# SPU.net
KiCad netlist of a schematic drawn in EAGLE
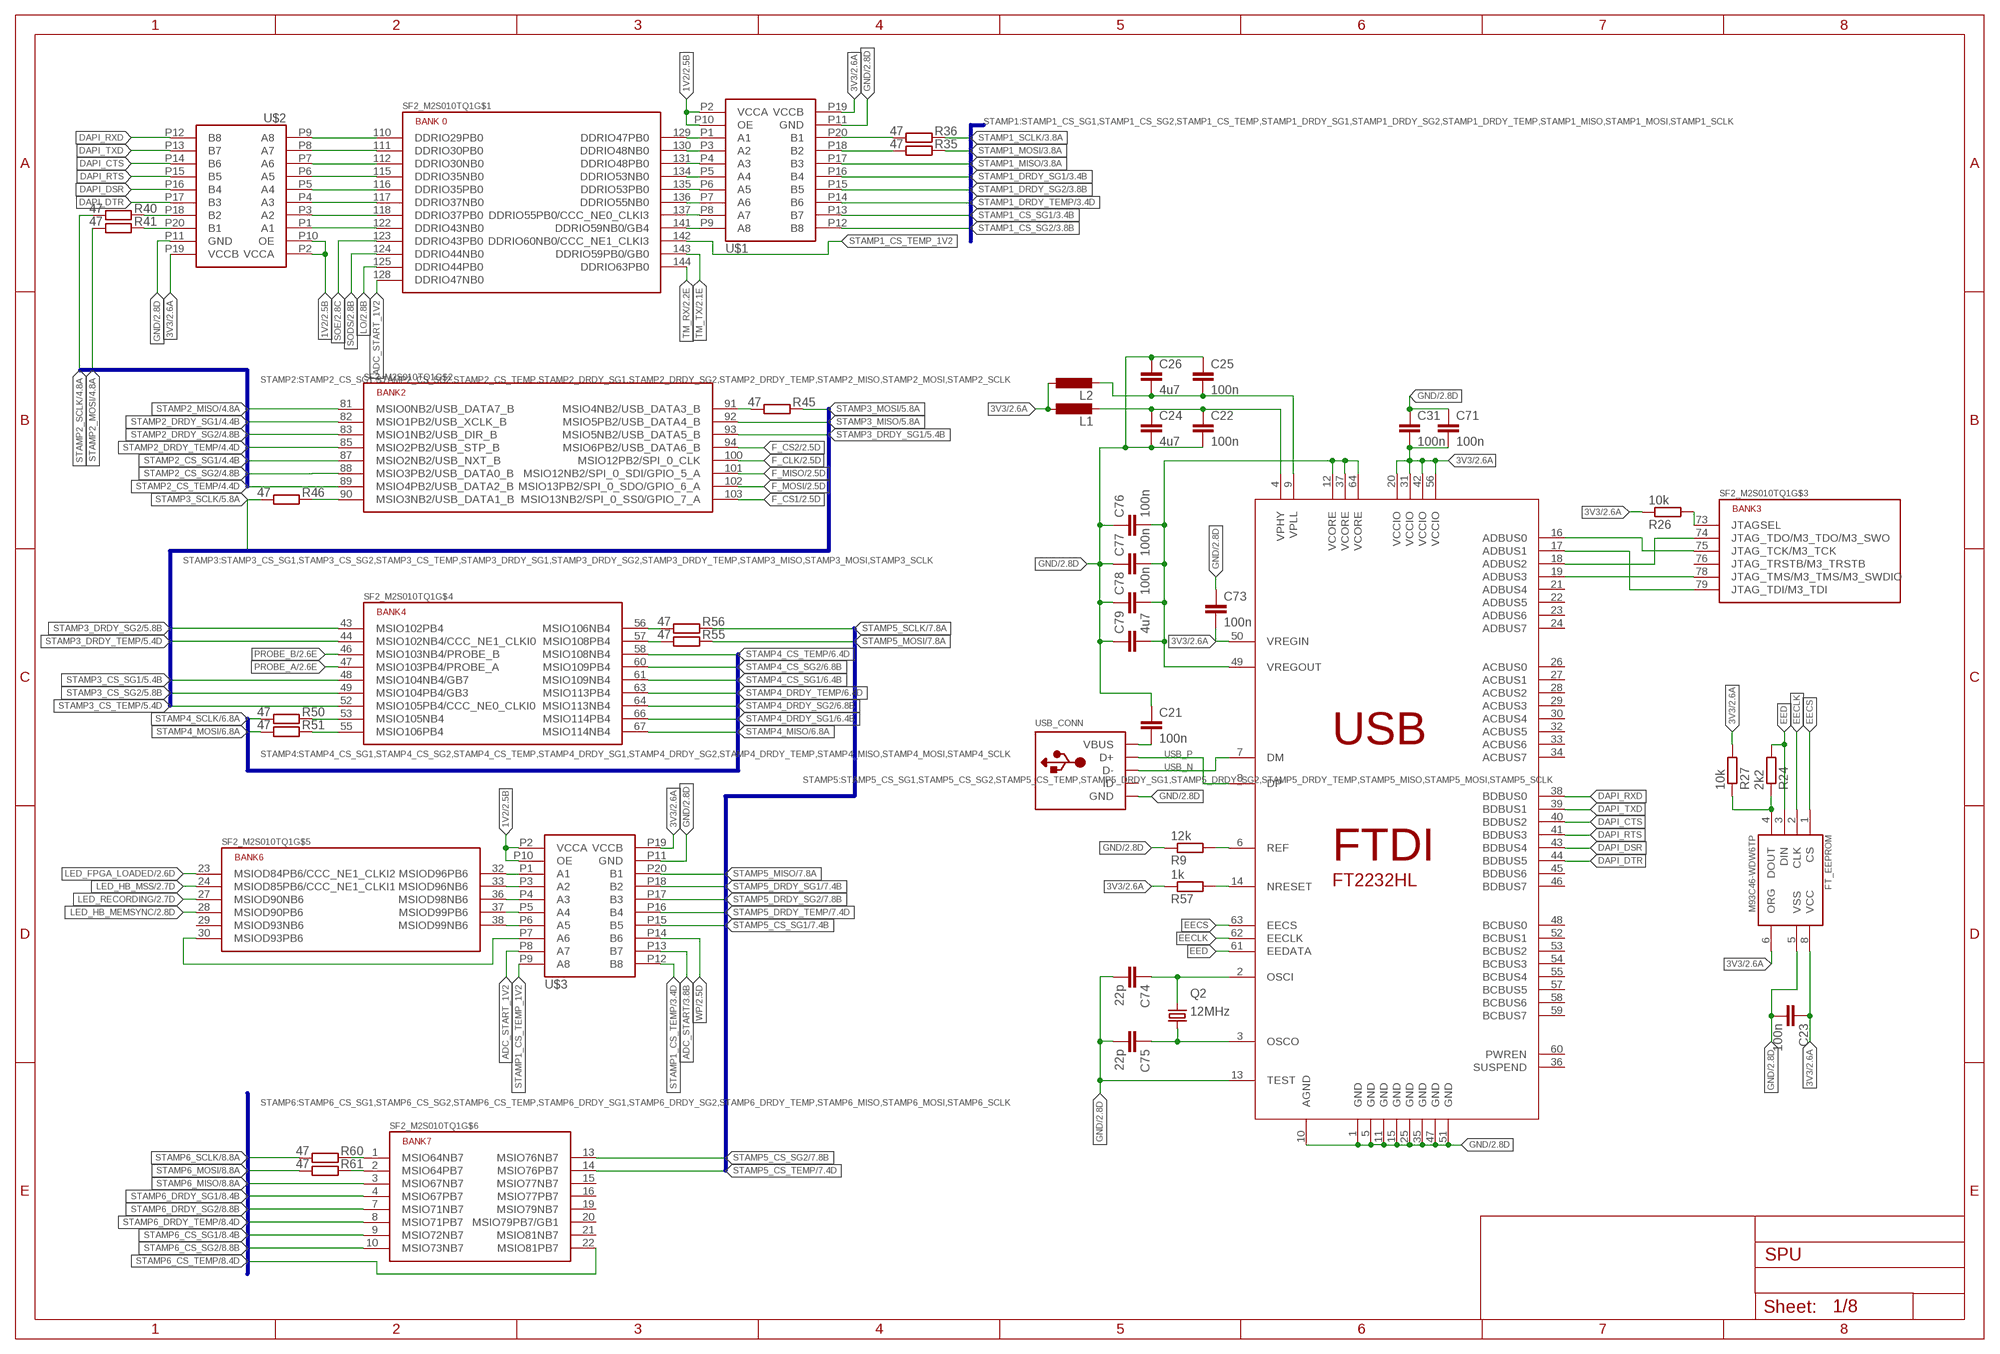
[diagram p0: schematic, sheet 1]
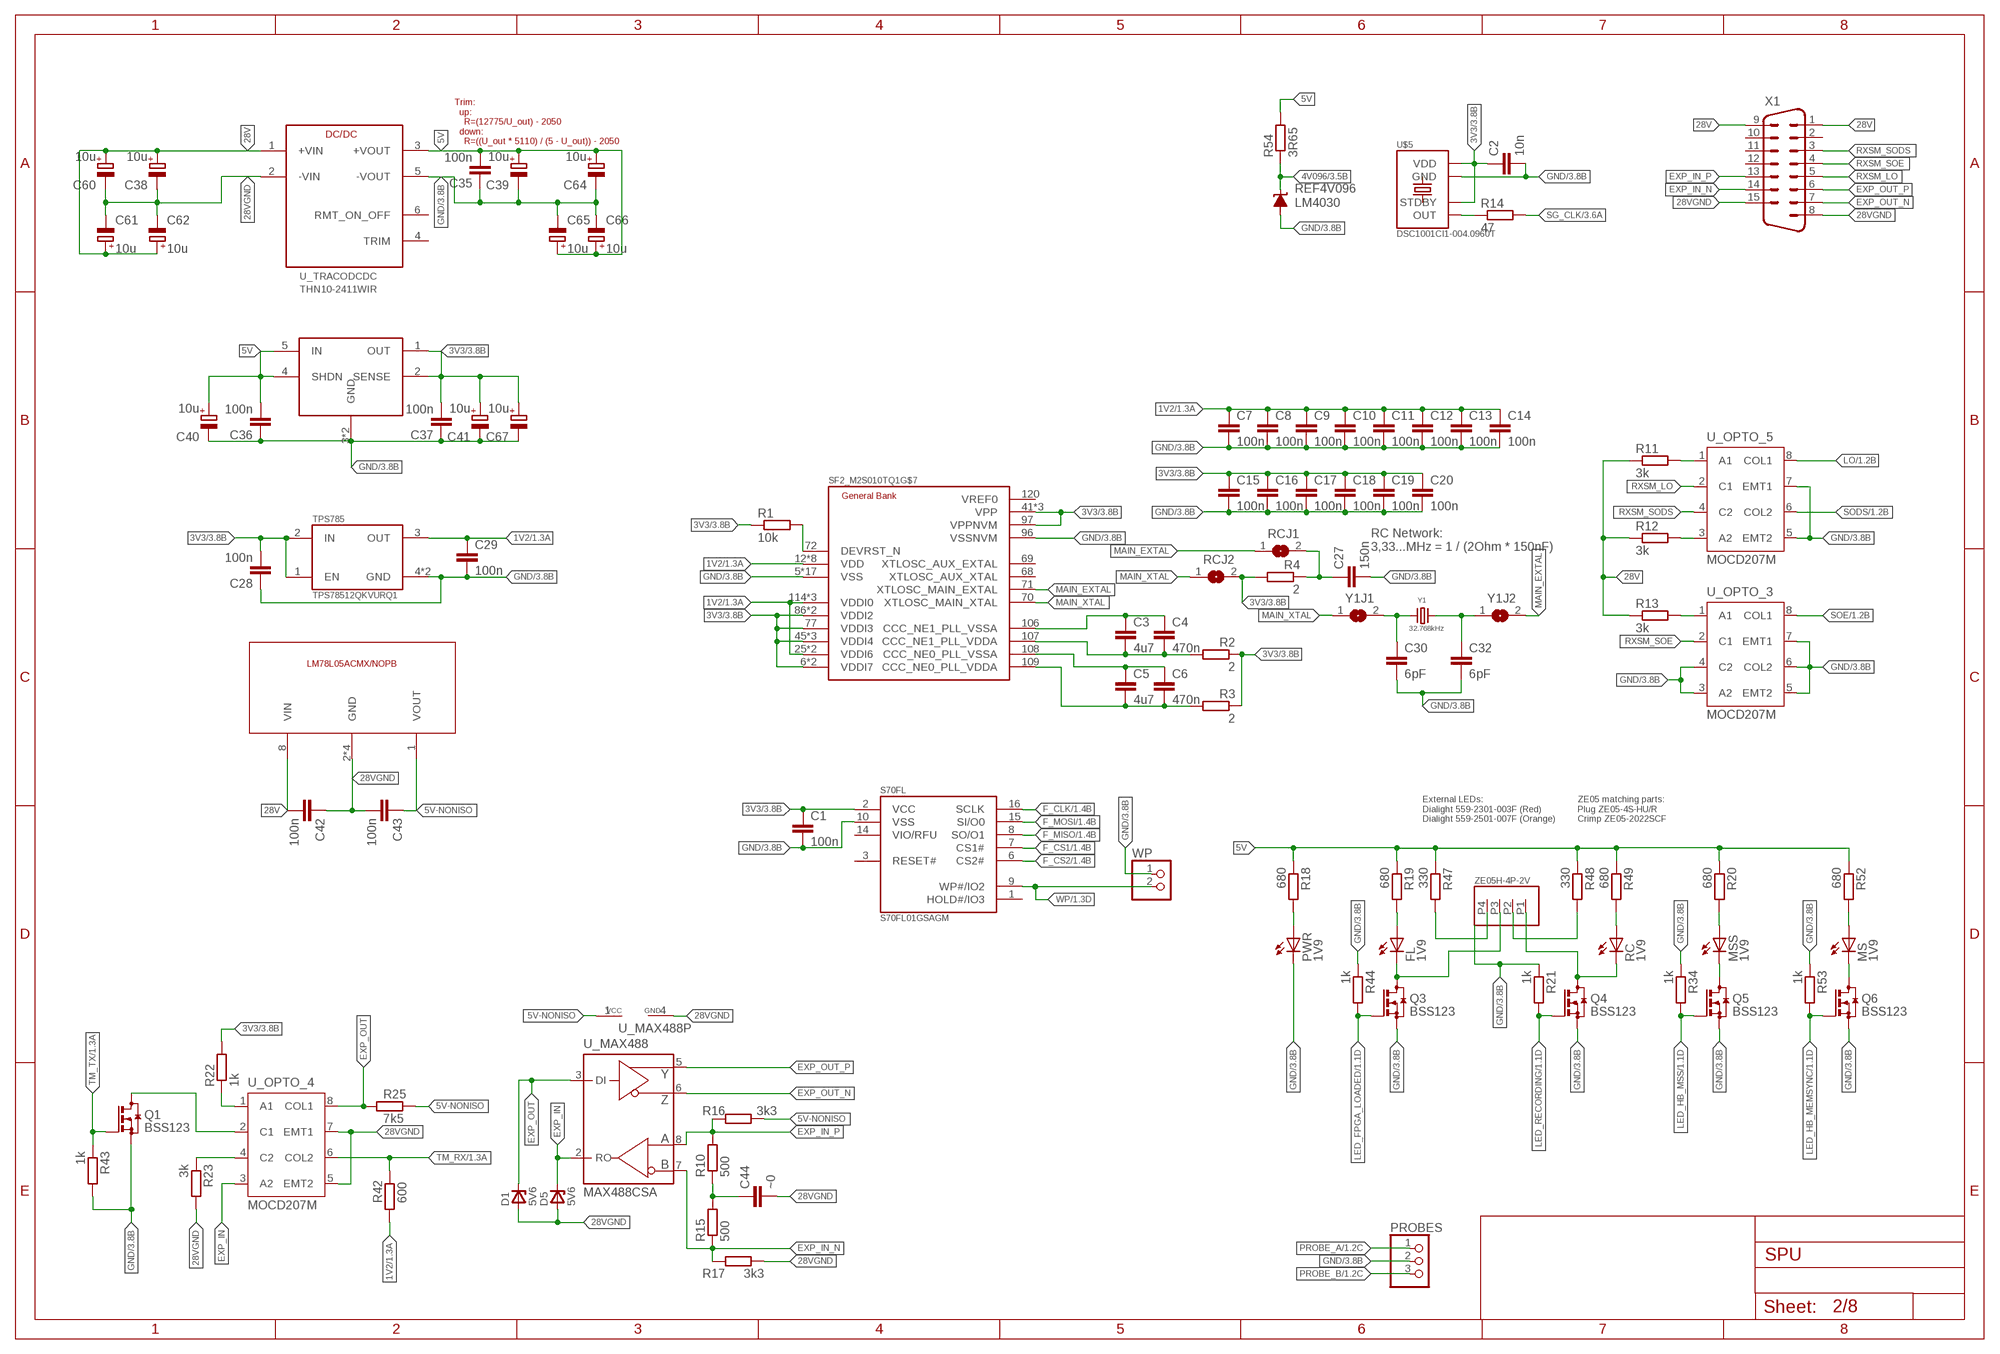
[diagram p1: schematic, sheet 2]
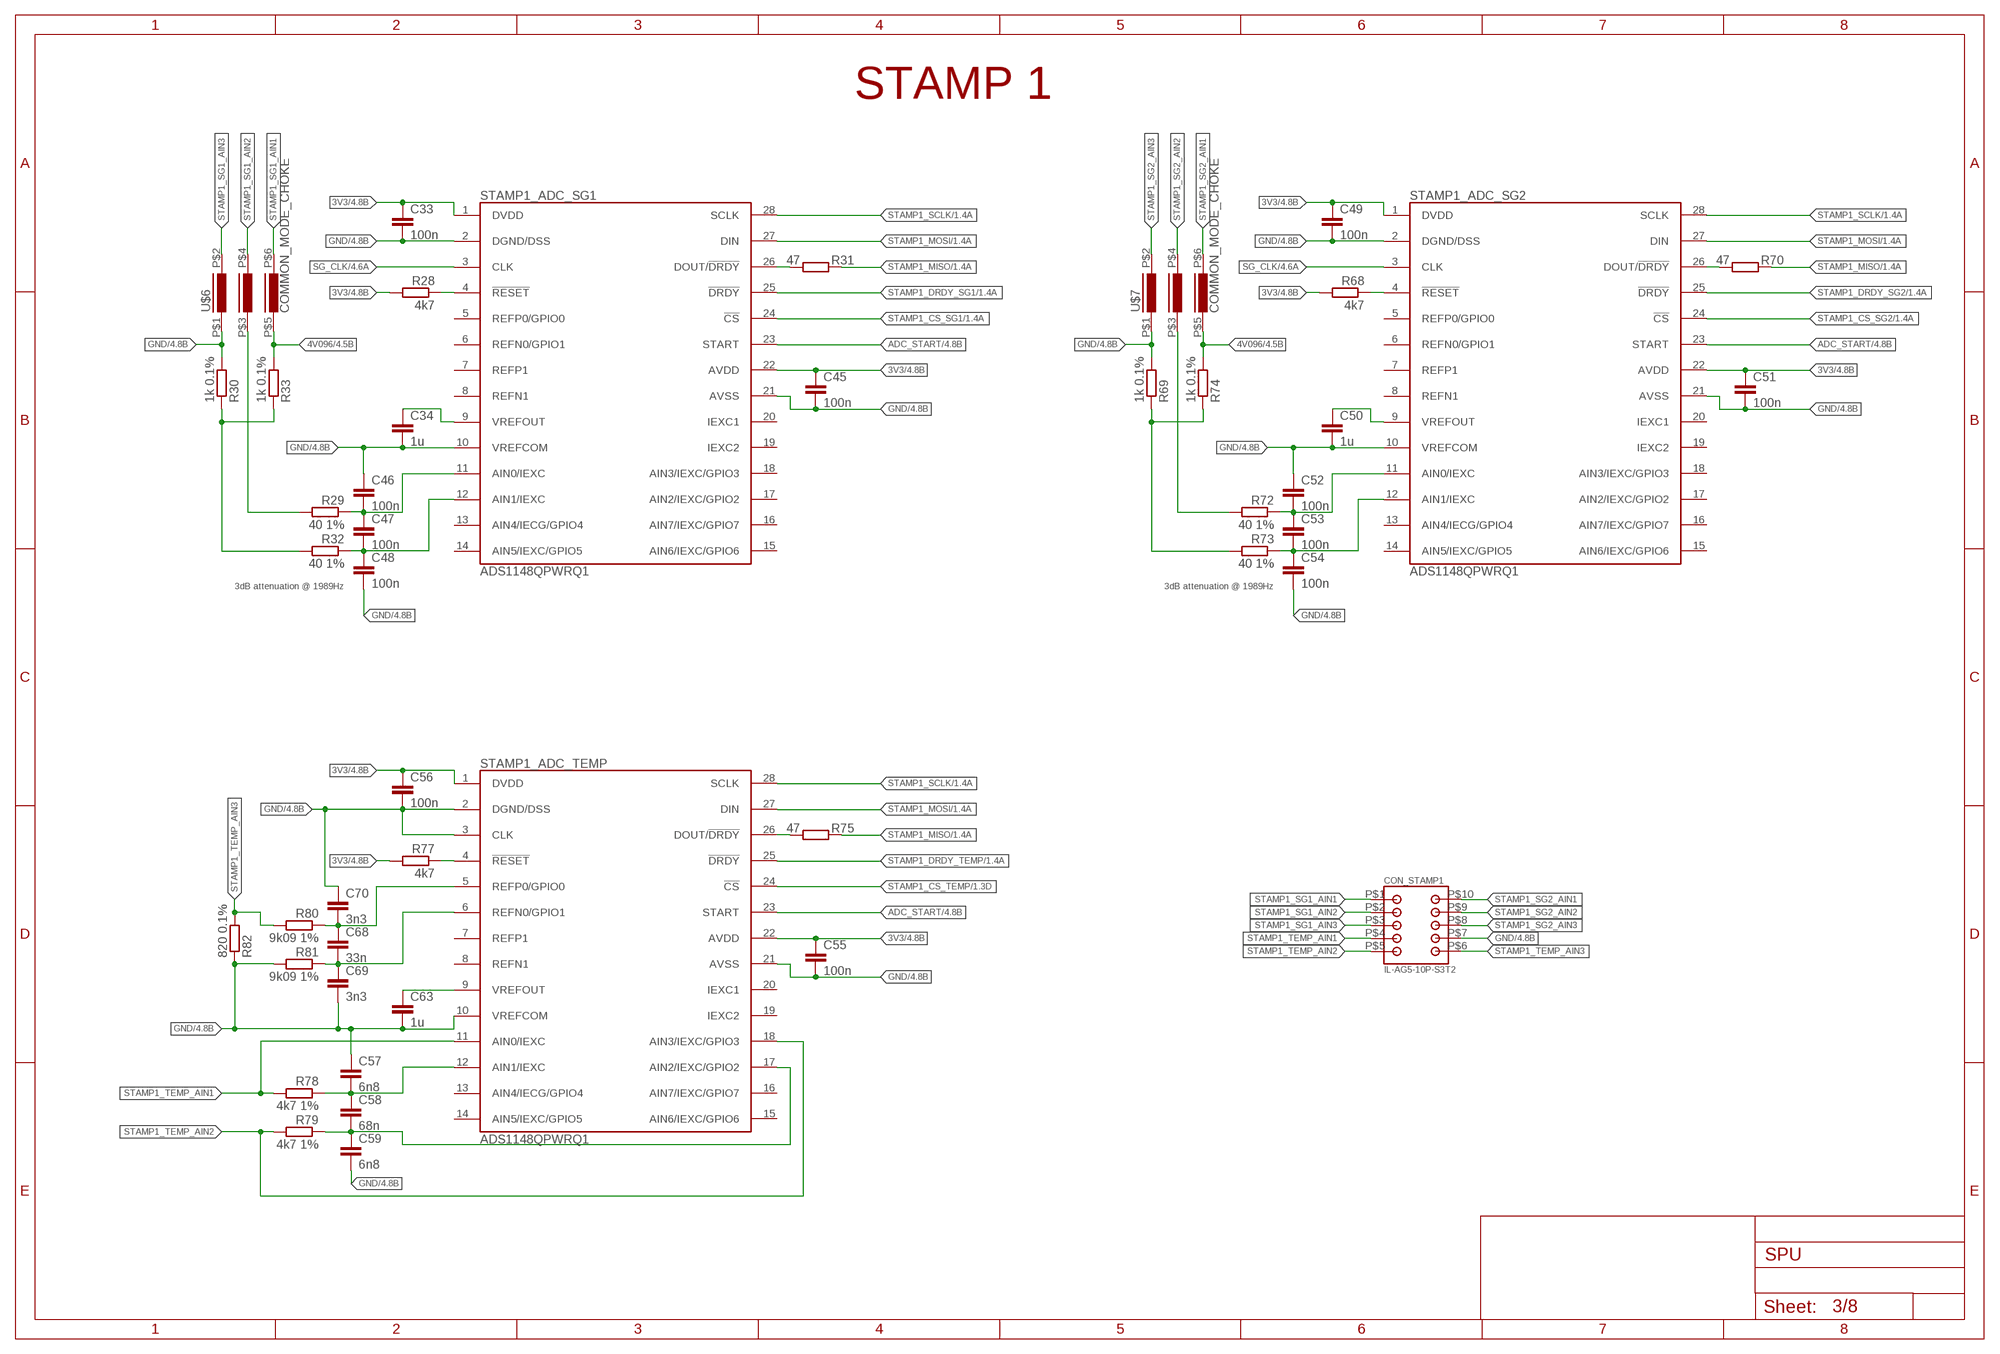
[diagram p2: schematic, sheet 3]
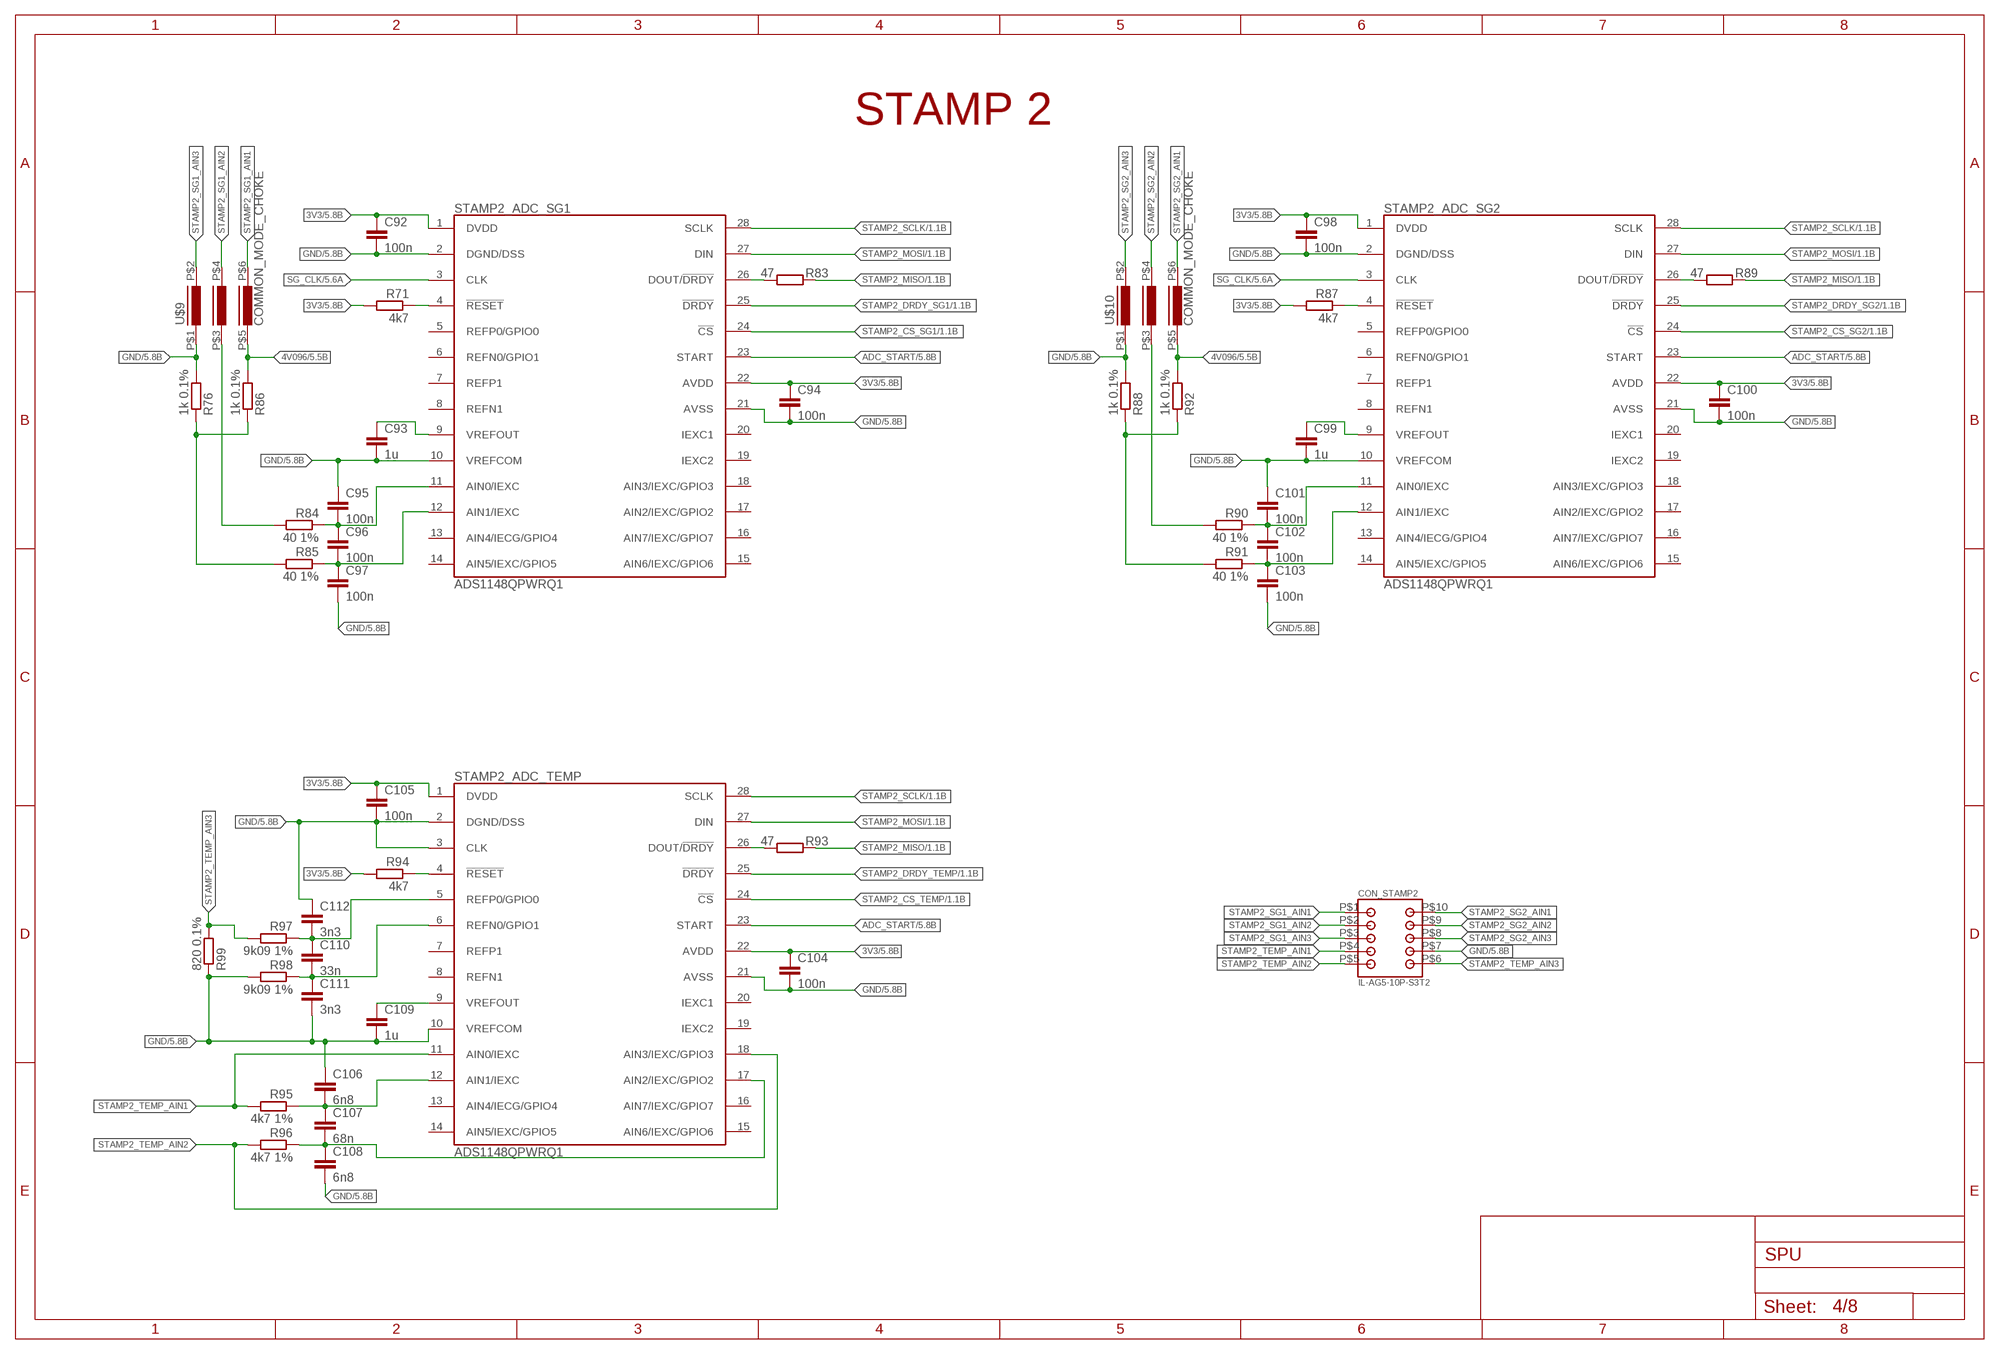
[diagram p3: schematic, sheet 4]
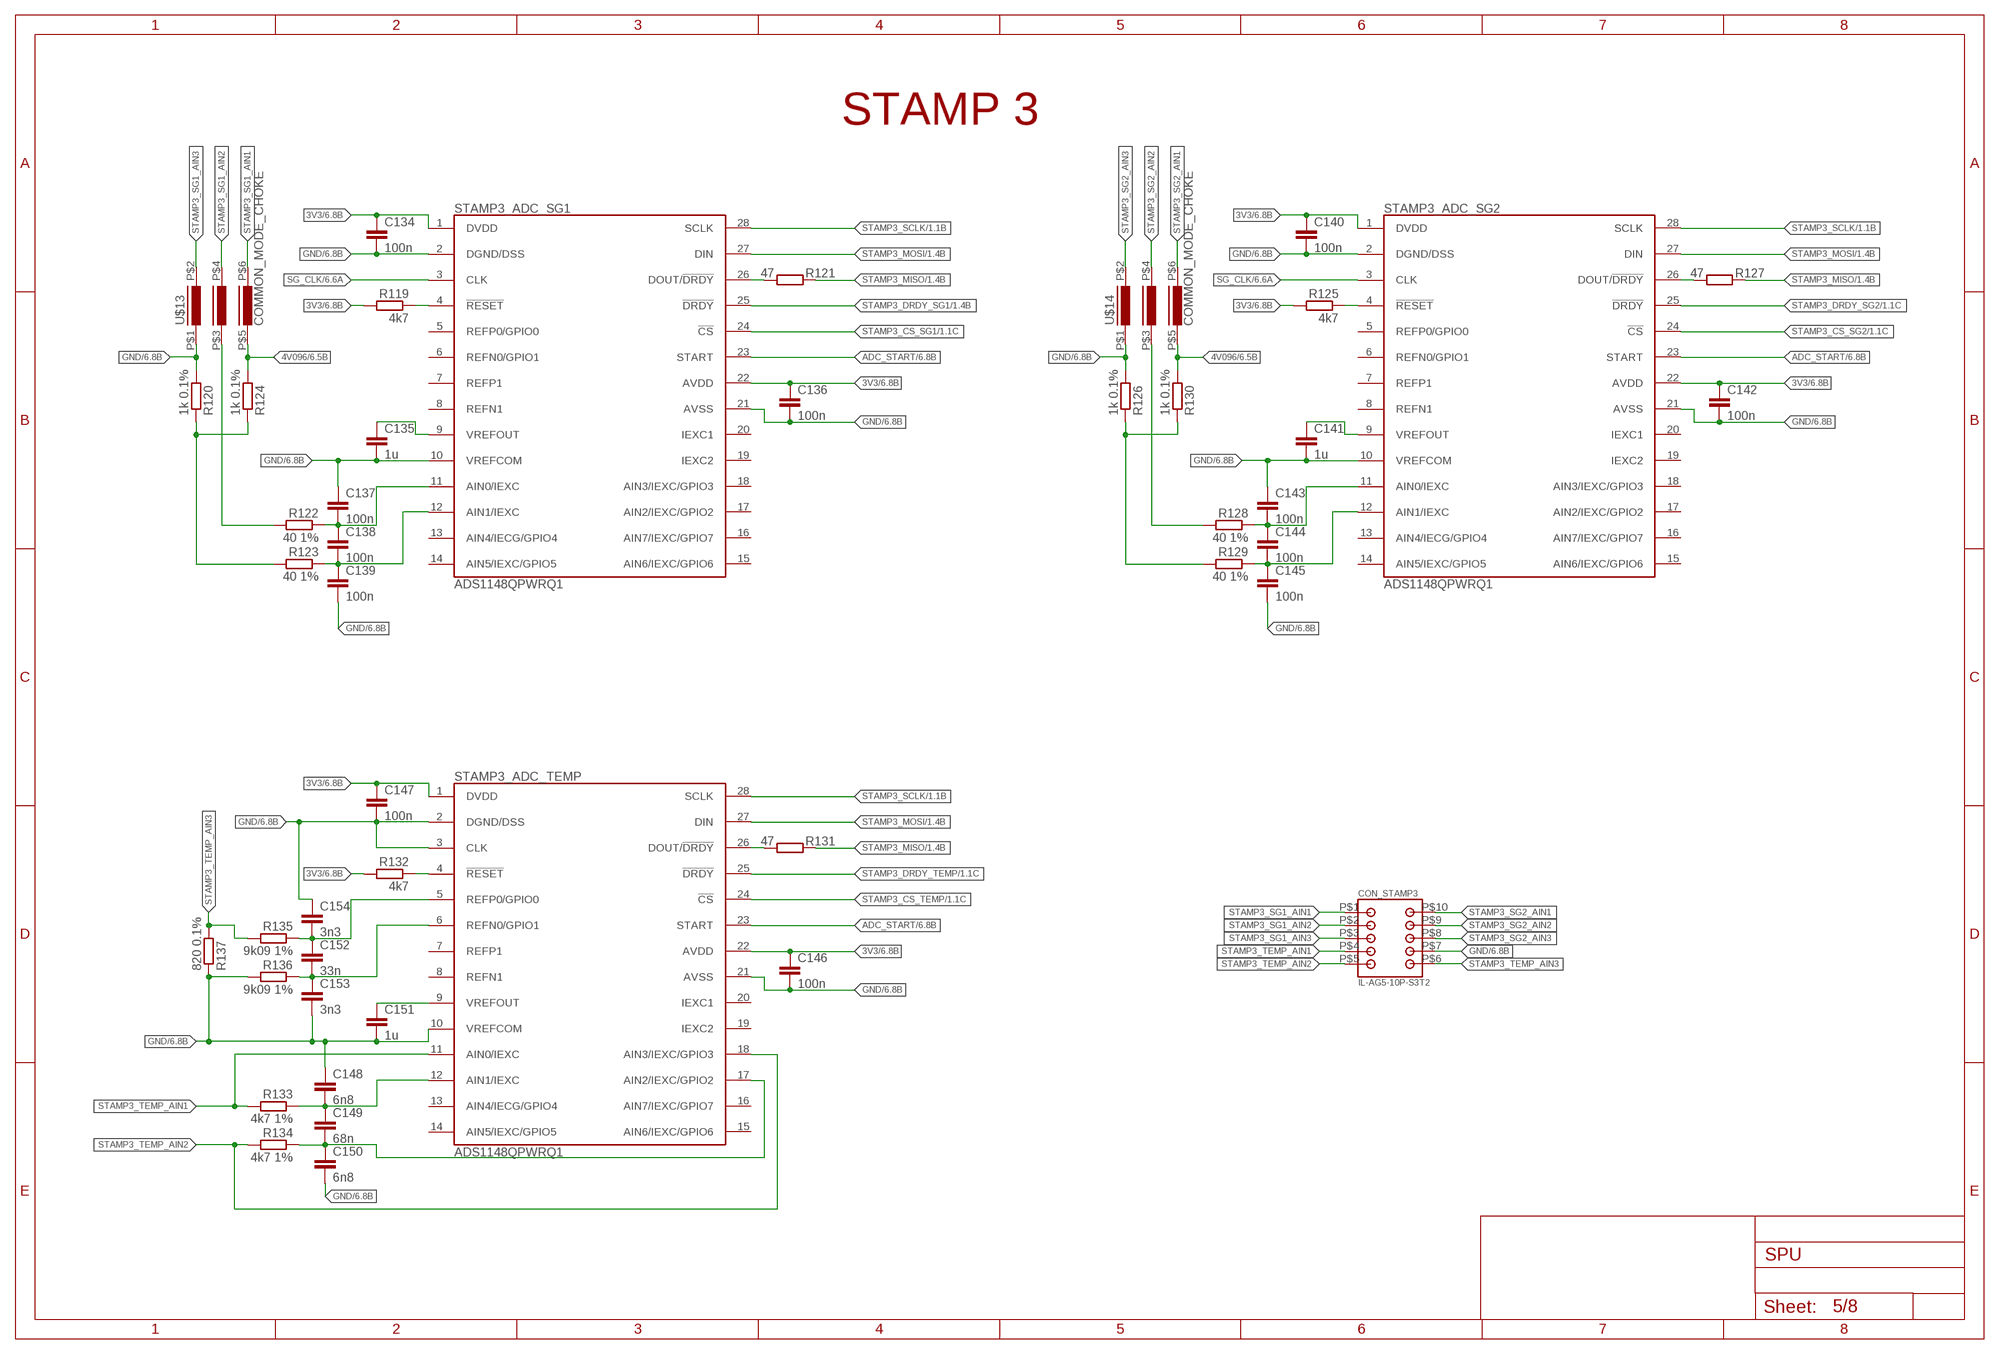
[diagram p4: schematic, sheet 5]
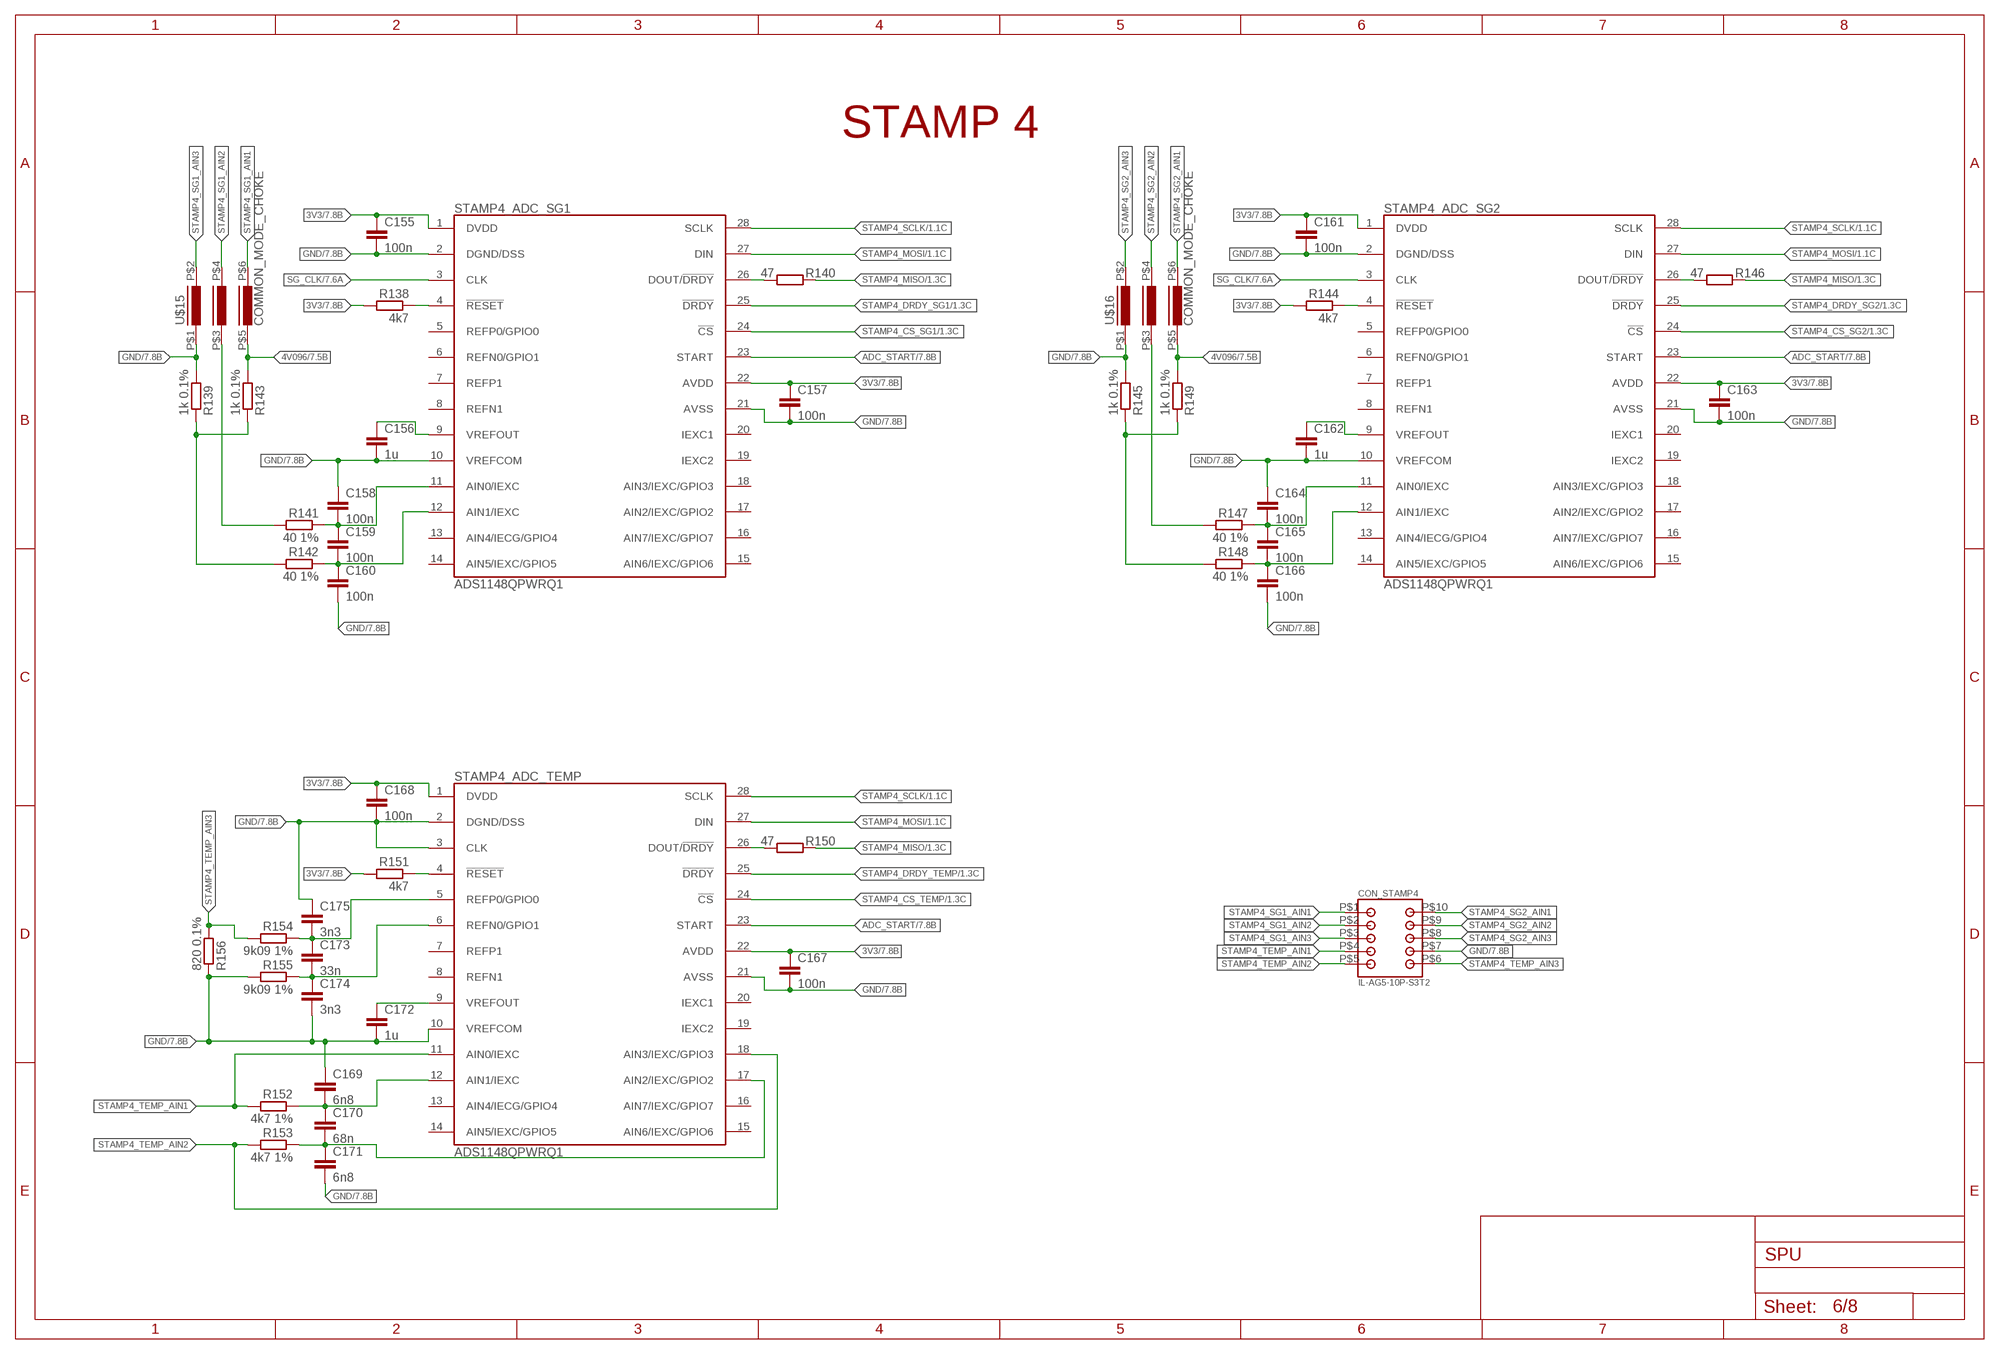
[diagram p5: schematic, sheet 6]
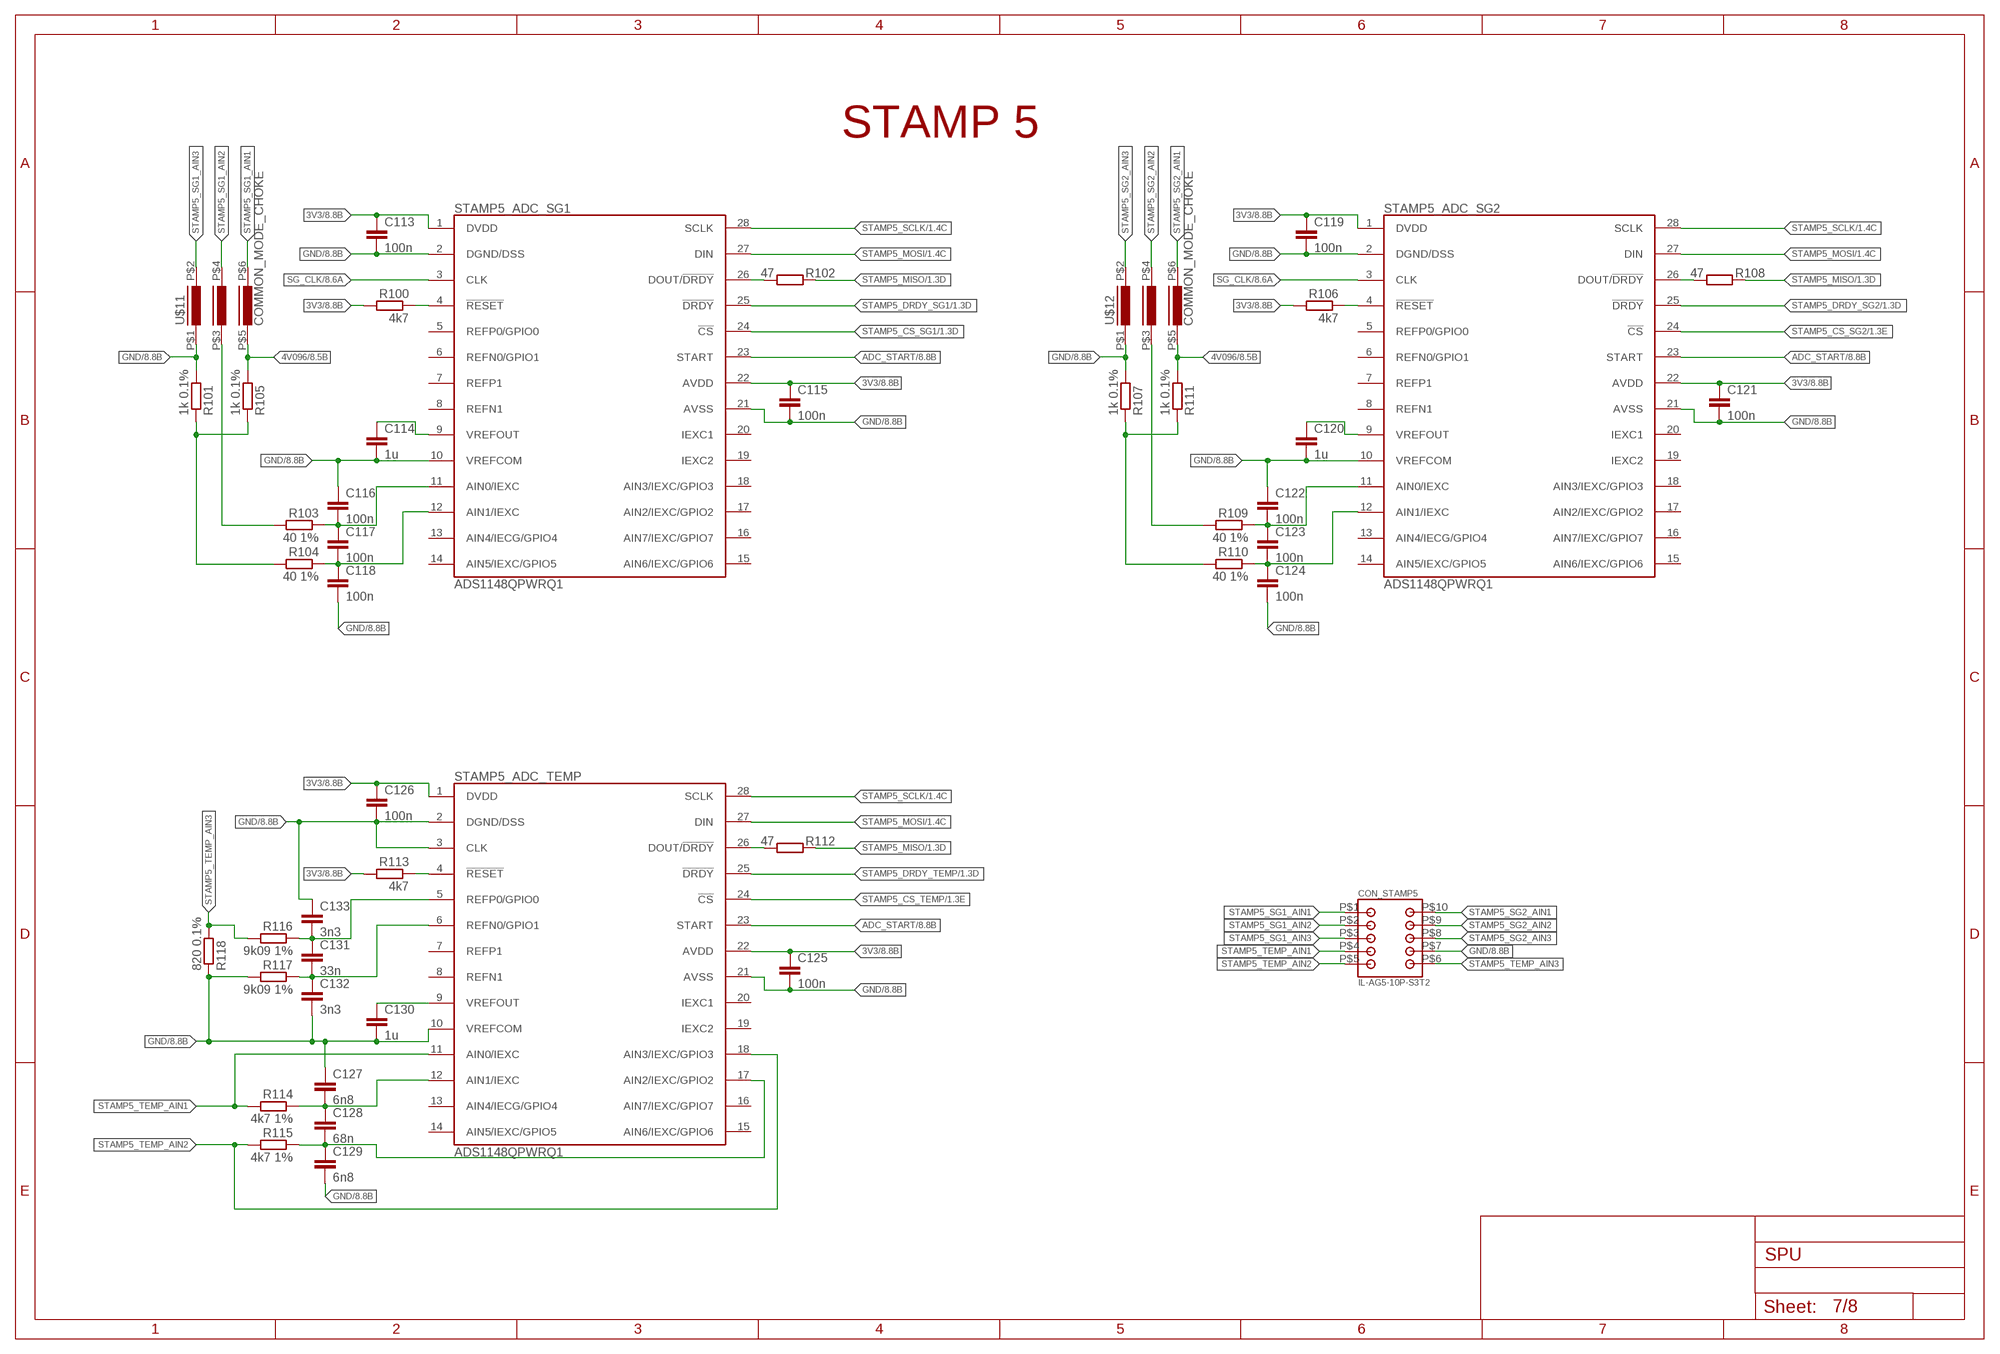
[diagram p6: schematic, sheet 7]
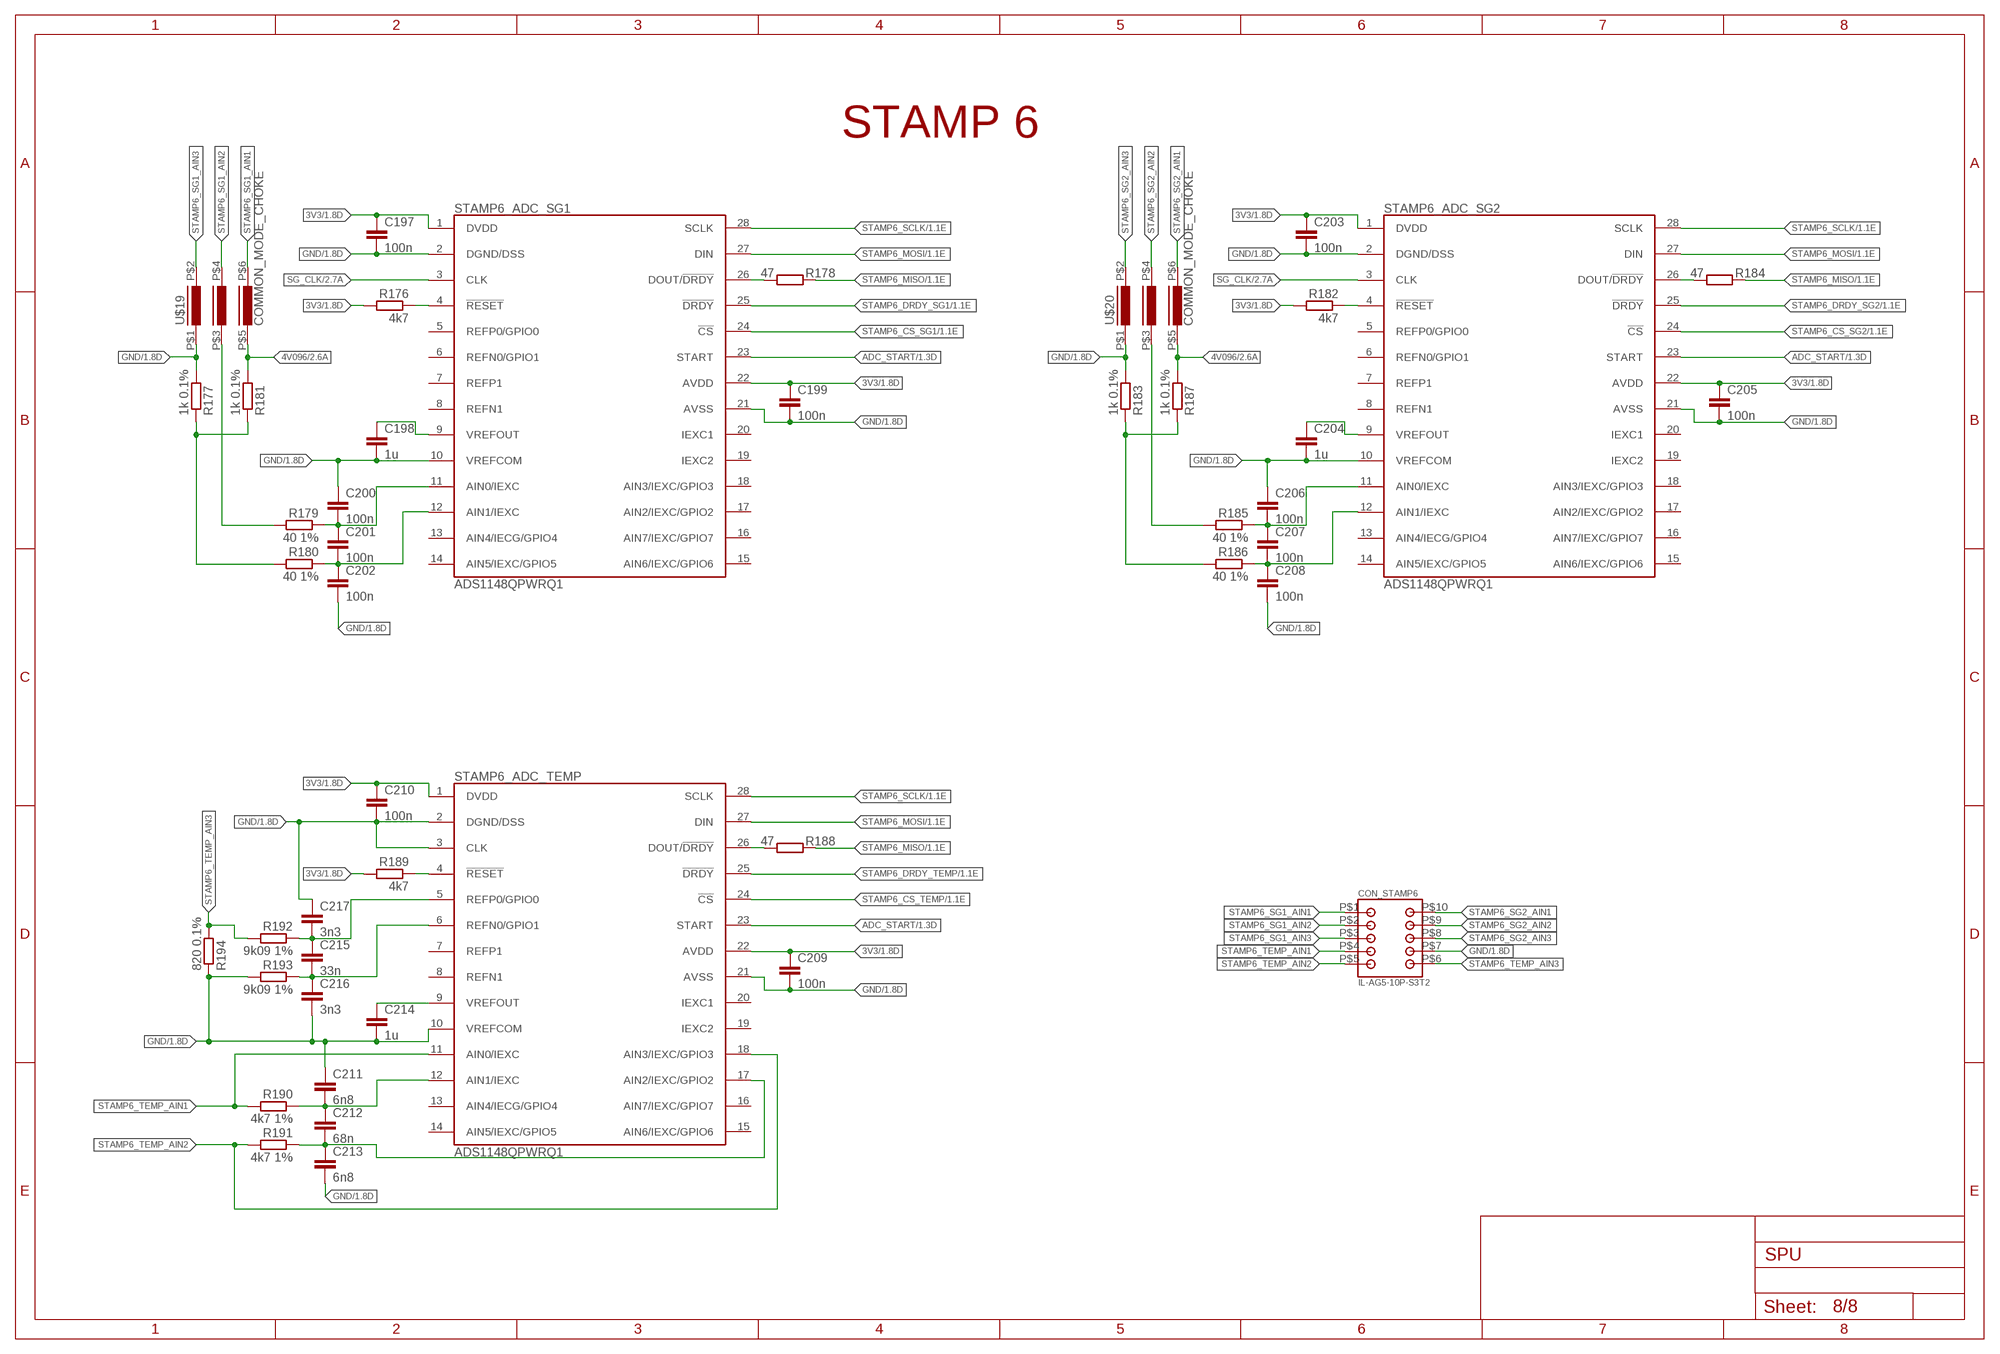
[diagram p7: schematic, sheet 8]

(export (version "E")
  (design (tool "Eeschema 10.0.6"))
  (components
    (comp (ref "C1")
      (value "100n")
      (footprint "eagle-import:C0805")
      (libsource (lib "eagle-import") (part "C-EUC0805"))
    )
    (comp (ref "C2")
      (value "10n")
      (footprint "eagle-import:C0805")
      (libsource (lib "eagle-import") (part "C-EUC0805"))
    )
    (comp (ref "C3")
      (value "4u7")
      (footprint "eagle-import:C0805")
      (libsource (lib "eagle-import") (part "C-EUC0805"))
    )
    (comp (ref "C4")
      (value "470n")
      (footprint "eagle-import:C0805")
      (libsource (lib "eagle-import") (part "C-EUC0805"))
    )
    (comp (ref "C5")
      (value "4u7")
      (footprint "eagle-import:C0805")
      (libsource (lib "eagle-import") (part "C-EUC0805"))
    )
    (comp (ref "C6")
      (value "470n")
      (footprint "eagle-import:C0805")
      (libsource (lib "eagle-import") (part "C-EUC0805"))
    )
    (comp (ref "C7")
      (value "100n")
      (footprint "eagle-import:C0805")
      (libsource (lib "eagle-import") (part "C-EUC0805"))
    )
    (comp (ref "C8")
      (value "100n")
      (footprint "eagle-import:C0805")
      (libsource (lib "eagle-import") (part "C-EUC0805"))
    )
    (comp (ref "C9")
      (value "100n")
      (footprint "eagle-import:C0805")
      (libsource (lib "eagle-import") (part "C-EUC0805"))
    )
    (comp (ref "C10")
      (value "100n")
      (footprint "eagle-import:C0805")
      (libsource (lib "eagle-import") (part "C-EUC0805"))
    )
    (comp (ref "C11")
      (value "100n")
      (footprint "eagle-import:C0805")
      (libsource (lib "eagle-import") (part "C-EUC0805"))
    )
    (comp (ref "C12")
      (value "100n")
      (footprint "eagle-import:C0805")
      (libsource (lib "eagle-import") (part "C-EUC0805"))
    )
    (comp (ref "C13")
      (value "100n")
      (footprint "eagle-import:C0805")
      (libsource (lib "eagle-import") (part "C-EUC0805"))
    )
    (comp (ref "C14")
      (value "100n")
      (footprint "eagle-import:C0805")
      (libsource (lib "eagle-import") (part "C-EUC0805"))
    )
    (comp (ref "C15")
      (value "100n")
      (footprint "eagle-import:C0805")
      (libsource (lib "eagle-import") (part "C-EUC0805"))
    )
    (comp (ref "C16")
      (value "100n")
      (footprint "eagle-import:C0805")
      (libsource (lib "eagle-import") (part "C-EUC0805"))
    )
    (comp (ref "C17")
      (value "100n")
      (footprint "eagle-import:C0805")
      (libsource (lib "eagle-import") (part "C-EUC0805"))
    )
    (comp (ref "C18")
      (value "100n")
      (footprint "eagle-import:C0805")
      (libsource (lib "eagle-import") (part "C-EUC0805"))
    )
    (comp (ref "C19")
      (value "100n")
      (footprint "eagle-import:C0805")
      (libsource (lib "eagle-import") (part "C-EUC0805"))
    )
    (comp (ref "C20")
      (value "100n")
      (footprint "eagle-import:C0805")
      (libsource (lib "eagle-import") (part "C-EUC0805"))
    )
    (comp (ref "C27")
      (value "150n")
      (footprint "eagle-import:C0805")
      (libsource (lib "eagle-import") (part "C-EUC0805"))
    )
    (comp (ref "C28")
      (value "100n")
      (footprint "eagle-import:C0805")
      (libsource (lib "eagle-import") (part "C-EUC0805"))
    )
    (comp (ref "C29")
      (value "100n")
      (footprint "eagle-import:C0805")
      (libsource (lib "eagle-import") (part "C-EUC0805"))
    )
    (comp (ref "C30")
      (value "6pF")
      (footprint "eagle-import:C0805")
      (libsource (lib "eagle-import") (part "C-EUC0805"))
    )
    (comp (ref "C32")
      (value "6pF")
      (footprint "eagle-import:C0805")
      (libsource (lib "eagle-import") (part "C-EUC0805"))
    )
    (comp (ref "C35")
      (value "100n")
      (footprint "eagle-import:C0805")
      (libsource (lib "eagle-import") (part "C-EUC0805"))
    )
    (comp (ref "C36")
      (value "100n")
      (footprint "eagle-import:C0805")
      (libsource (lib "eagle-import") (part "C-EUC0805"))
    )
    (comp (ref "C37")
      (value "100n")
      (footprint "eagle-import:C0805")
      (libsource (lib "eagle-import") (part "C-EUC0805"))
    )
    (comp (ref "C38")
      (value "10u")
      (footprint "eagle-import:E_7260-38W")
      (libsource (lib "eagle-import") (part "CPOL-EUE/7260-38W"))
    )
    (comp (ref "C39")
      (value "10u")
      (footprint "eagle-import:E_7260-38W")
      (libsource (lib "eagle-import") (part "CPOL-EUE/7260-38W"))
    )
    (comp (ref "C40")
      (value "10u")
      (footprint "eagle-import:E_7260-38W")
      (libsource (lib "eagle-import") (part "CPOL-EUE/7260-38W"))
    )
    (comp (ref "C41")
      (value "10u")
      (footprint "eagle-import:E_7260-38W")
      (libsource (lib "eagle-import") (part "CPOL-EUE/7260-38W"))
    )
    (comp (ref "C42")
      (value "100n")
      (footprint "eagle-import:C1206")
      (libsource (lib "eagle-import") (part "C-EUC1206"))
    )
    (comp (ref "C43")
      (value "100n")
      (footprint "eagle-import:C0805")
      (libsource (lib "eagle-import") (part "C-EUC0805"))
    )
    (comp (ref "C44")
      (value "~0")
      (footprint "eagle-import:C0805")
      (libsource (lib "eagle-import") (part "C-EUC0805"))
    )
    (comp (ref "C60")
      (value "10u")
      (footprint "eagle-import:E_7260-38W")
      (libsource (lib "eagle-import") (part "CPOL-EUE/7260-38W"))
    )
    (comp (ref "C61")
      (value "10u")
      (footprint "eagle-import:E_7260-38W")
      (libsource (lib "eagle-import") (part "CPOL-EUE/7260-38W"))
    )
    (comp (ref "C62")
      (value "10u")
      (footprint "eagle-import:E_7260-38W")
      (libsource (lib "eagle-import") (part "CPOL-EUE/7260-38W"))
    )
    (comp (ref "C64")
      (value "10u")
      (footprint "eagle-import:E_7260-38W")
      (libsource (lib "eagle-import") (part "CPOL-EUE/7260-38W"))
    )
    (comp (ref "C65")
      (value "10u")
      (footprint "eagle-import:E_7260-38W")
      (libsource (lib "eagle-import") (part "CPOL-EUE/7260-38W"))
    )
    (comp (ref "C66")
      (value "10u")
      (footprint "eagle-import:E_7260-38W")
      (libsource (lib "eagle-import") (part "CPOL-EUE/7260-38W"))
    )
    (comp (ref "C67")
      (value "10u")
      (footprint "eagle-import:E_7260-38W")
      (libsource (lib "eagle-import") (part "CPOL-EUE/7260-38W"))
    )
    (comp (ref "D1")
      (value "5V6")
      (footprint "eagle-import:DMELF")
      (libsource (lib "eagle-import") (part "DZMELF"))
    )
    (comp (ref "D5")
      (value "5V6")
      (footprint "eagle-import:DMELF")
      (libsource (lib "eagle-import") (part "DZMELF"))
    )
    (comp (ref "FL")
      (value "1V9")
      (footprint "eagle-import:CHIP-LED0805")
      (libsource (lib "eagle-import") (part "LEDCHIP-LED0805"))
    )
    (comp (ref "MS")
      (value "1V9")
      (footprint "eagle-import:CHIP-LED0805")
      (libsource (lib "eagle-import") (part "LEDCHIP-LED0805"))
    )
    (comp (ref "MSS")
      (value "1V9")
      (footprint "eagle-import:CHIP-LED0805")
      (libsource (lib "eagle-import") (part "LEDCHIP-LED0805"))
    )
    (comp (ref "PROBES")
      (value "PSS254_G3")
      (footprint "eagle-import:PSS254_G3")
      (libsource (lib "eagle-import") (part "PSS254_G3"))
    )
    (comp (ref "PWR")
      (value "1V9")
      (footprint "eagle-import:CHIP-LED0805")
      (libsource (lib "eagle-import") (part "LEDCHIP-LED0805"))
    )
    (comp (ref "Q1")
      (value "BSS123")
      (footprint "eagle-import:SOT23")
      (libsource (lib "eagle-import") (part "BSS123"))
    )
    (comp (ref "Q3")
      (value "BSS123")
      (footprint "eagle-import:SOT23")
      (libsource (lib "eagle-import") (part "BSS123"))
    )
    (comp (ref "Q4")
      (value "BSS123")
      (footprint "eagle-import:SOT23")
      (libsource (lib "eagle-import") (part "BSS123"))
    )
    (comp (ref "Q5")
      (value "BSS123")
      (footprint "eagle-import:SOT23")
      (libsource (lib "eagle-import") (part "BSS123"))
    )
    (comp (ref "Q6")
      (value "BSS123")
      (footprint "eagle-import:SOT23")
      (libsource (lib "eagle-import") (part "BSS123"))
    )
    (comp (ref "R1")
      (value "10k")
      (footprint "eagle-import:R0805")
      (libsource (lib "eagle-import") (part "rcl_334_R-EU_R0805"))
    )
    (comp (ref "R2")
      (value "2")
      (footprint "eagle-import:R0805")
      (libsource (lib "eagle-import") (part "rcl_334_R-EU_R0805"))
    )
    (comp (ref "R3")
      (value "2")
      (footprint "eagle-import:R0805")
      (libsource (lib "eagle-import") (part "rcl_334_R-EU_R0805"))
    )
    (comp (ref "R4")
      (value "2")
      (footprint "eagle-import:R0805")
      (libsource (lib "eagle-import") (part "rcl_334_R-EU_R0805"))
    )
    (comp (ref "R10")
      (value "500")
      (footprint "eagle-import:R0805")
      (libsource (lib "eagle-import") (part "R-EU_R0805"))
    )
    (comp (ref "R11")
      (value "3k")
      (footprint "eagle-import:R0805")
      (libsource (lib "eagle-import") (part "R-EU_R0805"))
    )
    (comp (ref "R12")
      (value "3k")
      (footprint "eagle-import:R0805")
      (libsource (lib "eagle-import") (part "R-EU_R0805"))
    )
    (comp (ref "R13")
      (value "3k")
      (footprint "eagle-import:R0805")
      (libsource (lib "eagle-import") (part "R-EU_R0805"))
    )
    (comp (ref "R14")
      (value "47")
      (footprint "eagle-import:R0805")
      (libsource (lib "eagle-import") (part "rcl_334_R-EU_R0805"))
    )
    (comp (ref "R15")
      (value "500")
      (footprint "eagle-import:R0805")
      (libsource (lib "eagle-import") (part "R-EU_R0805"))
    )
    (comp (ref "R16")
      (value "3k3")
      (footprint "eagle-import:R0805")
      (libsource (lib "eagle-import") (part "R-EU_R0805"))
    )
    (comp (ref "R17")
      (value "3k3")
      (footprint "eagle-import:R0805")
      (libsource (lib "eagle-import") (part "R-EU_R0805"))
    )
    (comp (ref "R18")
      (value "680")
      (footprint "eagle-import:R0805")
      (libsource (lib "eagle-import") (part "R-EU_R0805"))
    )
    (comp (ref "R19")
      (value "680")
      (footprint "eagle-import:R0805")
      (libsource (lib "eagle-import") (part "R-EU_R0805"))
    )
    (comp (ref "R20")
      (value "680")
      (footprint "eagle-import:R0805")
      (libsource (lib "eagle-import") (part "R-EU_R0805"))
    )
    (comp (ref "R21")
      (value "1k")
      (footprint "eagle-import:R0805")
      (libsource (lib "eagle-import") (part "R-EU_R0805"))
    )
    (comp (ref "R22")
      (value "1k")
      (footprint "eagle-import:R0805")
      (libsource (lib "eagle-import") (part "R-EU_R0805"))
    )
    (comp (ref "R23")
      (value "3k")
      (footprint "eagle-import:R0805")
      (libsource (lib "eagle-import") (part "R-EU_R0805"))
    )
    (comp (ref "R25")
      (value "7k5")
      (footprint "eagle-import:R0805")
      (libsource (lib "eagle-import") (part "rcl_334_R-EU_R0805"))
    )
    (comp (ref "R34")
      (value "1k")
      (footprint "eagle-import:R0805")
      (libsource (lib "eagle-import") (part "R-EU_R0805"))
    )
    (comp (ref "R42")
      (value "600")
      (footprint "eagle-import:R0805")
      (libsource (lib "eagle-import") (part "rcl_334_R-EU_R0805"))
    )
    (comp (ref "R43")
      (value "1k")
      (footprint "eagle-import:R0805")
      (libsource (lib "eagle-import") (part "R-EU_R0805"))
    )
    (comp (ref "R44")
      (value "1k")
      (footprint "eagle-import:R0805")
      (libsource (lib "eagle-import") (part "R-EU_R0805"))
    )
    (comp (ref "R47")
      (value "330")
      (footprint "eagle-import:R0805")
      (libsource (lib "eagle-import") (part "R-EU_R0805"))
    )
    (comp (ref "R48")
      (value "330")
      (footprint "eagle-import:R0805")
      (libsource (lib "eagle-import") (part "R-EU_R0805"))
    )
    (comp (ref "R49")
      (value "680")
      (footprint "eagle-import:R0805")
      (libsource (lib "eagle-import") (part "R-EU_R0805"))
    )
    (comp (ref "R52")
      (value "680")
      (footprint "eagle-import:R0805")
      (libsource (lib "eagle-import") (part "R-EU_R0805"))
    )
    (comp (ref "R53")
      (value "1k")
      (footprint "eagle-import:R0805")
      (libsource (lib "eagle-import") (part "R-EU_R0805"))
    )
    (comp (ref "R54")
      (value "3R65")
      (footprint "eagle-import:R0805")
      (libsource (lib "eagle-import") (part "rcl_334_R-EU_R0805"))
    )
    (comp (ref "RC")
      (value "1V9")
      (footprint "eagle-import:CHIP-LED0805")
      (libsource (lib "eagle-import") (part "LEDCHIP-LED0805"))
    )
    (comp (ref "RCJ1")
      (value "SJ")
      (footprint "eagle-import:SJ")
      (libsource (lib "eagle-import") (part "SJ"))
    )
    (comp (ref "RCJ2")
      (value "SJ")
      (footprint "eagle-import:SJ")
      (libsource (lib "eagle-import") (part "SJ"))
    )
    (comp (ref "REF4V096")
      (value "LM4030")
      (footprint "eagle-import:SOT-23")
      (libsource (lib "eagle-import") (part "LM4030"))
    )
    (comp (ref "S70FL")
      (value "S70FL01GSAGM")
      (footprint "eagle-import:SOIC16")
      (libsource (lib "eagle-import") (part "S70FL01GSAGM"))
    )
    (comp (ref "SF2_M2S010TQ1")
      (value "SF2_M2S010TQ144")
      (footprint "eagle-import:TQFP144")
      (libsource (lib "eagle-import") (part "SF2_M2S010TQ144"))
    )
    (comp (ref "TPS78512QKVURQ1")
      (value "TPS785")
      (footprint "eagle-import:TO-252-5")
      (libsource (lib "eagle-import") (part "TPS785"))
    )
    (comp (ref "U$5")
      (value "DSC1001CI1-004.0960T")
      (footprint "eagle-import:CDFN3225")
      (fields (field (name "SPICEPREFIX") "E"))
      (libsource (lib "eagle-import") (part "DSC1001CI1-004.0960T"))
    )
    (comp (ref "U_7805")
      (value "LM78L05ACMX/NOPB")
      (footprint "eagle-import:SOIC8")
      (libsource (lib "eagle-import") (part "LM78L05ACMX/NOPB"))
    )
    (comp (ref "U_LT1528")
      (value "LT1528")
      (footprint "eagle-import:Q5-DD")
      (libsource (lib "eagle-import") (part "LT1528"))
    )
    (comp (ref "U_MAX488")
      (value "MAX488CSA")
      (footprint "eagle-import:SO08")
      (fields (field (name "MF") "MAXIM"))
      (libsource (lib "eagle-import") (part "MAX488CSA"))
    )
    (comp (ref "U_OPTO_3")
      (value "MOCD207M")
      (footprint "eagle-import:SOIC127P594X363-8N")
      (fields (field (name "MANUFACTURER") "ON Semiconductor"))
      (libsource (lib "eagle-import") (part "MOCD207M_SOIC8"))
    )
    (comp (ref "U_OPTO_4")
      (value "MOCD207M")
      (footprint "eagle-import:SOIC127P594X363-8N")
      (fields (field (name "MANUFACTURER") "ON Semiconductor"))
      (libsource (lib "eagle-import") (part "MOCD207M_SOIC8"))
    )
    (comp (ref "U_OPTO_5")
      (value "MOCD207M")
      (footprint "eagle-import:SOIC127P594X363-8N")
      (fields (field (name "MANUFACTURER") "ON Semiconductor"))
      (libsource (lib "eagle-import") (part "MOCD207M_SOIC8"))
    )
    (comp (ref "U_TRACODCDC")
      (value "THN10-2411WIR")
      (footprint "eagle-import:THL_20WI_SERIES")
      (libsource (lib "eagle-import") (part "THL_20WI_SERIES"))
    )
    (comp (ref "WP")
      (value "PSS254_G2")
      (footprint "eagle-import:PSS254_G2")
      (libsource (lib "eagle-import") (part "PSS254_G2"))
    )
    (comp (ref "X1")
      (value "M15H")
      (footprint "eagle-import:M15H")
      (libsource (lib "eagle-import") (part "M15H"))
    )
    (comp (ref "Y1")
      (value "32.768kHz")
      (footprint "eagle-import:WE-XTAL_IQXC-90")
      (fields (field (name "TOLERANCE") "±20ppm"))
      (libsource (lib "eagle-import") (part "WE-XTAL_IQXC-90_830107088501"))
    )
    (comp (ref "Y1J1")
      (value "SJ")
      (footprint "eagle-import:SJ")
      (libsource (lib "eagle-import") (part "SJ"))
    )
    (comp (ref "Y1J2")
      (value "SJ")
      (footprint "eagle-import:SJ")
      (libsource (lib "eagle-import") (part "SJ"))
    )
    (comp (ref "ZE05H-4P-2V")
      (value "ZE05-4P-2V")
      (footprint "eagle-import:ZE05H-4P-2V")
      (libsource (lib "eagle-import") (part "ZE05-4P-2V"))
    )
    (comp (ref "C92")
      (value "100n")
      (footprint "eagle-import:C0805")
      (libsource (lib "eagle-import") (part "C-EUC0805"))
    )
    (comp (ref "C93")
      (value "1u")
      (footprint "eagle-import:C0805")
      (libsource (lib "eagle-import") (part "C-EUC0805"))
    )
    (comp (ref "C94")
      (value "100n")
      (footprint "eagle-import:C0805")
      (libsource (lib "eagle-import") (part "C-EUC0805"))
    )
    (comp (ref "C95")
      (value "100n")
      (footprint "eagle-import:C0805")
      (libsource (lib "eagle-import") (part "C-EUC0805"))
    )
    (comp (ref "C96")
      (value "100n")
      (footprint "eagle-import:C0805")
      (libsource (lib "eagle-import") (part "C-EUC0805"))
    )
    (comp (ref "C97")
      (value "100n")
      (footprint "eagle-import:C0805")
      (libsource (lib "eagle-import") (part "C-EUC0805"))
    )
    (comp (ref "C98")
      (value "100n")
      (footprint "eagle-import:C0805")
      (libsource (lib "eagle-import") (part "C-EUC0805"))
    )
    (comp (ref "C99")
      (value "1u")
      (footprint "eagle-import:C0805")
      (libsource (lib "eagle-import") (part "C-EUC0805"))
    )
    (comp (ref "C100")
      (value "100n")
      (footprint "eagle-import:C0805")
      (libsource (lib "eagle-import") (part "C-EUC0805"))
    )
    (comp (ref "C101")
      (value "100n")
      (footprint "eagle-import:C0805")
      (libsource (lib "eagle-import") (part "C-EUC0805"))
    )
    (comp (ref "C102")
      (value "100n")
      (footprint "eagle-import:C0805")
      (libsource (lib "eagle-import") (part "C-EUC0805"))
    )
    (comp (ref "C103")
      (value "100n")
      (footprint "eagle-import:C0805")
      (libsource (lib "eagle-import") (part "C-EUC0805"))
    )
    (comp (ref "C104")
      (value "100n")
      (footprint "eagle-import:C0805")
      (libsource (lib "eagle-import") (part "C-EUC0805"))
    )
    (comp (ref "C105")
      (value "100n")
      (footprint "eagle-import:C0805")
      (libsource (lib "eagle-import") (part "C-EUC0805"))
    )
    (comp (ref "C106")
      (value "6n8")
      (footprint "eagle-import:C0805")
      (libsource (lib "eagle-import") (part "C-EUC0805"))
    )
    (comp (ref "C107")
      (value "68n")
      (footprint "eagle-import:C0805")
      (libsource (lib "eagle-import") (part "C-EUC0805"))
    )
    (comp (ref "C108")
      (value "6n8")
      (footprint "eagle-import:C0805")
      (libsource (lib "eagle-import") (part "C-EUC0805"))
    )
    (comp (ref "C109")
      (value "1u")
      (footprint "eagle-import:C0805")
      (libsource (lib "eagle-import") (part "C-EUC0805"))
    )
    (comp (ref "C110")
      (value "33n")
      (footprint "eagle-import:C0805")
      (libsource (lib "eagle-import") (part "C-EUC0805"))
    )
    (comp (ref "C111")
      (value "3n3")
      (footprint "eagle-import:C0805")
      (libsource (lib "eagle-import") (part "C-EUC0805"))
    )
    (comp (ref "C112")
      (value "3n3")
      (footprint "eagle-import:C0805")
      (libsource (lib "eagle-import") (part "C-EUC0805"))
    )
    (comp (ref "CON_STAMP2")
      (value "IL-AG5-10P-S3T2")
      (footprint "eagle-import:IL-AG5-10P-S3T2")
      (libsource (lib "eagle-import") (part "IL-AG5-10P-S3T2"))
    )
    (comp (ref "R71")
      (value "4k7")
      (footprint "eagle-import:R0805")
      (libsource (lib "eagle-import") (part "rcl_334_R-EU_R0805"))
    )
    (comp (ref "R76")
      (value "1k 0.1%")
      (footprint "eagle-import:R0805")
      (libsource (lib "eagle-import") (part "rcl_334_R-EU_R0805"))
    )
    (comp (ref "R83")
      (value "47")
      (footprint "eagle-import:R0805")
      (libsource (lib "eagle-import") (part "rcl_334_R-EU_R0805"))
    )
    (comp (ref "R84")
      (value "40 1%")
      (footprint "eagle-import:R0805")
      (libsource (lib "eagle-import") (part "rcl_334_R-EU_R0805"))
    )
    (comp (ref "R85")
      (value "40 1%")
      (footprint "eagle-import:R0805")
      (libsource (lib "eagle-import") (part "rcl_334_R-EU_R0805"))
    )
    (comp (ref "R86")
      (value "1k 0.1%")
      (footprint "eagle-import:R0805")
      (libsource (lib "eagle-import") (part "rcl_334_R-EU_R0805"))
    )
    (comp (ref "R87")
      (value "4k7")
      (footprint "eagle-import:R0805")
      (libsource (lib "eagle-import") (part "rcl_334_R-EU_R0805"))
    )
    (comp (ref "R88")
      (value "1k 0.1%")
      (footprint "eagle-import:R0805")
      (libsource (lib "eagle-import") (part "rcl_334_R-EU_R0805"))
    )
    (comp (ref "R89")
      (value "47")
      (footprint "eagle-import:R0805")
      (libsource (lib "eagle-import") (part "rcl_334_R-EU_R0805"))
    )
    (comp (ref "R90")
      (value "40 1%")
      (footprint "eagle-import:R0805")
      (libsource (lib "eagle-import") (part "rcl_334_R-EU_R0805"))
    )
    (comp (ref "R91")
      (value "40 1%")
      (footprint "eagle-import:R0805")
      (libsource (lib "eagle-import") (part "rcl_334_R-EU_R0805"))
    )
    (comp (ref "R92")
      (value "1k 0.1%")
      (footprint "eagle-import:R0805")
      (libsource (lib "eagle-import") (part "rcl_334_R-EU_R0805"))
    )
    (comp (ref "R93")
      (value "47")
      (footprint "eagle-import:R0805")
      (libsource (lib "eagle-import") (part "rcl_334_R-EU_R0805"))
    )
    (comp (ref "R94")
      (value "4k7")
      (footprint "eagle-import:R0805")
      (libsource (lib "eagle-import") (part "rcl_334_R-EU_R0805"))
    )
    (comp (ref "R95")
      (value "4k7 1%")
      (footprint "eagle-import:R0805")
      (libsource (lib "eagle-import") (part "rcl_334_R-EU_R0805"))
    )
    (comp (ref "R96")
      (value "4k7 1%")
      (footprint "eagle-import:R0805")
      (libsource (lib "eagle-import") (part "rcl_334_R-EU_R0805"))
    )
    (comp (ref "R97")
      (value "9k09 1%")
      (footprint "eagle-import:R0805")
      (libsource (lib "eagle-import") (part "rcl_334_R-EU_R0805"))
    )
    (comp (ref "R98")
      (value "9k09 1%")
      (footprint "eagle-import:R0805")
      (libsource (lib "eagle-import") (part "rcl_334_R-EU_R0805"))
    )
    (comp (ref "R99")
      (value "820 0.1%")
      (footprint "eagle-import:R0805")
      (libsource (lib "eagle-import") (part "rcl_334_R-EU_R0805"))
    )
    (comp (ref "STAMP2_ADC_SG1")
      (value "ADS1148QPWRQ1")
      (footprint "eagle-import:TSSOP28")
      (libsource (lib "eagle-import") (part "ADS1148QPWRQ1"))
    )
    (comp (ref "STAMP2_ADC_SG2")
      (value "ADS1148QPWRQ1")
      (footprint "eagle-import:TSSOP28")
      (libsource (lib "eagle-import") (part "ADS1148QPWRQ1"))
    )
    (comp (ref "STAMP2_ADC_TEMP")
      (value "ADS1148QPWRQ1")
      (footprint "eagle-import:TSSOP28")
      (libsource (lib "eagle-import") (part "ADS1148QPWRQ1"))
    )
    (comp (ref "U$9")
      (value "COMMON_MODE_CHOKE")
      (footprint "eagle-import:COMMON_MODE_CHOKE")
      (libsource (lib "eagle-import") (part "COMMON_MODE_CHOKE"))
    )
    (comp (ref "U$10")
      (value "COMMON_MODE_CHOKE")
      (footprint "eagle-import:COMMON_MODE_CHOKE")
      (libsource (lib "eagle-import") (part "COMMON_MODE_CHOKE"))
    )
    (comp (ref "C21")
      (value "100n")
      (footprint "eagle-import:C0805")
      (libsource (lib "eagle-import") (part "C-EUC0805"))
    )
    (comp (ref "C22")
      (value "100n")
      (footprint "eagle-import:C0805")
      (libsource (lib "eagle-import") (part "C-EUC0805"))
    )
    (comp (ref "C23")
      (value "100n")
      (footprint "eagle-import:C0805")
      (libsource (lib "eagle-import") (part "C-EUC0805"))
    )
    (comp (ref "C24")
      (value "4u7")
      (footprint "eagle-import:C0805")
      (libsource (lib "eagle-import") (part "C-EUC0805"))
    )
    (comp (ref "C25")
      (value "100n")
      (footprint "eagle-import:C0805")
      (libsource (lib "eagle-import") (part "C-EUC0805"))
    )
    (comp (ref "C26")
      (value "4u7")
      (footprint "eagle-import:C0805")
      (libsource (lib "eagle-import") (part "C-EUC0805"))
    )
    (comp (ref "C31")
      (value "100n")
      (footprint "eagle-import:C0805")
      (libsource (lib "eagle-import") (part "C-EUC0805"))
    )
    (comp (ref "C71")
      (value "100n")
      (footprint "eagle-import:C0805")
      (libsource (lib "eagle-import") (part "C-EUC0805"))
    )
    (comp (ref "C73")
      (value "100n")
      (footprint "eagle-import:C0805")
      (libsource (lib "eagle-import") (part "C-EUC0805"))
    )
    (comp (ref "C74")
      (value "22p")
      (footprint "eagle-import:C0805")
      (libsource (lib "eagle-import") (part "C-EUC0805"))
    )
    (comp (ref "C75")
      (value "22p")
      (footprint "eagle-import:C0805")
      (libsource (lib "eagle-import") (part "C-EUC0805"))
    )
    (comp (ref "C76")
      (value "100n")
      (footprint "eagle-import:C0805")
      (libsource (lib "eagle-import") (part "C-EUC0805"))
    )
    (comp (ref "C77")
      (value "100n")
      (footprint "eagle-import:C0805")
      (libsource (lib "eagle-import") (part "C-EUC0805"))
    )
    (comp (ref "C78")
      (value "100n")
      (footprint "eagle-import:C0805")
      (libsource (lib "eagle-import") (part "C-EUC0805"))
    )
    (comp (ref "C79")
      (value "4u7")
      (footprint "eagle-import:C0805")
      (libsource (lib "eagle-import") (part "C-EUC0805"))
    )
    (comp (ref "FT_EEPROM")
      (value "M93C46-WDW6TP")
      (footprint "eagle-import:TSSOP-8")
      (libsource (lib "eagle-import") (part "M93C46-WDW6TP"))
    )
    (comp (ref "L1")
      (value "L-EUL1812")
      (footprint "eagle-import:L1812")
      (libsource (lib "eagle-import") (part "L-EUL1812"))
    )
    (comp (ref "L2")
      (value "L-EUL1812")
      (footprint "eagle-import:L1812")
      (libsource (lib "eagle-import") (part "L-EUL1812"))
    )
    (comp (ref "Q2")
      (value "12MHz")
      (footprint "eagle-import:HC49UP")
      (libsource (lib "eagle-import") (part "CRYSTALHC49UP"))
    )
    (comp (ref "R9")
      (value "12k")
      (footprint "eagle-import:R0805")
      (libsource (lib "eagle-import") (part "rcl_334_R-EU_R0805"))
    )
    (comp (ref "R24")
      (value "2k2")
      (footprint "eagle-import:R0805")
      (libsource (lib "eagle-import") (part "rcl_334_R-EU_R0805"))
    )
    (comp (ref "R26")
      (value "10k")
      (footprint "eagle-import:R0805")
      (libsource (lib "eagle-import") (part "rcl_334_R-EU_R0805"))
    )
    (comp (ref "R27")
      (value "10k")
      (footprint "eagle-import:R0805")
      (libsource (lib "eagle-import") (part "rcl_334_R-EU_R0805"))
    )
    (comp (ref "R35")
      (value "47")
      (footprint "eagle-import:R0805")
      (libsource (lib "eagle-import") (part "rcl_334_R-EU_R0805"))
    )
    (comp (ref "R36")
      (value "47")
      (footprint "eagle-import:R0805")
      (libsource (lib "eagle-import") (part "rcl_334_R-EU_R0805"))
    )
    (comp (ref "R40")
      (value "47")
      (footprint "eagle-import:R0805")
      (libsource (lib "eagle-import") (part "rcl_334_R-EU_R0805"))
    )
    (comp (ref "R41")
      (value "47")
      (footprint "eagle-import:R0805")
      (libsource (lib "eagle-import") (part "rcl_334_R-EU_R0805"))
    )
    (comp (ref "R45")
      (value "47")
      (footprint "eagle-import:R0805")
      (libsource (lib "eagle-import") (part "rcl_334_R-EU_R0805"))
    )
    (comp (ref "R46")
      (value "47")
      (footprint "eagle-import:R0805")
      (libsource (lib "eagle-import") (part "rcl_334_R-EU_R0805"))
    )
    (comp (ref "R50")
      (value "47")
      (footprint "eagle-import:R0805")
      (libsource (lib "eagle-import") (part "rcl_334_R-EU_R0805"))
    )
    (comp (ref "R51")
      (value "47")
      (footprint "eagle-import:R0805")
      (libsource (lib "eagle-import") (part "rcl_334_R-EU_R0805"))
    )
    (comp (ref "R55")
      (value "47")
      (footprint "eagle-import:R0805")
      (libsource (lib "eagle-import") (part "rcl_334_R-EU_R0805"))
    )
    (comp (ref "R56")
      (value "47")
      (footprint "eagle-import:R0805")
      (libsource (lib "eagle-import") (part "rcl_334_R-EU_R0805"))
    )
    (comp (ref "R57")
      (value "1k")
      (footprint "eagle-import:R0805")
      (libsource (lib "eagle-import") (part "rcl_334_R-EU_R0805"))
    )
    (comp (ref "R60")
      (value "47")
      (footprint "eagle-import:R0805")
      (libsource (lib "eagle-import") (part "rcl_334_R-EU_R0805"))
    )
    (comp (ref "R61")
      (value "47")
      (footprint "eagle-import:R0805")
      (libsource (lib "eagle-import") (part "rcl_334_R-EU_R0805"))
    )
    (comp (ref "U$1")
      (value "NXB0108PWJ")
      (footprint "eagle-import:TSSOP-20")
      (libsource (lib "eagle-import") (part "NXB0108PWJ"))
    )
    (comp (ref "U$2")
      (value "NXB0108PWJ")
      (footprint "eagle-import:TSSOP-20")
      (libsource (lib "eagle-import") (part "NXB0108PWJ"))
    )
    (comp (ref "U$3")
      (value "NXB0108PWJ")
      (footprint "eagle-import:TSSOP-20")
      (libsource (lib "eagle-import") (part "NXB0108PWJ"))
    )
    (comp (ref "USB")
      (value "FT2232HL")
      (footprint "eagle-import:LQFP64")
      (libsource (lib "eagle-import") (part "FT2232HL"))
    )
    (comp (ref "USB_CONN")
      (value "USBMINIB")
      (footprint "eagle-import:USB-MINIB")
      (libsource (lib "eagle-import") (part "USBMINIB"))
    )
    (comp (ref "C155")
      (value "100n")
      (footprint "eagle-import:C0805")
      (libsource (lib "eagle-import") (part "C-EUC0805"))
    )
    (comp (ref "C156")
      (value "1u")
      (footprint "eagle-import:C0805")
      (libsource (lib "eagle-import") (part "C-EUC0805"))
    )
    (comp (ref "C157")
      (value "100n")
      (footprint "eagle-import:C0805")
      (libsource (lib "eagle-import") (part "C-EUC0805"))
    )
    (comp (ref "C158")
      (value "100n")
      (footprint "eagle-import:C0805")
      (libsource (lib "eagle-import") (part "C-EUC0805"))
    )
    (comp (ref "C159")
      (value "100n")
      (footprint "eagle-import:C0805")
      (libsource (lib "eagle-import") (part "C-EUC0805"))
    )
    (comp (ref "C160")
      (value "100n")
      (footprint "eagle-import:C0805")
      (libsource (lib "eagle-import") (part "C-EUC0805"))
    )
    (comp (ref "C161")
      (value "100n")
      (footprint "eagle-import:C0805")
      (libsource (lib "eagle-import") (part "C-EUC0805"))
    )
    (comp (ref "C162")
      (value "1u")
      (footprint "eagle-import:C0805")
      (libsource (lib "eagle-import") (part "C-EUC0805"))
    )
    (comp (ref "C163")
      (value "100n")
      (footprint "eagle-import:C0805")
      (libsource (lib "eagle-import") (part "C-EUC0805"))
    )
    (comp (ref "C164")
      (value "100n")
      (footprint "eagle-import:C0805")
      (libsource (lib "eagle-import") (part "C-EUC0805"))
    )
    (comp (ref "C165")
      (value "100n")
      (footprint "eagle-import:C0805")
      (libsource (lib "eagle-import") (part "C-EUC0805"))
    )
    (comp (ref "C166")
      (value "100n")
      (footprint "eagle-import:C0805")
      (libsource (lib "eagle-import") (part "C-EUC0805"))
    )
    (comp (ref "C167")
      (value "100n")
      (footprint "eagle-import:C0805")
      (libsource (lib "eagle-import") (part "C-EUC0805"))
    )
    (comp (ref "C168")
      (value "100n")
      (footprint "eagle-import:C0805")
      (libsource (lib "eagle-import") (part "C-EUC0805"))
    )
    (comp (ref "C169")
      (value "6n8")
      (footprint "eagle-import:C0805")
      (libsource (lib "eagle-import") (part "C-EUC0805"))
    )
    (comp (ref "C170")
      (value "68n")
      (footprint "eagle-import:C0805")
      (libsource (lib "eagle-import") (part "C-EUC0805"))
    )
    (comp (ref "C171")
      (value "6n8")
      (footprint "eagle-import:C0805")
      (libsource (lib "eagle-import") (part "C-EUC0805"))
    )
    (comp (ref "C172")
      (value "1u")
      (footprint "eagle-import:C0805")
      (libsource (lib "eagle-import") (part "C-EUC0805"))
    )
    (comp (ref "C173")
      (value "33n")
      (footprint "eagle-import:C0805")
      (libsource (lib "eagle-import") (part "C-EUC0805"))
    )
    (comp (ref "C174")
      (value "3n3")
      (footprint "eagle-import:C0805")
      (libsource (lib "eagle-import") (part "C-EUC0805"))
    )
    (comp (ref "C175")
      (value "3n3")
      (footprint "eagle-import:C0805")
      (libsource (lib "eagle-import") (part "C-EUC0805"))
    )
    (comp (ref "CON_STAMP4")
      (value "IL-AG5-10P-S3T2")
      (footprint "eagle-import:IL-AG5-10P-S3T2")
      (libsource (lib "eagle-import") (part "IL-AG5-10P-S3T2"))
    )
    (comp (ref "R138")
      (value "4k7")
      (footprint "eagle-import:R0805")
      (libsource (lib "eagle-import") (part "rcl_334_R-EU_R0805"))
    )
    (comp (ref "R139")
      (value "1k 0.1%")
      (footprint "eagle-import:R0805")
      (libsource (lib "eagle-import") (part "rcl_334_R-EU_R0805"))
    )
    (comp (ref "R140")
      (value "47")
      (footprint "eagle-import:R0805")
      (libsource (lib "eagle-import") (part "rcl_334_R-EU_R0805"))
    )
    (comp (ref "R141")
      (value "40 1%")
      (footprint "eagle-import:R0805")
      (libsource (lib "eagle-import") (part "rcl_334_R-EU_R0805"))
    )
    (comp (ref "R142")
      (value "40 1%")
      (footprint "eagle-import:R0805")
      (libsource (lib "eagle-import") (part "rcl_334_R-EU_R0805"))
    )
    (comp (ref "R143")
      (value "1k 0.1%")
      (footprint "eagle-import:R0805")
      (libsource (lib "eagle-import") (part "rcl_334_R-EU_R0805"))
    )
    (comp (ref "R144")
      (value "4k7")
      (footprint "eagle-import:R0805")
      (libsource (lib "eagle-import") (part "rcl_334_R-EU_R0805"))
    )
    (comp (ref "R145")
      (value "1k 0.1%")
      (footprint "eagle-import:R0805")
      (libsource (lib "eagle-import") (part "rcl_334_R-EU_R0805"))
    )
    (comp (ref "R146")
      (value "47")
      (footprint "eagle-import:R0805")
      (libsource (lib "eagle-import") (part "rcl_334_R-EU_R0805"))
    )
    (comp (ref "R147")
      (value "40 1%")
      (footprint "eagle-import:R0805")
      (libsource (lib "eagle-import") (part "rcl_334_R-EU_R0805"))
    )
    (comp (ref "R148")
      (value "40 1%")
      (footprint "eagle-import:R0805")
      (libsource (lib "eagle-import") (part "rcl_334_R-EU_R0805"))
    )
    (comp (ref "R149")
      (value "1k 0.1%")
      (footprint "eagle-import:R0805")
      (libsource (lib "eagle-import") (part "rcl_334_R-EU_R0805"))
    )
    (comp (ref "R150")
      (value "47")
      (footprint "eagle-import:R0805")
      (libsource (lib "eagle-import") (part "rcl_334_R-EU_R0805"))
    )
    (comp (ref "R151")
      (value "4k7")
      (footprint "eagle-import:R0805")
      (libsource (lib "eagle-import") (part "rcl_334_R-EU_R0805"))
    )
    (comp (ref "R152")
      (value "4k7 1%")
      (footprint "eagle-import:R0805")
      (libsource (lib "eagle-import") (part "rcl_334_R-EU_R0805"))
    )
    (comp (ref "R153")
      (value "4k7 1%")
      (footprint "eagle-import:R0805")
      (libsource (lib "eagle-import") (part "rcl_334_R-EU_R0805"))
    )
    (comp (ref "R154")
      (value "9k09 1%")
      (footprint "eagle-import:R0805")
      (libsource (lib "eagle-import") (part "rcl_334_R-EU_R0805"))
    )
    (comp (ref "R155")
      (value "9k09 1%")
      (footprint "eagle-import:R0805")
      (libsource (lib "eagle-import") (part "rcl_334_R-EU_R0805"))
    )
    (comp (ref "R156")
      (value "820 0.1%")
      (footprint "eagle-import:R0805")
      (libsource (lib "eagle-import") (part "rcl_334_R-EU_R0805"))
    )
    (comp (ref "STAMP4_ADC_SG1")
      (value "ADS1148QPWRQ1")
      (footprint "eagle-import:TSSOP28")
      (libsource (lib "eagle-import") (part "ADS1148QPWRQ1"))
    )
    (comp (ref "STAMP4_ADC_SG2")
      (value "ADS1148QPWRQ1")
      (footprint "eagle-import:TSSOP28")
      (libsource (lib "eagle-import") (part "ADS1148QPWRQ1"))
    )
    (comp (ref "STAMP4_ADC_TEMP")
      (value "ADS1148QPWRQ1")
      (footprint "eagle-import:TSSOP28")
      (libsource (lib "eagle-import") (part "ADS1148QPWRQ1"))
    )
    (comp (ref "U$15")
      (value "COMMON_MODE_CHOKE")
      (footprint "eagle-import:COMMON_MODE_CHOKE")
      (libsource (lib "eagle-import") (part "COMMON_MODE_CHOKE"))
    )
    (comp (ref "U$16")
      (value "COMMON_MODE_CHOKE")
      (footprint "eagle-import:COMMON_MODE_CHOKE")
      (libsource (lib "eagle-import") (part "COMMON_MODE_CHOKE"))
    )
    (comp (ref "C113")
      (value "100n")
      (footprint "eagle-import:C0805")
      (libsource (lib "eagle-import") (part "C-EUC0805"))
    )
    (comp (ref "C114")
      (value "1u")
      (footprint "eagle-import:C0805")
      (libsource (lib "eagle-import") (part "C-EUC0805"))
    )
    (comp (ref "C115")
      (value "100n")
      (footprint "eagle-import:C0805")
      (libsource (lib "eagle-import") (part "C-EUC0805"))
    )
    (comp (ref "C116")
      (value "100n")
      (footprint "eagle-import:C0805")
      (libsource (lib "eagle-import") (part "C-EUC0805"))
    )
    (comp (ref "C117")
      (value "100n")
      (footprint "eagle-import:C0805")
      (libsource (lib "eagle-import") (part "C-EUC0805"))
    )
    (comp (ref "C118")
      (value "100n")
      (footprint "eagle-import:C0805")
      (libsource (lib "eagle-import") (part "C-EUC0805"))
    )
    (comp (ref "C119")
      (value "100n")
      (footprint "eagle-import:C0805")
      (libsource (lib "eagle-import") (part "C-EUC0805"))
    )
    (comp (ref "C120")
      (value "1u")
      (footprint "eagle-import:C0805")
      (libsource (lib "eagle-import") (part "C-EUC0805"))
    )
    (comp (ref "C121")
      (value "100n")
      (footprint "eagle-import:C0805")
      (libsource (lib "eagle-import") (part "C-EUC0805"))
    )
    (comp (ref "C122")
      (value "100n")
      (footprint "eagle-import:C0805")
      (libsource (lib "eagle-import") (part "C-EUC0805"))
    )
    (comp (ref "C123")
      (value "100n")
      (footprint "eagle-import:C0805")
      (libsource (lib "eagle-import") (part "C-EUC0805"))
    )
    (comp (ref "C124")
      (value "100n")
      (footprint "eagle-import:C0805")
      (libsource (lib "eagle-import") (part "C-EUC0805"))
    )
    (comp (ref "C125")
      (value "100n")
      (footprint "eagle-import:C0805")
      (libsource (lib "eagle-import") (part "C-EUC0805"))
    )
    (comp (ref "C126")
      (value "100n")
      (footprint "eagle-import:C0805")
      (libsource (lib "eagle-import") (part "C-EUC0805"))
    )
    (comp (ref "C127")
      (value "6n8")
      (footprint "eagle-import:C0805")
      (libsource (lib "eagle-import") (part "C-EUC0805"))
    )
    (comp (ref "C128")
      (value "68n")
      (footprint "eagle-import:C0805")
      (libsource (lib "eagle-import") (part "C-EUC0805"))
    )
    (comp (ref "C129")
      (value "6n8")
      (footprint "eagle-import:C0805")
      (libsource (lib "eagle-import") (part "C-EUC0805"))
    )
    (comp (ref "C130")
      (value "1u")
      (footprint "eagle-import:C0805")
      (libsource (lib "eagle-import") (part "C-EUC0805"))
    )
    (comp (ref "C131")
      (value "33n")
      (footprint "eagle-import:C0805")
      (libsource (lib "eagle-import") (part "C-EUC0805"))
    )
    (comp (ref "C132")
      (value "3n3")
      (footprint "eagle-import:C0805")
      (libsource (lib "eagle-import") (part "C-EUC0805"))
    )
    (comp (ref "C133")
      (value "3n3")
      (footprint "eagle-import:C0805")
      (libsource (lib "eagle-import") (part "C-EUC0805"))
    )
    (comp (ref "CON_STAMP5")
      (value "IL-AG5-10P-S3T2")
      (footprint "eagle-import:IL-AG5-10P-S3T2")
      (libsource (lib "eagle-import") (part "IL-AG5-10P-S3T2"))
    )
    (comp (ref "R100")
      (value "4k7")
      (footprint "eagle-import:R0805")
      (libsource (lib "eagle-import") (part "rcl_334_R-EU_R0805"))
    )
    (comp (ref "R101")
      (value "1k 0.1%")
      (footprint "eagle-import:R0805")
      (libsource (lib "eagle-import") (part "rcl_334_R-EU_R0805"))
    )
    (comp (ref "R102")
      (value "47")
      (footprint "eagle-import:R0805")
      (libsource (lib "eagle-import") (part "rcl_334_R-EU_R0805"))
    )
    (comp (ref "R103")
      (value "40 1%")
      (footprint "eagle-import:R0805")
      (libsource (lib "eagle-import") (part "rcl_334_R-EU_R0805"))
    )
    (comp (ref "R104")
      (value "40 1%")
      (footprint "eagle-import:R0805")
      (libsource (lib "eagle-import") (part "rcl_334_R-EU_R0805"))
    )
    (comp (ref "R105")
      (value "1k 0.1%")
      (footprint "eagle-import:R0805")
      (libsource (lib "eagle-import") (part "rcl_334_R-EU_R0805"))
    )
    (comp (ref "R106")
      (value "4k7")
      (footprint "eagle-import:R0805")
      (libsource (lib "eagle-import") (part "rcl_334_R-EU_R0805"))
    )
    (comp (ref "R107")
      (value "1k 0.1%")
      (footprint "eagle-import:R0805")
      (libsource (lib "eagle-import") (part "rcl_334_R-EU_R0805"))
    )
    (comp (ref "R108")
      (value "47")
      (footprint "eagle-import:R0805")
      (libsource (lib "eagle-import") (part "rcl_334_R-EU_R0805"))
    )
    (comp (ref "R109")
      (value "40 1%")
      (footprint "eagle-import:R0805")
      (libsource (lib "eagle-import") (part "rcl_334_R-EU_R0805"))
    )
    (comp (ref "R110")
      (value "40 1%")
      (footprint "eagle-import:R0805")
      (libsource (lib "eagle-import") (part "rcl_334_R-EU_R0805"))
    )
    (comp (ref "R111")
      (value "1k 0.1%")
      (footprint "eagle-import:R0805")
      (libsource (lib "eagle-import") (part "rcl_334_R-EU_R0805"))
    )
    (comp (ref "R112")
      (value "47")
      (footprint "eagle-import:R0805")
      (libsource (lib "eagle-import") (part "rcl_334_R-EU_R0805"))
    )
    (comp (ref "R113")
      (value "4k7")
      (footprint "eagle-import:R0805")
      (libsource (lib "eagle-import") (part "rcl_334_R-EU_R0805"))
    )
    (comp (ref "R114")
      (value "4k7 1%")
      (footprint "eagle-import:R0805")
      (libsource (lib "eagle-import") (part "rcl_334_R-EU_R0805"))
    )
    (comp (ref "R115")
      (value "4k7 1%")
      (footprint "eagle-import:R0805")
      (libsource (lib "eagle-import") (part "rcl_334_R-EU_R0805"))
    )
    (comp (ref "R116")
      (value "9k09 1%")
      (footprint "eagle-import:R0805")
      (libsource (lib "eagle-import") (part "rcl_334_R-EU_R0805"))
    )
    (comp (ref "R117")
      (value "9k09 1%")
      (footprint "eagle-import:R0805")
      (libsource (lib "eagle-import") (part "rcl_334_R-EU_R0805"))
    )
    (comp (ref "R118")
      (value "820 0.1%")
      (footprint "eagle-import:R0805")
      (libsource (lib "eagle-import") (part "rcl_334_R-EU_R0805"))
    )
    (comp (ref "STAMP5_ADC_SG1")
      (value "ADS1148QPWRQ1")
      (footprint "eagle-import:TSSOP28")
      (libsource (lib "eagle-import") (part "ADS1148QPWRQ1"))
    )
    (comp (ref "STAMP5_ADC_SG2")
      (value "ADS1148QPWRQ1")
      (footprint "eagle-import:TSSOP28")
      (libsource (lib "eagle-import") (part "ADS1148QPWRQ1"))
    )
    (comp (ref "STAMP5_ADC_TEMP")
      (value "ADS1148QPWRQ1")
      (footprint "eagle-import:TSSOP28")
      (libsource (lib "eagle-import") (part "ADS1148QPWRQ1"))
    )
    (comp (ref "U$11")
      (value "COMMON_MODE_CHOKE")
      (footprint "eagle-import:COMMON_MODE_CHOKE")
      (libsource (lib "eagle-import") (part "COMMON_MODE_CHOKE"))
    )
    (comp (ref "U$12")
      (value "COMMON_MODE_CHOKE")
      (footprint "eagle-import:COMMON_MODE_CHOKE")
      (libsource (lib "eagle-import") (part "COMMON_MODE_CHOKE"))
    )
    (comp (ref "C33")
      (value "100n")
      (footprint "eagle-import:C0805")
      (libsource (lib "eagle-import") (part "C-EUC0805"))
    )
    (comp (ref "C34")
      (value "1u")
      (footprint "eagle-import:C0805")
      (libsource (lib "eagle-import") (part "C-EUC0805"))
    )
    (comp (ref "C45")
      (value "100n")
      (footprint "eagle-import:C0805")
      (libsource (lib "eagle-import") (part "C-EUC0805"))
    )
    (comp (ref "C46")
      (value "100n")
      (footprint "eagle-import:C0805")
      (libsource (lib "eagle-import") (part "C-EUC0805"))
    )
    (comp (ref "C47")
      (value "100n")
      (footprint "eagle-import:C0805")
      (libsource (lib "eagle-import") (part "C-EUC0805"))
    )
    (comp (ref "C48")
      (value "100n")
      (footprint "eagle-import:C0805")
      (libsource (lib "eagle-import") (part "C-EUC0805"))
    )
    (comp (ref "C49")
      (value "100n")
      (footprint "eagle-import:C0805")
      (libsource (lib "eagle-import") (part "C-EUC0805"))
    )
    (comp (ref "C50")
      (value "1u")
      (footprint "eagle-import:C0805")
      (libsource (lib "eagle-import") (part "C-EUC0805"))
    )
    (comp (ref "C51")
      (value "100n")
      (footprint "eagle-import:C0805")
      (libsource (lib "eagle-import") (part "C-EUC0805"))
    )
    (comp (ref "C52")
      (value "100n")
      (footprint "eagle-import:C0805")
      (libsource (lib "eagle-import") (part "C-EUC0805"))
    )
    (comp (ref "C53")
      (value "100n")
      (footprint "eagle-import:C0805")
      (libsource (lib "eagle-import") (part "C-EUC0805"))
    )
    (comp (ref "C54")
      (value "100n")
      (footprint "eagle-import:C0805")
      (libsource (lib "eagle-import") (part "C-EUC0805"))
    )
    (comp (ref "C55")
      (value "100n")
      (footprint "eagle-import:C0805")
      (libsource (lib "eagle-import") (part "C-EUC0805"))
    )
    (comp (ref "C56")
      (value "100n")
      (footprint "eagle-import:C0805")
      (libsource (lib "eagle-import") (part "C-EUC0805"))
    )
    (comp (ref "C57")
      (value "6n8")
      (footprint "eagle-import:C0805")
      (libsource (lib "eagle-import") (part "C-EUC0805"))
    )
    (comp (ref "C58")
      (value "68n")
      (footprint "eagle-import:C0805")
      (libsource (lib "eagle-import") (part "C-EUC0805"))
    )
    (comp (ref "C59")
      (value "6n8")
      (footprint "eagle-import:C0805")
      (libsource (lib "eagle-import") (part "C-EUC0805"))
    )
    (comp (ref "C63")
      (value "1u")
      (footprint "eagle-import:C0805")
      (libsource (lib "eagle-import") (part "C-EUC0805"))
    )
    (comp (ref "C68")
      (value "33n")
      (footprint "eagle-import:C0805")
      (libsource (lib "eagle-import") (part "C-EUC0805"))
    )
    (comp (ref "C69")
      (value "3n3")
      (footprint "eagle-import:C0805")
      (libsource (lib "eagle-import") (part "C-EUC0805"))
    )
    (comp (ref "C70")
      (value "3n3")
      (footprint "eagle-import:C0805")
      (libsource (lib "eagle-import") (part "C-EUC0805"))
    )
    (comp (ref "CON_STAMP1")
      (value "IL-AG5-10P-S3T2")
      (footprint "eagle-import:IL-AG5-10P-S3T2")
      (libsource (lib "eagle-import") (part "IL-AG5-10P-S3T2"))
    )
    (comp (ref "R28")
      (value "4k7")
      (footprint "eagle-import:R0805")
      (libsource (lib "eagle-import") (part "rcl_334_R-EU_R0805"))
    )
    (comp (ref "R29")
      (value "40 1%")
      (footprint "eagle-import:R0805")
      (libsource (lib "eagle-import") (part "rcl_334_R-EU_R0805"))
    )
    (comp (ref "R30")
      (value "1k 0.1%")
      (footprint "eagle-import:R0805")
      (libsource (lib "eagle-import") (part "rcl_334_R-EU_R0805"))
    )
    (comp (ref "R31")
      (value "47")
      (footprint "eagle-import:R0805")
      (libsource (lib "eagle-import") (part "rcl_334_R-EU_R0805"))
    )
    (comp (ref "R32")
      (value "40 1%")
      (footprint "eagle-import:R0805")
      (libsource (lib "eagle-import") (part "rcl_334_R-EU_R0805"))
    )
    (comp (ref "R33")
      (value "1k 0.1%")
      (footprint "eagle-import:R0805")
      (libsource (lib "eagle-import") (part "rcl_334_R-EU_R0805"))
    )
    (comp (ref "R68")
      (value "4k7")
      (footprint "eagle-import:R0805")
      (libsource (lib "eagle-import") (part "rcl_334_R-EU_R0805"))
    )
    (comp (ref "R69")
      (value "1k 0.1%")
      (footprint "eagle-import:R0805")
      (libsource (lib "eagle-import") (part "rcl_334_R-EU_R0805"))
    )
    (comp (ref "R70")
      (value "47")
      (footprint "eagle-import:R0805")
      (libsource (lib "eagle-import") (part "rcl_334_R-EU_R0805"))
    )
    (comp (ref "R72")
      (value "40 1%")
      (footprint "eagle-import:R0805")
      (libsource (lib "eagle-import") (part "rcl_334_R-EU_R0805"))
    )
    (comp (ref "R73")
      (value "40 1%")
      (footprint "eagle-import:R0805")
      (libsource (lib "eagle-import") (part "rcl_334_R-EU_R0805"))
    )
    (comp (ref "R74")
      (value "1k 0.1%")
      (footprint "eagle-import:R0805")
      (libsource (lib "eagle-import") (part "rcl_334_R-EU_R0805"))
    )
    (comp (ref "R75")
      (value "47")
      (footprint "eagle-import:R0805")
      (libsource (lib "eagle-import") (part "rcl_334_R-EU_R0805"))
    )
    (comp (ref "R77")
      (value "4k7")
      (footprint "eagle-import:R0805")
      (libsource (lib "eagle-import") (part "rcl_334_R-EU_R0805"))
    )
    (comp (ref "R78")
      (value "4k7 1%")
      (footprint "eagle-import:R0805")
      (libsource (lib "eagle-import") (part "rcl_334_R-EU_R0805"))
    )
    (comp (ref "R79")
      (value "4k7 1%")
      (footprint "eagle-import:R0805")
      (libsource (lib "eagle-import") (part "rcl_334_R-EU_R0805"))
    )
    (comp (ref "R80")
      (value "9k09 1%")
      (footprint "eagle-import:R0805")
      (libsource (lib "eagle-import") (part "rcl_334_R-EU_R0805"))
    )
    (comp (ref "R81")
      (value "9k09 1%")
      (footprint "eagle-import:R0805")
      (libsource (lib "eagle-import") (part "rcl_334_R-EU_R0805"))
    )
    (comp (ref "R82")
      (value "820 0.1%")
      (footprint "eagle-import:R0805")
      (libsource (lib "eagle-import") (part "rcl_334_R-EU_R0805"))
    )
    (comp (ref "STAMP1_ADC_SG1")
      (value "ADS1148QPWRQ1")
      (footprint "eagle-import:TSSOP28")
      (libsource (lib "eagle-import") (part "ADS1148QPWRQ1"))
    )
    (comp (ref "STAMP1_ADC_SG2")
      (value "ADS1148QPWRQ1")
      (footprint "eagle-import:TSSOP28")
      (libsource (lib "eagle-import") (part "ADS1148QPWRQ1"))
    )
    (comp (ref "STAMP1_ADC_TEMP")
      (value "ADS1148QPWRQ1")
      (footprint "eagle-import:TSSOP28")
      (libsource (lib "eagle-import") (part "ADS1148QPWRQ1"))
    )
    (comp (ref "U$6")
      (value "COMMON_MODE_CHOKE")
      (footprint "eagle-import:COMMON_MODE_CHOKE")
      (libsource (lib "eagle-import") (part "COMMON_MODE_CHOKE"))
    )
    (comp (ref "U$7")
      (value "COMMON_MODE_CHOKE")
      (footprint "eagle-import:COMMON_MODE_CHOKE")
      (libsource (lib "eagle-import") (part "COMMON_MODE_CHOKE"))
    )
    (comp (ref "C197")
      (value "100n")
      (footprint "eagle-import:C0805")
      (libsource (lib "eagle-import") (part "C-EUC0805"))
    )
    (comp (ref "C198")
      (value "1u")
      (footprint "eagle-import:C0805")
      (libsource (lib "eagle-import") (part "C-EUC0805"))
    )
    (comp (ref "C199")
      (value "100n")
      (footprint "eagle-import:C0805")
      (libsource (lib "eagle-import") (part "C-EUC0805"))
    )
    (comp (ref "C200")
      (value "100n")
      (footprint "eagle-import:C0805")
      (libsource (lib "eagle-import") (part "C-EUC0805"))
    )
    (comp (ref "C201")
      (value "100n")
      (footprint "eagle-import:C0805")
      (libsource (lib "eagle-import") (part "C-EUC0805"))
    )
    (comp (ref "C202")
      (value "100n")
      (footprint "eagle-import:C0805")
      (libsource (lib "eagle-import") (part "C-EUC0805"))
    )
    (comp (ref "C203")
      (value "100n")
      (footprint "eagle-import:C0805")
      (libsource (lib "eagle-import") (part "C-EUC0805"))
    )
    (comp (ref "C204")
      (value "1u")
      (footprint "eagle-import:C0805")
      (libsource (lib "eagle-import") (part "C-EUC0805"))
    )
    (comp (ref "C205")
      (value "100n")
      (footprint "eagle-import:C0805")
      (libsource (lib "eagle-import") (part "C-EUC0805"))
    )
    (comp (ref "C206")
      (value "100n")
      (footprint "eagle-import:C0805")
      (libsource (lib "eagle-import") (part "C-EUC0805"))
    )
    (comp (ref "C207")
      (value "100n")
      (footprint "eagle-import:C0805")
      (libsource (lib "eagle-import") (part "C-EUC0805"))
    )
    (comp (ref "C208")
      (value "100n")
      (footprint "eagle-import:C0805")
      (libsource (lib "eagle-import") (part "C-EUC0805"))
    )
    (comp (ref "C209")
      (value "100n")
      (footprint "eagle-import:C0805")
      (libsource (lib "eagle-import") (part "C-EUC0805"))
    )
    (comp (ref "C210")
      (value "100n")
      (footprint "eagle-import:C0805")
      (libsource (lib "eagle-import") (part "C-EUC0805"))
    )
    (comp (ref "C211")
      (value "6n8")
      (footprint "eagle-import:C0805")
      (libsource (lib "eagle-import") (part "C-EUC0805"))
    )
    (comp (ref "C212")
      (value "68n")
      (footprint "eagle-import:C0805")
      (libsource (lib "eagle-import") (part "C-EUC0805"))
    )
    (comp (ref "C213")
      (value "6n8")
      (footprint "eagle-import:C0805")
      (libsource (lib "eagle-import") (part "C-EUC0805"))
    )
    (comp (ref "C214")
      (value "1u")
      (footprint "eagle-import:C0805")
      (libsource (lib "eagle-import") (part "C-EUC0805"))
    )
    (comp (ref "C215")
      (value "33n")
      (footprint "eagle-import:C0805")
      (libsource (lib "eagle-import") (part "C-EUC0805"))
    )
    (comp (ref "C216")
      (value "3n3")
      (footprint "eagle-import:C0805")
      (libsource (lib "eagle-import") (part "C-EUC0805"))
    )
    (comp (ref "C217")
      (value "3n3")
      (footprint "eagle-import:C0805")
      (libsource (lib "eagle-import") (part "C-EUC0805"))
    )
    (comp (ref "CON_STAMP6")
      (value "IL-AG5-10P-S3T2")
      (footprint "eagle-import:IL-AG5-10P-S3T2")
      (libsource (lib "eagle-import") (part "IL-AG5-10P-S3T2"))
    )
    (comp (ref "R176")
      (value "4k7")
      (footprint "eagle-import:R0805")
      (libsource (lib "eagle-import") (part "rcl_334_R-EU_R0805"))
    )
    (comp (ref "R177")
      (value "1k 0.1%")
      (footprint "eagle-import:R0805")
      (libsource (lib "eagle-import") (part "rcl_334_R-EU_R0805"))
    )
    (comp (ref "R178")
      (value "47")
      (footprint "eagle-import:R0805")
      (libsource (lib "eagle-import") (part "rcl_334_R-EU_R0805"))
    )
    (comp (ref "R179")
      (value "40 1%")
      (footprint "eagle-import:R0805")
      (libsource (lib "eagle-import") (part "rcl_334_R-EU_R0805"))
    )
    (comp (ref "R180")
      (value "40 1%")
      (footprint "eagle-import:R0805")
      (libsource (lib "eagle-import") (part "rcl_334_R-EU_R0805"))
    )
    (comp (ref "R181")
      (value "1k 0.1%")
      (footprint "eagle-import:R0805")
      (libsource (lib "eagle-import") (part "rcl_334_R-EU_R0805"))
    )
    (comp (ref "R182")
      (value "4k7")
      (footprint "eagle-import:R0805")
      (libsource (lib "eagle-import") (part "rcl_334_R-EU_R0805"))
    )
    (comp (ref "R183")
      (value "1k 0.1%")
      (footprint "eagle-import:R0805")
      (libsource (lib "eagle-import") (part "rcl_334_R-EU_R0805"))
    )
    (comp (ref "R184")
      (value "47")
      (footprint "eagle-import:R0805")
      (libsource (lib "eagle-import") (part "rcl_334_R-EU_R0805"))
    )
    (comp (ref "R185")
      (value "40 1%")
      (footprint "eagle-import:R0805")
      (libsource (lib "eagle-import") (part "rcl_334_R-EU_R0805"))
    )
    (comp (ref "R186")
      (value "40 1%")
      (footprint "eagle-import:R0805")
      (libsource (lib "eagle-import") (part "rcl_334_R-EU_R0805"))
    )
    (comp (ref "R187")
      (value "1k 0.1%")
      (footprint "eagle-import:R0805")
      (libsource (lib "eagle-import") (part "rcl_334_R-EU_R0805"))
    )
    (comp (ref "R188")
      (value "47")
      (footprint "eagle-import:R0805")
      (libsource (lib "eagle-import") (part "rcl_334_R-EU_R0805"))
    )
    (comp (ref "R189")
      (value "4k7")
      (footprint "eagle-import:R0805")
      (libsource (lib "eagle-import") (part "rcl_334_R-EU_R0805"))
    )
    (comp (ref "R190")
      (value "4k7 1%")
      (footprint "eagle-import:R0805")
      (libsource (lib "eagle-import") (part "rcl_334_R-EU_R0805"))
    )
    (comp (ref "R191")
      (value "4k7 1%")
      (footprint "eagle-import:R0805")
      (libsource (lib "eagle-import") (part "rcl_334_R-EU_R0805"))
    )
    (comp (ref "R192")
      (value "9k09 1%")
      (footprint "eagle-import:R0805")
      (libsource (lib "eagle-import") (part "rcl_334_R-EU_R0805"))
    )
    (comp (ref "R193")
      (value "9k09 1%")
      (footprint "eagle-import:R0805")
      (libsource (lib "eagle-import") (part "rcl_334_R-EU_R0805"))
    )
    (comp (ref "R194")
      (value "820 0.1%")
      (footprint "eagle-import:R0805")
      (libsource (lib "eagle-import") (part "rcl_334_R-EU_R0805"))
    )
    (comp (ref "STAMP6_ADC_SG1")
      (value "ADS1148QPWRQ1")
      (footprint "eagle-import:TSSOP28")
      (libsource (lib "eagle-import") (part "ADS1148QPWRQ1"))
    )
    (comp (ref "STAMP6_ADC_SG2")
      (value "ADS1148QPWRQ1")
      (footprint "eagle-import:TSSOP28")
      (libsource (lib "eagle-import") (part "ADS1148QPWRQ1"))
    )
    (comp (ref "STAMP6_ADC_TEMP")
      (value "ADS1148QPWRQ1")
      (footprint "eagle-import:TSSOP28")
      (libsource (lib "eagle-import") (part "ADS1148QPWRQ1"))
    )
    (comp (ref "U$19")
      (value "COMMON_MODE_CHOKE")
      (footprint "eagle-import:COMMON_MODE_CHOKE")
      (libsource (lib "eagle-import") (part "COMMON_MODE_CHOKE"))
    )
    (comp (ref "U$20")
      (value "COMMON_MODE_CHOKE")
      (footprint "eagle-import:COMMON_MODE_CHOKE")
      (libsource (lib "eagle-import") (part "COMMON_MODE_CHOKE"))
    )
    (comp (ref "C134")
      (value "100n")
      (footprint "eagle-import:C0805")
      (libsource (lib "eagle-import") (part "C-EUC0805"))
    )
    (comp (ref "C135")
      (value "1u")
      (footprint "eagle-import:C0805")
      (libsource (lib "eagle-import") (part "C-EUC0805"))
    )
    (comp (ref "C136")
      (value "100n")
      (footprint "eagle-import:C0805")
      (libsource (lib "eagle-import") (part "C-EUC0805"))
    )
    (comp (ref "C137")
      (value "100n")
      (footprint "eagle-import:C0805")
      (libsource (lib "eagle-import") (part "C-EUC0805"))
    )
    (comp (ref "C138")
      (value "100n")
      (footprint "eagle-import:C0805")
      (libsource (lib "eagle-import") (part "C-EUC0805"))
    )
    (comp (ref "C139")
      (value "100n")
      (footprint "eagle-import:C0805")
      (libsource (lib "eagle-import") (part "C-EUC0805"))
    )
    (comp (ref "C140")
      (value "100n")
      (footprint "eagle-import:C0805")
      (libsource (lib "eagle-import") (part "C-EUC0805"))
    )
    (comp (ref "C141")
      (value "1u")
      (footprint "eagle-import:C0805")
      (libsource (lib "eagle-import") (part "C-EUC0805"))
    )
    (comp (ref "C142")
      (value "100n")
      (footprint "eagle-import:C0805")
      (libsource (lib "eagle-import") (part "C-EUC0805"))
    )
    (comp (ref "C143")
      (value "100n")
      (footprint "eagle-import:C0805")
      (libsource (lib "eagle-import") (part "C-EUC0805"))
    )
    (comp (ref "C144")
      (value "100n")
      (footprint "eagle-import:C0805")
      (libsource (lib "eagle-import") (part "C-EUC0805"))
    )
    (comp (ref "C145")
      (value "100n")
      (footprint "eagle-import:C0805")
      (libsource (lib "eagle-import") (part "C-EUC0805"))
    )
    (comp (ref "C146")
      (value "100n")
      (footprint "eagle-import:C0805")
      (libsource (lib "eagle-import") (part "C-EUC0805"))
    )
    (comp (ref "C147")
      (value "100n")
      (footprint "eagle-import:C0805")
      (libsource (lib "eagle-import") (part "C-EUC0805"))
    )
    (comp (ref "C148")
      (value "6n8")
      (footprint "eagle-import:C0805")
      (libsource (lib "eagle-import") (part "C-EUC0805"))
    )
    (comp (ref "C149")
      (value "68n")
      (footprint "eagle-import:C0805")
      (libsource (lib "eagle-import") (part "C-EUC0805"))
    )
    (comp (ref "C150")
      (value "6n8")
      (footprint "eagle-import:C0805")
      (libsource (lib "eagle-import") (part "C-EUC0805"))
    )
    (comp (ref "C151")
      (value "1u")
      (footprint "eagle-import:C0805")
      (libsource (lib "eagle-import") (part "C-EUC0805"))
    )
    (comp (ref "C152")
      (value "33n")
      (footprint "eagle-import:C0805")
      (libsource (lib "eagle-import") (part "C-EUC0805"))
    )
    (comp (ref "C153")
      (value "3n3")
      (footprint "eagle-import:C0805")
      (libsource (lib "eagle-import") (part "C-EUC0805"))
    )
    (comp (ref "C154")
      (value "3n3")
      (footprint "eagle-import:C0805")
      (libsource (lib "eagle-import") (part "C-EUC0805"))
    )
    (comp (ref "CON_STAMP3")
      (value "IL-AG5-10P-S3T2")
      (footprint "eagle-import:IL-AG5-10P-S3T2")
      (libsource (lib "eagle-import") (part "IL-AG5-10P-S3T2"))
    )
    (comp (ref "R119")
      (value "4k7")
      (footprint "eagle-import:R0805")
      (libsource (lib "eagle-import") (part "rcl_334_R-EU_R0805"))
    )
    (comp (ref "R120")
      (value "1k 0.1%")
      (footprint "eagle-import:R0805")
      (libsource (lib "eagle-import") (part "rcl_334_R-EU_R0805"))
    )
    (comp (ref "R121")
      (value "47")
      (footprint "eagle-import:R0805")
      (libsource (lib "eagle-import") (part "rcl_334_R-EU_R0805"))
    )
    (comp (ref "R122")
      (value "40 1%")
      (footprint "eagle-import:R0805")
      (libsource (lib "eagle-import") (part "rcl_334_R-EU_R0805"))
    )
    (comp (ref "R123")
      (value "40 1%")
      (footprint "eagle-import:R0805")
      (libsource (lib "eagle-import") (part "rcl_334_R-EU_R0805"))
    )
    (comp (ref "R124")
      (value "1k 0.1%")
      (footprint "eagle-import:R0805")
      (libsource (lib "eagle-import") (part "rcl_334_R-EU_R0805"))
    )
    (comp (ref "R125")
      (value "4k7")
      (footprint "eagle-import:R0805")
      (libsource (lib "eagle-import") (part "rcl_334_R-EU_R0805"))
    )
    (comp (ref "R126")
      (value "1k 0.1%")
      (footprint "eagle-import:R0805")
      (libsource (lib "eagle-import") (part "rcl_334_R-EU_R0805"))
    )
    (comp (ref "R127")
      (value "47")
      (footprint "eagle-import:R0805")
      (libsource (lib "eagle-import") (part "rcl_334_R-EU_R0805"))
    )
    (comp (ref "R128")
      (value "40 1%")
      (footprint "eagle-import:R0805")
      (libsource (lib "eagle-import") (part "rcl_334_R-EU_R0805"))
    )
    (comp (ref "R129")
      (value "40 1%")
      (footprint "eagle-import:R0805")
      (libsource (lib "eagle-import") (part "rcl_334_R-EU_R0805"))
    )
    (comp (ref "R130")
      (value "1k 0.1%")
      (footprint "eagle-import:R0805")
      (libsource (lib "eagle-import") (part "rcl_334_R-EU_R0805"))
    )
    (comp (ref "R131")
      (value "47")
      (footprint "eagle-import:R0805")
      (libsource (lib "eagle-import") (part "rcl_334_R-EU_R0805"))
    )
    (comp (ref "R132")
      (value "4k7")
      (footprint "eagle-import:R0805")
      (libsource (lib "eagle-import") (part "rcl_334_R-EU_R0805"))
    )
    (comp (ref "R133")
      (value "4k7 1%")
      (footprint "eagle-import:R0805")
      (libsource (lib "eagle-import") (part "rcl_334_R-EU_R0805"))
    )
    (comp (ref "R134")
      (value "4k7 1%")
      (footprint "eagle-import:R0805")
      (libsource (lib "eagle-import") (part "rcl_334_R-EU_R0805"))
    )
    (comp (ref "R135")
      (value "9k09 1%")
      (footprint "eagle-import:R0805")
      (libsource (lib "eagle-import") (part "rcl_334_R-EU_R0805"))
    )
    (comp (ref "R136")
      (value "9k09 1%")
      (footprint "eagle-import:R0805")
      (libsource (lib "eagle-import") (part "rcl_334_R-EU_R0805"))
    )
    (comp (ref "R137")
      (value "820 0.1%")
      (footprint "eagle-import:R0805")
      (libsource (lib "eagle-import") (part "rcl_334_R-EU_R0805"))
    )
    (comp (ref "STAMP3_ADC_SG1")
      (value "ADS1148QPWRQ1")
      (footprint "eagle-import:TSSOP28")
      (libsource (lib "eagle-import") (part "ADS1148QPWRQ1"))
    )
    (comp (ref "STAMP3_ADC_SG2")
      (value "ADS1148QPWRQ1")
      (footprint "eagle-import:TSSOP28")
      (libsource (lib "eagle-import") (part "ADS1148QPWRQ1"))
    )
    (comp (ref "STAMP3_ADC_TEMP")
      (value "ADS1148QPWRQ1")
      (footprint "eagle-import:TSSOP28")
      (libsource (lib "eagle-import") (part "ADS1148QPWRQ1"))
    )
    (comp (ref "U$13")
      (value "COMMON_MODE_CHOKE")
      (footprint "eagle-import:COMMON_MODE_CHOKE")
      (libsource (lib "eagle-import") (part "COMMON_MODE_CHOKE"))
    )
    (comp (ref "U$14")
      (value "COMMON_MODE_CHOKE")
      (footprint "eagle-import:COMMON_MODE_CHOKE")
      (libsource (lib "eagle-import") (part "COMMON_MODE_CHOKE"))
    )
  )
  (nets
    (net (code "7") (name "1V2") (class "Default")
      (node (ref "C10") (pin "1") (pinfunction "1_1") (pintype "passive"))
      (node (ref "C11") (pin "1") (pinfunction "1_1") (pintype "passive"))
      (node (ref "C12") (pin "1") (pinfunction "1_1") (pintype "passive"))
      (node (ref "C13") (pin "1") (pinfunction "1_1") (pintype "passive"))
      (node (ref "C14") (pin "1") (pinfunction "1_1") (pintype "passive"))
      (node (ref "C29") (pin "1") (pinfunction "1_1") (pintype "passive"))
      (node (ref "C7") (pin "1") (pinfunction "1_1") (pintype "passive"))
      (node (ref "C8") (pin "1") (pinfunction "1_1") (pintype "passive"))
      (node (ref "C9") (pin "1") (pinfunction "1_1") (pintype "passive"))
      (node (ref "R42") (pin "1") (pinfunction "1_1") (pintype "passive"))
      (node (ref "SF2_M2S010TQ1") (pin "105") (pinfunction "VDD_105") (pintype "bidirectional"))
      (node (ref "SF2_M2S010TQ1") (pin "114") (pinfunction "VDDI0_114") (pintype "bidirectional"))
      (node (ref "SF2_M2S010TQ1") (pin "12") (pinfunction "VDD_12") (pintype "bidirectional"))
      (node (ref "SF2_M2S010TQ1") (pin "121") (pinfunction "VDD_121") (pintype "bidirectional"))
      (node (ref "SF2_M2S010TQ1") (pin "127") (pinfunction "VDDI0_127") (pintype "bidirectional"))
      (node (ref "SF2_M2S010TQ1") (pin "133") (pinfunction "VDD_133") (pintype "bidirectional"))
      (node (ref "SF2_M2S010TQ1") (pin "138") (pinfunction "VDDI0_138") (pintype "bidirectional"))
      (node (ref "SF2_M2S010TQ1") (pin "25") (pinfunction "VDDI6_25") (pintype "bidirectional"))
      (node (ref "SF2_M2S010TQ1") (pin "31") (pinfunction "VDD_31") (pintype "bidirectional"))
      (node (ref "SF2_M2S010TQ1") (pin "35") (pinfunction "VDDI6_35") (pintype "bidirectional"))
      (node (ref "SF2_M2S010TQ1") (pin "39") (pinfunction "VDD_39") (pintype "bidirectional"))
      (node (ref "SF2_M2S010TQ1") (pin "50") (pinfunction "VDD_50") (pintype "bidirectional"))
      (node (ref "SF2_M2S010TQ1") (pin "95") (pinfunction "VDD_95") (pintype "bidirectional"))
      (node (ref "TPS78512QKVURQ1") (pin "3") (pinfunction "OUT_3") (pintype "bidirectional"))
      (node (ref "U$1") (pin "P10") (pinfunction "OE_P10") (pintype "bidirectional"))
      (node (ref "U$1") (pin "P2") (pinfunction "VCCA_P2") (pintype "bidirectional"))
      (node (ref "U$2") (pin "P10") (pinfunction "OE_P10") (pintype "bidirectional"))
      (node (ref "U$2") (pin "P2") (pinfunction "VCCA_P2") (pintype "bidirectional"))
      (node (ref "U$3") (pin "P10") (pinfunction "OE_P10") (pintype "bidirectional"))
      (node (ref "U$3") (pin "P2") (pinfunction "VCCA_P2") (pintype "bidirectional"))
    )
    (net (code "8") (name "3V3") (class "Default")
      (node (ref "C1") (pin "1") (pinfunction "1_1") (pintype "passive"))
      (node (ref "C100") (pin "1") (pinfunction "1_1") (pintype "passive"))
      (node (ref "C104") (pin "1") (pinfunction "1_1") (pintype "passive"))
      (node (ref "C105") (pin "1") (pinfunction "1_1") (pintype "passive"))
      (node (ref "C113") (pin "1") (pinfunction "1_1") (pintype "passive"))
      (node (ref "C115") (pin "1") (pinfunction "1_1") (pintype "passive"))
      (node (ref "C119") (pin "1") (pinfunction "1_1") (pintype "passive"))
      (node (ref "C121") (pin "1") (pinfunction "1_1") (pintype "passive"))
      (node (ref "C125") (pin "1") (pinfunction "1_1") (pintype "passive"))
      (node (ref "C126") (pin "1") (pinfunction "1_1") (pintype "passive"))
      (node (ref "C134") (pin "1") (pinfunction "1_1") (pintype "passive"))
      (node (ref "C136") (pin "1") (pinfunction "1_1") (pintype "passive"))
      (node (ref "C140") (pin "1") (pinfunction "1_1") (pintype "passive"))
      (node (ref "C142") (pin "1") (pinfunction "1_1") (pintype "passive"))
      (node (ref "C146") (pin "1") (pinfunction "1_1") (pintype "passive"))
      (node (ref "C147") (pin "1") (pinfunction "1_1") (pintype "passive"))
      (node (ref "C15") (pin "1") (pinfunction "1_1") (pintype "passive"))
      (node (ref "C155") (pin "1") (pinfunction "1_1") (pintype "passive"))
      (node (ref "C157") (pin "1") (pinfunction "1_1") (pintype "passive"))
      (node (ref "C16") (pin "1") (pinfunction "1_1") (pintype "passive"))
      (node (ref "C161") (pin "1") (pinfunction "1_1") (pintype "passive"))
      (node (ref "C163") (pin "1") (pinfunction "1_1") (pintype "passive"))
      (node (ref "C167") (pin "1") (pinfunction "1_1") (pintype "passive"))
      (node (ref "C168") (pin "1") (pinfunction "1_1") (pintype "passive"))
      (node (ref "C17") (pin "1") (pinfunction "1_1") (pintype "passive"))
      (node (ref "C18") (pin "1") (pinfunction "1_1") (pintype "passive"))
      (node (ref "C19") (pin "1") (pinfunction "1_1") (pintype "passive"))
      (node (ref "C197") (pin "1") (pinfunction "1_1") (pintype "passive"))
      (node (ref "C199") (pin "1") (pinfunction "1_1") (pintype "passive"))
      (node (ref "C2") (pin "1") (pinfunction "1_1") (pintype "passive"))
      (node (ref "C20") (pin "1") (pinfunction "1_1") (pintype "passive"))
      (node (ref "C203") (pin "1") (pinfunction "1_1") (pintype "passive"))
      (node (ref "C205") (pin "1") (pinfunction "1_1") (pintype "passive"))
      (node (ref "C209") (pin "1") (pinfunction "1_1") (pintype "passive"))
      (node (ref "C210") (pin "1") (pinfunction "1_1") (pintype "passive"))
      (node (ref "C23") (pin "1") (pinfunction "1_1") (pintype "passive"))
      (node (ref "C28") (pin "2") (pinfunction "2_2") (pintype "passive"))
      (node (ref "C31") (pin "2") (pinfunction "2_2") (pintype "passive"))
      (node (ref "C33") (pin "1") (pinfunction "1_1") (pintype "passive"))
      (node (ref "C37") (pin "2") (pinfunction "2_2") (pintype "passive"))
      (node (ref "C41") (pin "+") (pinfunction "+_+") (pintype "passive"))
      (node (ref "C45") (pin "1") (pinfunction "1_1") (pintype "passive"))
      (node (ref "C49") (pin "1") (pinfunction "1_1") (pintype "passive"))
      (node (ref "C51") (pin "1") (pinfunction "1_1") (pintype "passive"))
      (node (ref "C55") (pin "1") (pinfunction "1_1") (pintype "passive"))
      (node (ref "C56") (pin "1") (pinfunction "1_1") (pintype "passive"))
      (node (ref "C67") (pin "+") (pinfunction "+_+") (pintype "passive"))
      (node (ref "C71") (pin "2") (pinfunction "2_2") (pintype "passive"))
      (node (ref "C73") (pin "2") (pinfunction "2_2") (pintype "passive"))
      (node (ref "C92") (pin "1") (pinfunction "1_1") (pintype "passive"))
      (node (ref "C94") (pin "1") (pinfunction "1_1") (pintype "passive"))
      (node (ref "C98") (pin "1") (pinfunction "1_1") (pintype "passive"))
      (node (ref "FT_EEPROM") (pin "6") (pinfunction "ORG_6") (pintype "bidirectional"))
      (node (ref "FT_EEPROM") (pin "8") (pinfunction "VCC_8") (pintype "bidirectional"))
      (node (ref "L1") (pin "1") (pinfunction "1_1") (pintype "passive"))
      (node (ref "L2") (pin "1") (pinfunction "1_1") (pintype "passive"))
      (node (ref "R1") (pin "1") (pinfunction "1_1") (pintype "passive"))
      (node (ref "R100") (pin "2") (pinfunction "2_2") (pintype "passive"))
      (node (ref "R106") (pin "2") (pinfunction "2_2") (pintype "passive"))
      (node (ref "R113") (pin "2") (pinfunction "2_2") (pintype "passive"))
      (node (ref "R119") (pin "2") (pinfunction "2_2") (pintype "passive"))
      (node (ref "R125") (pin "2") (pinfunction "2_2") (pintype "passive"))
      (node (ref "R132") (pin "2") (pinfunction "2_2") (pintype "passive"))
      (node (ref "R138") (pin "2") (pinfunction "2_2") (pintype "passive"))
      (node (ref "R144") (pin "2") (pinfunction "2_2") (pintype "passive"))
      (node (ref "R151") (pin "2") (pinfunction "2_2") (pintype "passive"))
      (node (ref "R176") (pin "2") (pinfunction "2_2") (pintype "passive"))
      (node (ref "R182") (pin "2") (pinfunction "2_2") (pintype "passive"))
      (node (ref "R189") (pin "2") (pinfunction "2_2") (pintype "passive"))
      (node (ref "R2") (pin "1") (pinfunction "1_1") (pintype "passive"))
      (node (ref "R22") (pin "2") (pinfunction "2_2") (pintype "passive"))
      (node (ref "R26") (pin "1") (pinfunction "1_1") (pintype "passive"))
      (node (ref "R27") (pin "2") (pinfunction "2_2") (pintype "passive"))
      (node (ref "R28") (pin "2") (pinfunction "2_2") (pintype "passive"))
      (node (ref "R3") (pin "1") (pinfunction "1_1") (pintype "passive"))
      (node (ref "R4") (pin "2") (pinfunction "2_2") (pintype "passive"))
      (node (ref "R57") (pin "1") (pinfunction "1_1") (pintype "passive"))
      (node (ref "R68") (pin "2") (pinfunction "2_2") (pintype "passive"))
      (node (ref "R71") (pin "2") (pinfunction "2_2") (pintype "passive"))
      (node (ref "R77") (pin "2") (pinfunction "2_2") (pintype "passive"))
      (node (ref "R87") (pin "2") (pinfunction "2_2") (pintype "passive"))
      (node (ref "R94") (pin "2") (pinfunction "2_2") (pintype "passive"))
      (node (ref "RCJ2") (pin "2") (pinfunction "2_2") (pintype "passive"))
      (node (ref "S70FL") (pin "2") (pinfunction "VCC_2") (pintype "bidirectional"))
      (node (ref "SF2_M2S010TQ1") (pin "104") (pinfunction "VPP_104") (pintype "bidirectional"))
      (node (ref "SF2_M2S010TQ1") (pin "17") (pinfunction "VDDI7_17") (pintype "bidirectional"))
      (node (ref "SF2_M2S010TQ1") (pin "41") (pinfunction "VPP_41") (pintype "bidirectional"))
      (node (ref "SF2_M2S010TQ1") (pin "45") (pinfunction "VDDI4_45") (pintype "bidirectional"))
      (node (ref "SF2_M2S010TQ1") (pin "54") (pinfunction "VDDI4_54") (pintype "bidirectional"))
      (node (ref "SF2_M2S010TQ1") (pin "6") (pinfunction "VDDI7_6") (pintype "bidirectional"))
      (node (ref "SF2_M2S010TQ1") (pin "62") (pinfunction "VDDI4_62") (pintype "bidirectional"))
      (node (ref "SF2_M2S010TQ1") (pin "77") (pinfunction "VDDI3_77") (pintype "bidirectional"))
      (node (ref "SF2_M2S010TQ1") (pin "80") (pinfunction "VPP_80") (pintype "bidirectional"))
      (node (ref "SF2_M2S010TQ1") (pin "86") (pinfunction "VDDI2_86") (pintype "bidirectional"))
      (node (ref "SF2_M2S010TQ1") (pin "97") (pinfunction "VPPNVM_97") (pintype "bidirectional"))
      (node (ref "SF2_M2S010TQ1") (pin "99") (pinfunction "VDDI2_99") (pintype "bidirectional"))
      (node (ref "STAMP1_ADC_SG1") (pin "1") (pinfunction "DVDD_1") (pintype "bidirectional"))
      (node (ref "STAMP1_ADC_SG1") (pin "22") (pinfunction "AVDD_22") (pintype "bidirectional"))
      (node (ref "STAMP1_ADC_SG2") (pin "1") (pinfunction "DVDD_1") (pintype "bidirectional"))
      (node (ref "STAMP1_ADC_SG2") (pin "22") (pinfunction "AVDD_22") (pintype "bidirectional"))
      (node (ref "STAMP1_ADC_TEMP") (pin "1") (pinfunction "DVDD_1") (pintype "bidirectional"))
      (node (ref "STAMP1_ADC_TEMP") (pin "22") (pinfunction "AVDD_22") (pintype "bidirectional"))
      (node (ref "STAMP2_ADC_SG1") (pin "1") (pinfunction "DVDD_1") (pintype "bidirectional"))
      (node (ref "STAMP2_ADC_SG1") (pin "22") (pinfunction "AVDD_22") (pintype "bidirectional"))
      (node (ref "STAMP2_ADC_SG2") (pin "1") (pinfunction "DVDD_1") (pintype "bidirectional"))
      (node (ref "STAMP2_ADC_SG2") (pin "22") (pinfunction "AVDD_22") (pintype "bidirectional"))
      (node (ref "STAMP2_ADC_TEMP") (pin "1") (pinfunction "DVDD_1") (pintype "bidirectional"))
      (node (ref "STAMP2_ADC_TEMP") (pin "22") (pinfunction "AVDD_22") (pintype "bidirectional"))
      (node (ref "STAMP3_ADC_SG1") (pin "1") (pinfunction "DVDD_1") (pintype "bidirectional"))
      (node (ref "STAMP3_ADC_SG1") (pin "22") (pinfunction "AVDD_22") (pintype "bidirectional"))
      (node (ref "STAMP3_ADC_SG2") (pin "1") (pinfunction "DVDD_1") (pintype "bidirectional"))
      (node (ref "STAMP3_ADC_SG2") (pin "22") (pinfunction "AVDD_22") (pintype "bidirectional"))
      (node (ref "STAMP3_ADC_TEMP") (pin "1") (pinfunction "DVDD_1") (pintype "bidirectional"))
      (node (ref "STAMP3_ADC_TEMP") (pin "22") (pinfunction "AVDD_22") (pintype "bidirectional"))
      (node (ref "STAMP4_ADC_SG1") (pin "1") (pinfunction "DVDD_1") (pintype "bidirectional"))
      (node (ref "STAMP4_ADC_SG1") (pin "22") (pinfunction "AVDD_22") (pintype "bidirectional"))
      (node (ref "STAMP4_ADC_SG2") (pin "1") (pinfunction "DVDD_1") (pintype "bidirectional"))
      (node (ref "STAMP4_ADC_SG2") (pin "22") (pinfunction "AVDD_22") (pintype "bidirectional"))
      (node (ref "STAMP4_ADC_TEMP") (pin "1") (pinfunction "DVDD_1") (pintype "bidirectional"))
      (node (ref "STAMP4_ADC_TEMP") (pin "22") (pinfunction "AVDD_22") (pintype "bidirectional"))
      (node (ref "STAMP5_ADC_SG1") (pin "1") (pinfunction "DVDD_1") (pintype "bidirectional"))
      (node (ref "STAMP5_ADC_SG1") (pin "22") (pinfunction "AVDD_22") (pintype "bidirectional"))
      (node (ref "STAMP5_ADC_SG2") (pin "1") (pinfunction "DVDD_1") (pintype "bidirectional"))
      (node (ref "STAMP5_ADC_SG2") (pin "22") (pinfunction "AVDD_22") (pintype "bidirectional"))
      (node (ref "STAMP5_ADC_TEMP") (pin "1") (pinfunction "DVDD_1") (pintype "bidirectional"))
      (node (ref "STAMP5_ADC_TEMP") (pin "22") (pinfunction "AVDD_22") (pintype "bidirectional"))
      (node (ref "STAMP6_ADC_SG1") (pin "1") (pinfunction "DVDD_1") (pintype "bidirectional"))
      (node (ref "STAMP6_ADC_SG1") (pin "22") (pinfunction "AVDD_22") (pintype "bidirectional"))
      (node (ref "STAMP6_ADC_SG2") (pin "1") (pinfunction "DVDD_1") (pintype "bidirectional"))
      (node (ref "STAMP6_ADC_SG2") (pin "22") (pinfunction "AVDD_22") (pintype "bidirectional"))
      (node (ref "STAMP6_ADC_TEMP") (pin "1") (pinfunction "DVDD_1") (pintype "bidirectional"))
      (node (ref "STAMP6_ADC_TEMP") (pin "22") (pinfunction "AVDD_22") (pintype "bidirectional"))
      (node (ref "TPS78512QKVURQ1") (pin "1") (pinfunction "EN_1") (pintype "bidirectional"))
      (node (ref "TPS78512QKVURQ1") (pin "2") (pinfunction "IN_2") (pintype "bidirectional"))
      (node (ref "U$1") (pin "P19") (pinfunction "VCCB_P19") (pintype "bidirectional"))
      (node (ref "U$2") (pin "P19") (pinfunction "VCCB_P19") (pintype "bidirectional"))
      (node (ref "U$3") (pin "P19") (pinfunction "VCCB_P19") (pintype "bidirectional"))
      (node (ref "U$5") (pin "P1") (pinfunction "STDBY_P1") (pintype "bidirectional"))
      (node (ref "U$5") (pin "P4") (pinfunction "VDD_P4") (pintype "bidirectional"))
      (node (ref "USB") (pin "20") (pinfunction "VCCIO_20") (pintype "bidirectional"))
      (node (ref "USB") (pin "31") (pinfunction "VCCIO_31") (pintype "bidirectional"))
      (node (ref "USB") (pin "42") (pinfunction "VCCIO_42") (pintype "bidirectional"))
      (node (ref "USB") (pin "50") (pinfunction "VREGIN_50") (pintype "bidirectional"))
      (node (ref "USB") (pin "56") (pinfunction "VCCIO_56") (pintype "bidirectional"))
      (node (ref "U_LT1528") (pin "1") (pinfunction "OUT_1") (pintype "bidirectional"))
      (node (ref "U_LT1528") (pin "2") (pinfunction "SENSE_2") (pintype "bidirectional"))
    )
    (net (code "9") (name "4V096") (class "Default")
      (node (ref "R105") (pin "2") (pinfunction "2_2") (pintype "passive"))
      (node (ref "R111") (pin "2") (pinfunction "2_2") (pintype "passive"))
      (node (ref "R124") (pin "2") (pinfunction "2_2") (pintype "passive"))
      (node (ref "R130") (pin "2") (pinfunction "2_2") (pintype "passive"))
      (node (ref "R143") (pin "2") (pinfunction "2_2") (pintype "passive"))
      (node (ref "R149") (pin "2") (pinfunction "2_2") (pintype "passive"))
      (node (ref "R181") (pin "2") (pinfunction "2_2") (pintype "passive"))
      (node (ref "R187") (pin "2") (pinfunction "2_2") (pintype "passive"))
      (node (ref "R33") (pin "2") (pinfunction "2_2") (pintype "passive"))
      (node (ref "R54") (pin "1") (pinfunction "1_1") (pintype "passive"))
      (node (ref "R74") (pin "2") (pinfunction "2_2") (pintype "passive"))
      (node (ref "R86") (pin "2") (pinfunction "2_2") (pintype "passive"))
      (node (ref "R92") (pin "2") (pinfunction "2_2") (pintype "passive"))
      (node (ref "REF4V096") (pin "P4") (pinfunction "C_P4") (pintype "passive"))
      (node (ref "U$10") (pin "P$5") (pinfunction "5_P$5") (pintype "passive"))
      (node (ref "U$11") (pin "P$5") (pinfunction "5_P$5") (pintype "passive"))
      (node (ref "U$12") (pin "P$5") (pinfunction "5_P$5") (pintype "passive"))
      (node (ref "U$13") (pin "P$5") (pinfunction "5_P$5") (pintype "passive"))
      (node (ref "U$14") (pin "P$5") (pinfunction "5_P$5") (pintype "passive"))
      (node (ref "U$15") (pin "P$5") (pinfunction "5_P$5") (pintype "passive"))
      (node (ref "U$16") (pin "P$5") (pinfunction "5_P$5") (pintype "passive"))
      (node (ref "U$19") (pin "P$5") (pinfunction "5_P$5") (pintype "passive"))
      (node (ref "U$20") (pin "P$5") (pinfunction "5_P$5") (pintype "passive"))
      (node (ref "U$6") (pin "P$5") (pinfunction "5_P$5") (pintype "passive"))
      (node (ref "U$7") (pin "P$5") (pinfunction "5_P$5") (pintype "passive"))
      (node (ref "U$9") (pin "P$5") (pinfunction "5_P$5") (pintype "passive"))
    )
    (net (code "10") (name "5V") (class "Default")
      (node (ref "C35") (pin "2") (pinfunction "2_2") (pintype "passive"))
      (node (ref "C36") (pin "2") (pinfunction "2_2") (pintype "passive"))
      (node (ref "C39") (pin "+") (pinfunction "+_+") (pintype "passive"))
      (node (ref "C40") (pin "+") (pinfunction "+_+") (pintype "passive"))
      (node (ref "C64") (pin "+") (pinfunction "+_+") (pintype "passive"))
      (node (ref "C65") (pin "+") (pinfunction "+_+") (pintype "passive"))
      (node (ref "C66") (pin "+") (pinfunction "+_+") (pintype "passive"))
      (node (ref "R18") (pin "1") (pinfunction "1_1") (pintype "passive"))
      (node (ref "R19") (pin "1") (pinfunction "1_1") (pintype "passive"))
      (node (ref "R20") (pin "1") (pinfunction "1_1") (pintype "passive"))
      (node (ref "R47") (pin "1") (pinfunction "1_1") (pintype "passive"))
      (node (ref "R48") (pin "1") (pinfunction "1_1") (pintype "passive"))
      (node (ref "R49") (pin "1") (pinfunction "1_1") (pintype "passive"))
      (node (ref "R52") (pin "1") (pinfunction "1_1") (pintype "passive"))
      (node (ref "R54") (pin "2") (pinfunction "2_2") (pintype "passive"))
      (node (ref "U_LT1528") (pin "4") (pinfunction "SHDN_4") (pintype "bidirectional"))
      (node (ref "U_LT1528") (pin "5") (pinfunction "IN_5") (pintype "bidirectional"))
      (node (ref "U_TRACODCDC") (pin "3") (pinfunction "+VOUT_3") (pintype "passive"))
    )
    (net (code "11") (name "5V-NONISO") (class "Default")
      (node (ref "C43") (pin "1") (pinfunction "1_1") (pintype "passive"))
      (node (ref "R16") (pin "1") (pinfunction "1_1") (pintype "passive"))
      (node (ref "R25") (pin "2") (pinfunction "2_2") (pintype "passive"))
      (node (ref "U_7805") (pin "1") (pinfunction "VOUT_1") (pintype "bidirectional"))
      (node (ref "U_MAX488") (pin "1") (pinfunction "VCC_1") (pintype "power_in"))
    )
    (net (code "12") (name "28V") (class "Default")
      (node (ref "C38") (pin "+") (pinfunction "+_+") (pintype "passive"))
      (node (ref "C42") (pin "2") (pinfunction "2_2") (pintype "passive"))
      (node (ref "C60") (pin "+") (pinfunction "+_+") (pintype "passive"))
      (node (ref "C61") (pin "+") (pinfunction "+_+") (pintype "passive"))
      (node (ref "C62") (pin "+") (pinfunction "+_+") (pintype "passive"))
      (node (ref "R11") (pin "1") (pinfunction "1_1") (pintype "passive"))
      (node (ref "R12") (pin "1") (pinfunction "1_1") (pintype "passive"))
      (node (ref "R13") (pin "1") (pinfunction "1_1") (pintype "passive"))
      (node (ref "U_7805") (pin "8") (pinfunction "VIN_8") (pintype "bidirectional"))
      (node (ref "U_TRACODCDC") (pin "1") (pinfunction "+VIN_1") (pintype "input"))
      (node (ref "X1") (pin "1") (pinfunction "1_1") (pintype "passive"))
      (node (ref "X1") (pin "9") (pinfunction "9_9") (pintype "passive"))
    )
    (net (code "13") (name "28VGND") (class "Default")
      (node (ref "C38") (pin "-") (pinfunction "-_-") (pintype "passive"))
      (node (ref "C42") (pin "1") (pinfunction "1_1") (pintype "passive"))
      (node (ref "C43") (pin "2") (pinfunction "2_2") (pintype "passive"))
      (node (ref "C44") (pin "2") (pinfunction "2_2") (pintype "passive"))
      (node (ref "C60") (pin "-") (pinfunction "-_-") (pintype "passive"))
      (node (ref "C61") (pin "-") (pinfunction "-_-") (pintype "passive"))
      (node (ref "C62") (pin "-") (pinfunction "-_-") (pintype "passive"))
      (node (ref "D1") (pin "A") (pinfunction "A_A") (pintype "passive"))
      (node (ref "D5") (pin "A") (pinfunction "A_A") (pintype "passive"))
      (node (ref "R17") (pin "1") (pinfunction "1_1") (pintype "passive"))
      (node (ref "R23") (pin "2") (pinfunction "2_2") (pintype "passive"))
      (node (ref "U_7805") (pin "2") (pinfunction "GND_2") (pintype "bidirectional"))
      (node (ref "U_7805") (pin "3") (pinfunction "GND_3") (pintype "bidirectional"))
      (node (ref "U_7805") (pin "6") (pinfunction "GND_6") (pintype "bidirectional"))
      (node (ref "U_7805") (pin "7") (pinfunction "GND_7") (pintype "bidirectional"))
      (node (ref "U_MAX488") (pin "4") (pinfunction "GND_4") (pintype "power_in"))
      (node (ref "U_OPTO_4") (pin "5") (pinfunction "EMT2_5") (pintype "output"))
      (node (ref "U_OPTO_4") (pin "7") (pinfunction "EMT1_7") (pintype "output"))
      (node (ref "U_TRACODCDC") (pin "2") (pinfunction "-VIN_2") (pintype "input"))
      (node (ref "X1") (pin "15") (pinfunction "15_15") (pintype "passive"))
      (node (ref "X1") (pin "8") (pinfunction "8_8") (pintype "passive"))
    )
    (net (code "14") (name "ADC_START") (class "Default")
      (node (ref "STAMP1_ADC_SG1") (pin "23") (pinfunction "START_23") (pintype "bidirectional"))
      (node (ref "STAMP1_ADC_SG2") (pin "23") (pinfunction "START_23") (pintype "bidirectional"))
      (node (ref "STAMP1_ADC_TEMP") (pin "23") (pinfunction "START_23") (pintype "bidirectional"))
      (node (ref "STAMP2_ADC_SG1") (pin "23") (pinfunction "START_23") (pintype "bidirectional"))
      (node (ref "STAMP2_ADC_SG2") (pin "23") (pinfunction "START_23") (pintype "bidirectional"))
      (node (ref "STAMP2_ADC_TEMP") (pin "23") (pinfunction "START_23") (pintype "bidirectional"))
      (node (ref "STAMP3_ADC_SG1") (pin "23") (pinfunction "START_23") (pintype "bidirectional"))
      (node (ref "STAMP3_ADC_SG2") (pin "23") (pinfunction "START_23") (pintype "bidirectional"))
      (node (ref "STAMP3_ADC_TEMP") (pin "23") (pinfunction "START_23") (pintype "bidirectional"))
      (node (ref "STAMP4_ADC_SG1") (pin "23") (pinfunction "START_23") (pintype "bidirectional"))
      (node (ref "STAMP4_ADC_SG2") (pin "23") (pinfunction "START_23") (pintype "bidirectional"))
      (node (ref "STAMP4_ADC_TEMP") (pin "23") (pinfunction "START_23") (pintype "bidirectional"))
      (node (ref "STAMP5_ADC_SG1") (pin "23") (pinfunction "START_23") (pintype "bidirectional"))
      (node (ref "STAMP5_ADC_SG2") (pin "23") (pinfunction "START_23") (pintype "bidirectional"))
      (node (ref "STAMP5_ADC_TEMP") (pin "23") (pinfunction "START_23") (pintype "bidirectional"))
      (node (ref "STAMP6_ADC_SG1") (pin "23") (pinfunction "START_23") (pintype "bidirectional"))
      (node (ref "STAMP6_ADC_SG2") (pin "23") (pinfunction "START_23") (pintype "bidirectional"))
      (node (ref "STAMP6_ADC_TEMP") (pin "23") (pinfunction "START_23") (pintype "bidirectional"))
      (node (ref "U$3") (pin "P13") (pinfunction "B7_P13") (pintype "bidirectional"))
    )
    (net (code "15") (name "ADC_START_1V2") (class "Default")
      (node (ref "SF2_M2S010TQ1") (pin "128") (pinfunction "DDRIO47NB0_128") (pintype "bidirectional"))
      (node (ref "U$3") (pin "P8") (pinfunction "A7_P8") (pintype "bidirectional"))
    )
    (net (code "16") (name "DAPI_CTS") (class "Default")
      (node (ref "U$2") (pin "P14") (pinfunction "B6_P14") (pintype "bidirectional"))
      (node (ref "USB") (pin "40") (pinfunction "BDBUS2_40") (pintype "bidirectional"))
    )
    (net (code "17") (name "DAPI_DSR") (class "Default")
      (node (ref "U$2") (pin "P16") (pinfunction "B4_P16") (pintype "bidirectional"))
      (node (ref "USB") (pin "43") (pinfunction "BDBUS4_43") (pintype "bidirectional"))
    )
    (net (code "18") (name "DAPI_DTR") (class "Default")
      (node (ref "U$2") (pin "P17") (pinfunction "B3_P17") (pintype "bidirectional"))
      (node (ref "USB") (pin "44") (pinfunction "BDBUS5_44") (pintype "bidirectional"))
    )
    (net (code "19") (name "DAPI_RTS") (class "Default")
      (node (ref "U$2") (pin "P15") (pinfunction "B5_P15") (pintype "bidirectional"))
      (node (ref "USB") (pin "41") (pinfunction "BDBUS3_41") (pintype "bidirectional"))
    )
    (net (code "20") (name "DAPI_RXD") (class "Default")
      (node (ref "U$2") (pin "P12") (pinfunction "B8_P12") (pintype "bidirectional"))
      (node (ref "USB") (pin "38") (pinfunction "BDBUS0_38") (pintype "bidirectional"))
    )
    (net (code "21") (name "DAPI_TXD") (class "Default")
      (node (ref "U$2") (pin "P13") (pinfunction "B7_P13") (pintype "bidirectional"))
      (node (ref "USB") (pin "39") (pinfunction "BDBUS1_39") (pintype "bidirectional"))
    )
    (net (code "22") (name "EECLK") (class "Default")
      (node (ref "FT_EEPROM") (pin "2") (pinfunction "CLK_2") (pintype "bidirectional"))
      (node (ref "USB") (pin "62") (pinfunction "EECLK_62") (pintype "bidirectional"))
    )
    (net (code "23") (name "EECS") (class "Default")
      (node (ref "FT_EEPROM") (pin "1") (pinfunction "CS_1") (pintype "bidirectional"))
      (node (ref "USB") (pin "63") (pinfunction "EECS_63") (pintype "bidirectional"))
    )
    (net (code "24") (name "EED") (class "Default")
      (node (ref "FT_EEPROM") (pin "3") (pinfunction "DIN_3") (pintype "bidirectional"))
      (node (ref "R24") (pin "2") (pinfunction "2_2") (pintype "passive"))
      (node (ref "USB") (pin "61") (pinfunction "EEDATA_61") (pintype "bidirectional"))
    )
    (net (code "25") (name "EXP_IN") (class "Default")
      (node (ref "D5") (pin "C") (pinfunction "C_C") (pintype "passive"))
      (node (ref "U_MAX488") (pin "2") (pinfunction "RO_2") (pintype "output"))
      (node (ref "U_OPTO_4") (pin "3") (pinfunction "A2_3") (pintype "bidirectional"))
    )
    (net (code "26") (name "EXP_IN_N") (class "Default")
      (node (ref "R15") (pin "1") (pinfunction "1_1") (pintype "passive"))
      (node (ref "R17") (pin "2") (pinfunction "2_2") (pintype "passive"))
      (node (ref "U_MAX488") (pin "7") (pinfunction "B_7") (pintype "input"))
      (node (ref "X1") (pin "14") (pinfunction "14_14") (pintype "passive"))
    )
    (net (code "27") (name "EXP_IN_P") (class "Default")
      (node (ref "R10") (pin "2") (pinfunction "2_2") (pintype "passive"))
      (node (ref "R16") (pin "2") (pinfunction "2_2") (pintype "passive"))
      (node (ref "U_MAX488") (pin "8") (pinfunction "A_8") (pintype "input"))
      (node (ref "X1") (pin "13") (pinfunction "13_13") (pintype "passive"))
    )
    (net (code "28") (name "EXP_OUT") (class "Default")
      (node (ref "D1") (pin "C") (pinfunction "C_C") (pintype "passive"))
      (node (ref "R25") (pin "1") (pinfunction "1_1") (pintype "passive"))
      (node (ref "U_MAX488") (pin "3") (pinfunction "DI_3") (pintype "input"))
      (node (ref "U_OPTO_4") (pin "8") (pinfunction "COL1_8") (pintype "input"))
    )
    (net (code "29") (name "EXP_OUT_N") (class "Default")
      (node (ref "U_MAX488") (pin "6") (pinfunction "Z_6") (pintype "output"))
      (node (ref "X1") (pin "7") (pinfunction "7_7") (pintype "passive"))
    )
    (net (code "30") (name "EXP_OUT_P") (class "Default")
      (node (ref "U_MAX488") (pin "5") (pinfunction "Y_5") (pintype "output"))
      (node (ref "X1") (pin "6") (pinfunction "6_6") (pintype "passive"))
    )
    (net (code "31") (name "F_CLK") (class "Default")
      (node (ref "S70FL") (pin "16") (pinfunction "SCLK_16") (pintype "bidirectional"))
      (node (ref "SF2_M2S010TQ1") (pin "100") (pinfunction "MSIO12PB2/SPI_0_CLK_100") (pintype "bidirectional"))
    )
    (net (code "32") (name "F_CS1") (class "Default")
      (node (ref "S70FL") (pin "7") (pinfunction "CS1#_7") (pintype "bidirectional"))
      (node (ref "SF2_M2S010TQ1") (pin "103") (pinfunction "MSIO13NB2/SPI_0_SS0/GPIO_7_A_103") (pintype "bidirectional"))
    )
    (net (code "33") (name "F_CS2") (class "Default")
      (node (ref "S70FL") (pin "6") (pinfunction "CS2#_6") (pintype "bidirectional"))
      (node (ref "SF2_M2S010TQ1") (pin "94") (pinfunction "MSIO6PB2/USB_DATA6_B_94") (pintype "bidirectional"))
    )
    (net (code "34") (name "F_MISO") (class "Default")
      (node (ref "S70FL") (pin "8") (pinfunction "SO/O1_8") (pintype "bidirectional"))
      (node (ref "SF2_M2S010TQ1") (pin "101") (pinfunction "MSIO12NB2/SPI_0_SDI/GPIO_5_A_101") (pintype "bidirectional"))
    )
    (net (code "35") (name "F_MOSI") (class "Default")
      (node (ref "S70FL") (pin "15") (pinfunction "SI/O0_15") (pintype "bidirectional"))
      (node (ref "SF2_M2S010TQ1") (pin "102") (pinfunction "MSIO13PB2/SPI_0_SDO/GPIO_6_A_102") (pintype "bidirectional"))
    )
    (net (code "36") (name "GND") (class "Default")
      (node (ref "C1") (pin "2") (pinfunction "2_2") (pintype "passive"))
      (node (ref "C10") (pin "2") (pinfunction "2_2") (pintype "passive"))
      (node (ref "C100") (pin "2") (pinfunction "2_2") (pintype "passive"))
      (node (ref "C101") (pin "1") (pinfunction "1_1") (pintype "passive"))
      (node (ref "C103") (pin "2") (pinfunction "2_2") (pintype "passive"))
      (node (ref "C104") (pin "2") (pinfunction "2_2") (pintype "passive"))
      (node (ref "C105") (pin "2") (pinfunction "2_2") (pintype "passive"))
      (node (ref "C106") (pin "1") (pinfunction "1_1") (pintype "passive"))
      (node (ref "C108") (pin "2") (pinfunction "2_2") (pintype "passive"))
      (node (ref "C109") (pin "2") (pinfunction "2_2") (pintype "passive"))
      (node (ref "C11") (pin "2") (pinfunction "2_2") (pintype "passive"))
      (node (ref "C111") (pin "2") (pinfunction "2_2") (pintype "passive"))
      (node (ref "C112") (pin "1") (pinfunction "1_1") (pintype "passive"))
      (node (ref "C113") (pin "2") (pinfunction "2_2") (pintype "passive"))
      (node (ref "C114") (pin "2") (pinfunction "2_2") (pintype "passive"))
      (node (ref "C115") (pin "2") (pinfunction "2_2") (pintype "passive"))
      (node (ref "C116") (pin "1") (pinfunction "1_1") (pintype "passive"))
      (node (ref "C118") (pin "2") (pinfunction "2_2") (pintype "passive"))
      (node (ref "C119") (pin "2") (pinfunction "2_2") (pintype "passive"))
      (node (ref "C12") (pin "2") (pinfunction "2_2") (pintype "passive"))
      (node (ref "C120") (pin "2") (pinfunction "2_2") (pintype "passive"))
      (node (ref "C121") (pin "2") (pinfunction "2_2") (pintype "passive"))
      (node (ref "C122") (pin "1") (pinfunction "1_1") (pintype "passive"))
      (node (ref "C124") (pin "2") (pinfunction "2_2") (pintype "passive"))
      (node (ref "C125") (pin "2") (pinfunction "2_2") (pintype "passive"))
      (node (ref "C126") (pin "2") (pinfunction "2_2") (pintype "passive"))
      (node (ref "C127") (pin "1") (pinfunction "1_1") (pintype "passive"))
      (node (ref "C129") (pin "2") (pinfunction "2_2") (pintype "passive"))
      (node (ref "C13") (pin "2") (pinfunction "2_2") (pintype "passive"))
      (node (ref "C130") (pin "2") (pinfunction "2_2") (pintype "passive"))
      (node (ref "C132") (pin "2") (pinfunction "2_2") (pintype "passive"))
      (node (ref "C133") (pin "1") (pinfunction "1_1") (pintype "passive"))
      (node (ref "C134") (pin "2") (pinfunction "2_2") (pintype "passive"))
      (node (ref "C135") (pin "2") (pinfunction "2_2") (pintype "passive"))
      (node (ref "C136") (pin "2") (pinfunction "2_2") (pintype "passive"))
      (node (ref "C137") (pin "1") (pinfunction "1_1") (pintype "passive"))
      (node (ref "C139") (pin "2") (pinfunction "2_2") (pintype "passive"))
      (node (ref "C14") (pin "2") (pinfunction "2_2") (pintype "passive"))
      (node (ref "C140") (pin "2") (pinfunction "2_2") (pintype "passive"))
      (node (ref "C141") (pin "2") (pinfunction "2_2") (pintype "passive"))
      (node (ref "C142") (pin "2") (pinfunction "2_2") (pintype "passive"))
      (node (ref "C143") (pin "1") (pinfunction "1_1") (pintype "passive"))
      (node (ref "C145") (pin "2") (pinfunction "2_2") (pintype "passive"))
      (node (ref "C146") (pin "2") (pinfunction "2_2") (pintype "passive"))
      (node (ref "C147") (pin "2") (pinfunction "2_2") (pintype "passive"))
      (node (ref "C148") (pin "1") (pinfunction "1_1") (pintype "passive"))
      (node (ref "C15") (pin "2") (pinfunction "2_2") (pintype "passive"))
      (node (ref "C150") (pin "2") (pinfunction "2_2") (pintype "passive"))
      (node (ref "C151") (pin "2") (pinfunction "2_2") (pintype "passive"))
      (node (ref "C153") (pin "2") (pinfunction "2_2") (pintype "passive"))
      (node (ref "C154") (pin "1") (pinfunction "1_1") (pintype "passive"))
      (node (ref "C155") (pin "2") (pinfunction "2_2") (pintype "passive"))
      (node (ref "C156") (pin "2") (pinfunction "2_2") (pintype "passive"))
      (node (ref "C157") (pin "2") (pinfunction "2_2") (pintype "passive"))
      (node (ref "C158") (pin "1") (pinfunction "1_1") (pintype "passive"))
      (node (ref "C16") (pin "2") (pinfunction "2_2") (pintype "passive"))
      (node (ref "C160") (pin "2") (pinfunction "2_2") (pintype "passive"))
      (node (ref "C161") (pin "2") (pinfunction "2_2") (pintype "passive"))
      (node (ref "C162") (pin "2") (pinfunction "2_2") (pintype "passive"))
      (node (ref "C163") (pin "2") (pinfunction "2_2") (pintype "passive"))
      (node (ref "C164") (pin "1") (pinfunction "1_1") (pintype "passive"))
      (node (ref "C166") (pin "2") (pinfunction "2_2") (pintype "passive"))
      (node (ref "C167") (pin "2") (pinfunction "2_2") (pintype "passive"))
      (node (ref "C168") (pin "2") (pinfunction "2_2") (pintype "passive"))
      (node (ref "C169") (pin "1") (pinfunction "1_1") (pintype "passive"))
      (node (ref "C17") (pin "2") (pinfunction "2_2") (pintype "passive"))
      (node (ref "C171") (pin "2") (pinfunction "2_2") (pintype "passive"))
      (node (ref "C172") (pin "2") (pinfunction "2_2") (pintype "passive"))
      (node (ref "C174") (pin "2") (pinfunction "2_2") (pintype "passive"))
      (node (ref "C175") (pin "1") (pinfunction "1_1") (pintype "passive"))
      (node (ref "C18") (pin "2") (pinfunction "2_2") (pintype "passive"))
      (node (ref "C19") (pin "2") (pinfunction "2_2") (pintype "passive"))
      (node (ref "C197") (pin "2") (pinfunction "2_2") (pintype "passive"))
      (node (ref "C198") (pin "2") (pinfunction "2_2") (pintype "passive"))
      (node (ref "C199") (pin "2") (pinfunction "2_2") (pintype "passive"))
      (node (ref "C2") (pin "2") (pinfunction "2_2") (pintype "passive"))
      (node (ref "C20") (pin "2") (pinfunction "2_2") (pintype "passive"))
      (node (ref "C200") (pin "1") (pinfunction "1_1") (pintype "passive"))
      (node (ref "C202") (pin "2") (pinfunction "2_2") (pintype "passive"))
      (node (ref "C203") (pin "2") (pinfunction "2_2") (pintype "passive"))
      (node (ref "C204") (pin "2") (pinfunction "2_2") (pintype "passive"))
      (node (ref "C205") (pin "2") (pinfunction "2_2") (pintype "passive"))
      (node (ref "C206") (pin "1") (pinfunction "1_1") (pintype "passive"))
      (node (ref "C208") (pin "2") (pinfunction "2_2") (pintype "passive"))
      (node (ref "C209") (pin "2") (pinfunction "2_2") (pintype "passive"))
      (node (ref "C21") (pin "1") (pinfunction "1_1") (pintype "passive"))
      (node (ref "C210") (pin "2") (pinfunction "2_2") (pintype "passive"))
      (node (ref "C211") (pin "1") (pinfunction "1_1") (pintype "passive"))
      (node (ref "C213") (pin "2") (pinfunction "2_2") (pintype "passive"))
      (node (ref "C214") (pin "2") (pinfunction "2_2") (pintype "passive"))
      (node (ref "C216") (pin "2") (pinfunction "2_2") (pintype "passive"))
      (node (ref "C217") (pin "1") (pinfunction "1_1") (pintype "passive"))
      (node (ref "C22") (pin "2") (pinfunction "2_2") (pintype "passive"))
      (node (ref "C23") (pin "2") (pinfunction "2_2") (pintype "passive"))
      (node (ref "C24") (pin "2") (pinfunction "2_2") (pintype "passive"))
      (node (ref "C25") (pin "1") (pinfunction "1_1") (pintype "passive"))
      (node (ref "C26") (pin "1") (pinfunction "1_1") (pintype "passive"))
      (node (ref "C27") (pin "2") (pinfunction "2_2") (pintype "passive"))
      (node (ref "C28") (pin "1") (pinfunction "1_1") (pintype "passive"))
      (node (ref "C29") (pin "2") (pinfunction "2_2") (pintype "passive"))
      (node (ref "C30") (pin "2") (pinfunction "2_2") (pintype "passive"))
      (node (ref "C31") (pin "1") (pinfunction "1_1") (pintype "passive"))
      (node (ref "C32") (pin "2") (pinfunction "2_2") (pintype "passive"))
      (node (ref "C33") (pin "2") (pinfunction "2_2") (pintype "passive"))
      (node (ref "C34") (pin "2") (pinfunction "2_2") (pintype "passive"))
      (node (ref "C35") (pin "1") (pinfunction "1_1") (pintype "passive"))
      (node (ref "C36") (pin "1") (pinfunction "1_1") (pintype "passive"))
      (node (ref "C37") (pin "1") (pinfunction "1_1") (pintype "passive"))
      (node (ref "C39") (pin "-") (pinfunction "-_-") (pintype "passive"))
      (node (ref "C40") (pin "-") (pinfunction "-_-") (pintype "passive"))
      (node (ref "C41") (pin "-") (pinfunction "-_-") (pintype "passive"))
      (node (ref "C45") (pin "2") (pinfunction "2_2") (pintype "passive"))
      (node (ref "C46") (pin "1") (pinfunction "1_1") (pintype "passive"))
      (node (ref "C48") (pin "2") (pinfunction "2_2") (pintype "passive"))
      (node (ref "C49") (pin "2") (pinfunction "2_2") (pintype "passive"))
      (node (ref "C50") (pin "2") (pinfunction "2_2") (pintype "passive"))
      (node (ref "C51") (pin "2") (pinfunction "2_2") (pintype "passive"))
      (node (ref "C52") (pin "1") (pinfunction "1_1") (pintype "passive"))
      (node (ref "C54") (pin "2") (pinfunction "2_2") (pintype "passive"))
      (node (ref "C55") (pin "2") (pinfunction "2_2") (pintype "passive"))
      (node (ref "C56") (pin "2") (pinfunction "2_2") (pintype "passive"))
      (node (ref "C57") (pin "1") (pinfunction "1_1") (pintype "passive"))
      (node (ref "C59") (pin "2") (pinfunction "2_2") (pintype "passive"))
      (node (ref "C63") (pin "2") (pinfunction "2_2") (pintype "passive"))
      (node (ref "C64") (pin "-") (pinfunction "-_-") (pintype "passive"))
      (node (ref "C65") (pin "-") (pinfunction "-_-") (pintype "passive"))
      (node (ref "C66") (pin "-") (pinfunction "-_-") (pintype "passive"))
      (node (ref "C67") (pin "-") (pinfunction "-_-") (pintype "passive"))
      (node (ref "C69") (pin "2") (pinfunction "2_2") (pintype "passive"))
      (node (ref "C7") (pin "2") (pinfunction "2_2") (pintype "passive"))
      (node (ref "C70") (pin "1") (pinfunction "1_1") (pintype "passive"))
      (node (ref "C71") (pin "1") (pinfunction "1_1") (pintype "passive"))
      (node (ref "C73") (pin "1") (pinfunction "1_1") (pintype "passive"))
      (node (ref "C74") (pin "2") (pinfunction "2_2") (pintype "passive"))
      (node (ref "C75") (pin "2") (pinfunction "2_2") (pintype "passive"))
      (node (ref "C76") (pin "1") (pinfunction "1_1") (pintype "passive"))
      (node (ref "C77") (pin "1") (pinfunction "1_1") (pintype "passive"))
      (node (ref "C78") (pin "1") (pinfunction "1_1") (pintype "passive"))
      (node (ref "C79") (pin "1") (pinfunction "1_1") (pintype "passive"))
      (node (ref "C8") (pin "2") (pinfunction "2_2") (pintype "passive"))
      (node (ref "C9") (pin "2") (pinfunction "2_2") (pintype "passive"))
      (node (ref "C92") (pin "2") (pinfunction "2_2") (pintype "passive"))
      (node (ref "C93") (pin "2") (pinfunction "2_2") (pintype "passive"))
      (node (ref "C94") (pin "2") (pinfunction "2_2") (pintype "passive"))
      (node (ref "C95") (pin "1") (pinfunction "1_1") (pintype "passive"))
      (node (ref "C97") (pin "2") (pinfunction "2_2") (pintype "passive"))
      (node (ref "C98") (pin "2") (pinfunction "2_2") (pintype "passive"))
      (node (ref "C99") (pin "2") (pinfunction "2_2") (pintype "passive"))
      (node (ref "CON_STAMP1") (pin "P$7") (pinfunction "P$7_P$7") (pintype "bidirectional"))
      (node (ref "CON_STAMP2") (pin "P$7") (pinfunction "P$7_P$7") (pintype "bidirectional"))
      (node (ref "CON_STAMP3") (pin "P$7") (pinfunction "P$7_P$7") (pintype "bidirectional"))
      (node (ref "CON_STAMP4") (pin "P$7") (pinfunction "P$7_P$7") (pintype "bidirectional"))
      (node (ref "CON_STAMP5") (pin "P$7") (pinfunction "P$7_P$7") (pintype "bidirectional"))
      (node (ref "CON_STAMP6") (pin "P$7") (pinfunction "P$7_P$7") (pintype "bidirectional"))
      (node (ref "FT_EEPROM") (pin "5") (pinfunction "VSS_5") (pintype "bidirectional"))
      (node (ref "PROBES") (pin "2") (pinfunction "2_2") (pintype "passive"))
      (node (ref "PWR") (pin "C") (pinfunction "C_C") (pintype "passive"))
      (node (ref "Q1") (pin "2") (pinfunction "S_2") (pintype "passive"))
      (node (ref "Q3") (pin "2") (pinfunction "S_2") (pintype "passive"))
      (node (ref "Q4") (pin "2") (pinfunction "S_2") (pintype "passive"))
      (node (ref "Q5") (pin "2") (pinfunction "S_2") (pintype "passive"))
      (node (ref "Q6") (pin "2") (pinfunction "S_2") (pintype "passive"))
      (node (ref "R101") (pin "2") (pinfunction "2_2") (pintype "passive"))
      (node (ref "R107") (pin "2") (pinfunction "2_2") (pintype "passive"))
      (node (ref "R117") (pin "2") (pinfunction "2_2") (pintype "passive"))
      (node (ref "R118") (pin "1") (pinfunction "1_1") (pintype "passive"))
      (node (ref "R120") (pin "2") (pinfunction "2_2") (pintype "passive"))
      (node (ref "R126") (pin "2") (pinfunction "2_2") (pintype "passive"))
      (node (ref "R136") (pin "2") (pinfunction "2_2") (pintype "passive"))
      (node (ref "R137") (pin "1") (pinfunction "1_1") (pintype "passive"))
      (node (ref "R139") (pin "2") (pinfunction "2_2") (pintype "passive"))
      (node (ref "R145") (pin "2") (pinfunction "2_2") (pintype "passive"))
      (node (ref "R155") (pin "2") (pinfunction "2_2") (pintype "passive"))
      (node (ref "R156") (pin "1") (pinfunction "1_1") (pintype "passive"))
      (node (ref "R177") (pin "2") (pinfunction "2_2") (pintype "passive"))
      (node (ref "R183") (pin "2") (pinfunction "2_2") (pintype "passive"))
      (node (ref "R193") (pin "2") (pinfunction "2_2") (pintype "passive"))
      (node (ref "R194") (pin "1") (pinfunction "1_1") (pintype "passive"))
      (node (ref "R21") (pin "1") (pinfunction "1_1") (pintype "passive"))
      (node (ref "R30") (pin "2") (pinfunction "2_2") (pintype "passive"))
      (node (ref "R34") (pin "1") (pinfunction "1_1") (pintype "passive"))
      (node (ref "R43") (pin "2") (pinfunction "2_2") (pintype "passive"))
      (node (ref "R44") (pin "1") (pinfunction "1_1") (pintype "passive"))
      (node (ref "R53") (pin "1") (pinfunction "1_1") (pintype "passive"))
      (node (ref "R69") (pin "2") (pinfunction "2_2") (pintype "passive"))
      (node (ref "R76") (pin "2") (pinfunction "2_2") (pintype "passive"))
      (node (ref "R81") (pin "2") (pinfunction "2_2") (pintype "passive"))
      (node (ref "R82") (pin "1") (pinfunction "1_1") (pintype "passive"))
      (node (ref "R88") (pin "2") (pinfunction "2_2") (pintype "passive"))
      (node (ref "R9") (pin "1") (pinfunction "1_1") (pintype "passive"))
      (node (ref "R98") (pin "2") (pinfunction "2_2") (pintype "passive"))
      (node (ref "R99") (pin "1") (pinfunction "1_1") (pintype "passive"))
      (node (ref "REF4V096") (pin "P5") (pinfunction "A_P5") (pintype "passive"))
      (node (ref "S70FL") (pin "10") (pinfunction "VSS_10") (pintype "bidirectional"))
      (node (ref "SF2_M2S010TQ1") (pin "11") (pinfunction "VSS_11") (pintype "bidirectional"))
      (node (ref "SF2_M2S010TQ1") (pin "113") (pinfunction "VSS_113") (pintype "bidirectional"))
      (node (ref "SF2_M2S010TQ1") (pin "119") (pinfunction "VSS_119") (pintype "bidirectional"))
      (node (ref "SF2_M2S010TQ1") (pin "126") (pinfunction "VSS_126") (pintype "bidirectional"))
      (node (ref "SF2_M2S010TQ1") (pin "132") (pinfunction "VSS_132") (pintype "bidirectional"))
      (node (ref "SF2_M2S010TQ1") (pin "139") (pinfunction "VSS_139") (pintype "bidirectional"))
      (node (ref "SF2_M2S010TQ1") (pin "18") (pinfunction "VSS_18") (pintype "bidirectional"))
      (node (ref "SF2_M2S010TQ1") (pin "26") (pinfunction "VSS_26") (pintype "bidirectional"))
      (node (ref "SF2_M2S010TQ1") (pin "34") (pinfunction "VSS_34") (pintype "bidirectional"))
      (node (ref "SF2_M2S010TQ1") (pin "40") (pinfunction "VSS_40") (pintype "bidirectional"))
      (node (ref "SF2_M2S010TQ1") (pin "42") (pinfunction "VSS_42") (pintype "bidirectional"))
      (node (ref "SF2_M2S010TQ1") (pin "5") (pinfunction "VSS_5") (pintype "bidirectional"))
      (node (ref "SF2_M2S010TQ1") (pin "51") (pinfunction "VSS_51") (pintype "bidirectional"))
      (node (ref "SF2_M2S010TQ1") (pin "59") (pinfunction "VSS_59") (pintype "bidirectional"))
      (node (ref "SF2_M2S010TQ1") (pin "65") (pinfunction "VSS_65") (pintype "bidirectional"))
      (node (ref "SF2_M2S010TQ1") (pin "84") (pinfunction "VSS_84") (pintype "bidirectional"))
      (node (ref "SF2_M2S010TQ1") (pin "96") (pinfunction "VSSNVM_96") (pintype "bidirectional"))
      (node (ref "SF2_M2S010TQ1") (pin "98") (pinfunction "VSS_98") (pintype "bidirectional"))
      (node (ref "STAMP1_ADC_SG1") (pin "10") (pinfunction "VREFCOM_10") (pintype "bidirectional"))
      (node (ref "STAMP1_ADC_SG1") (pin "2") (pinfunction "DGND/DSS_2") (pintype "bidirectional"))
      (node (ref "STAMP1_ADC_SG1") (pin "21") (pinfunction "AVSS_21") (pintype "bidirectional"))
      (node (ref "STAMP1_ADC_SG2") (pin "10") (pinfunction "VREFCOM_10") (pintype "bidirectional"))
      (node (ref "STAMP1_ADC_SG2") (pin "2") (pinfunction "DGND/DSS_2") (pintype "bidirectional"))
      (node (ref "STAMP1_ADC_SG2") (pin "21") (pinfunction "AVSS_21") (pintype "bidirectional"))
      (node (ref "STAMP1_ADC_TEMP") (pin "10") (pinfunction "VREFCOM_10") (pintype "bidirectional"))
      (node (ref "STAMP1_ADC_TEMP") (pin "2") (pinfunction "DGND/DSS_2") (pintype "bidirectional"))
      (node (ref "STAMP1_ADC_TEMP") (pin "21") (pinfunction "AVSS_21") (pintype "bidirectional"))
      (node (ref "STAMP1_ADC_TEMP") (pin "3") (pinfunction "CLK_3") (pintype "bidirectional"))
      (node (ref "STAMP2_ADC_SG1") (pin "10") (pinfunction "VREFCOM_10") (pintype "bidirectional"))
      (node (ref "STAMP2_ADC_SG1") (pin "2") (pinfunction "DGND/DSS_2") (pintype "bidirectional"))
      (node (ref "STAMP2_ADC_SG1") (pin "21") (pinfunction "AVSS_21") (pintype "bidirectional"))
      (node (ref "STAMP2_ADC_SG2") (pin "10") (pinfunction "VREFCOM_10") (pintype "bidirectional"))
      (node (ref "STAMP2_ADC_SG2") (pin "2") (pinfunction "DGND/DSS_2") (pintype "bidirectional"))
      (node (ref "STAMP2_ADC_SG2") (pin "21") (pinfunction "AVSS_21") (pintype "bidirectional"))
      (node (ref "STAMP2_ADC_TEMP") (pin "10") (pinfunction "VREFCOM_10") (pintype "bidirectional"))
      (node (ref "STAMP2_ADC_TEMP") (pin "2") (pinfunction "DGND/DSS_2") (pintype "bidirectional"))
      (node (ref "STAMP2_ADC_TEMP") (pin "21") (pinfunction "AVSS_21") (pintype "bidirectional"))
      (node (ref "STAMP2_ADC_TEMP") (pin "3") (pinfunction "CLK_3") (pintype "bidirectional"))
      (node (ref "STAMP3_ADC_SG1") (pin "10") (pinfunction "VREFCOM_10") (pintype "bidirectional"))
      (node (ref "STAMP3_ADC_SG1") (pin "2") (pinfunction "DGND/DSS_2") (pintype "bidirectional"))
      (node (ref "STAMP3_ADC_SG1") (pin "21") (pinfunction "AVSS_21") (pintype "bidirectional"))
      (node (ref "STAMP3_ADC_SG2") (pin "10") (pinfunction "VREFCOM_10") (pintype "bidirectional"))
      (node (ref "STAMP3_ADC_SG2") (pin "2") (pinfunction "DGND/DSS_2") (pintype "bidirectional"))
      (node (ref "STAMP3_ADC_SG2") (pin "21") (pinfunction "AVSS_21") (pintype "bidirectional"))
      (node (ref "STAMP3_ADC_TEMP") (pin "10") (pinfunction "VREFCOM_10") (pintype "bidirectional"))
      (node (ref "STAMP3_ADC_TEMP") (pin "2") (pinfunction "DGND/DSS_2") (pintype "bidirectional"))
      (node (ref "STAMP3_ADC_TEMP") (pin "21") (pinfunction "AVSS_21") (pintype "bidirectional"))
      (node (ref "STAMP3_ADC_TEMP") (pin "3") (pinfunction "CLK_3") (pintype "bidirectional"))
      (node (ref "STAMP4_ADC_SG1") (pin "10") (pinfunction "VREFCOM_10") (pintype "bidirectional"))
      (node (ref "STAMP4_ADC_SG1") (pin "2") (pinfunction "DGND/DSS_2") (pintype "bidirectional"))
      (node (ref "STAMP4_ADC_SG1") (pin "21") (pinfunction "AVSS_21") (pintype "bidirectional"))
      (node (ref "STAMP4_ADC_SG2") (pin "10") (pinfunction "VREFCOM_10") (pintype "bidirectional"))
      (node (ref "STAMP4_ADC_SG2") (pin "2") (pinfunction "DGND/DSS_2") (pintype "bidirectional"))
      (node (ref "STAMP4_ADC_SG2") (pin "21") (pinfunction "AVSS_21") (pintype "bidirectional"))
      (node (ref "STAMP4_ADC_TEMP") (pin "10") (pinfunction "VREFCOM_10") (pintype "bidirectional"))
      (node (ref "STAMP4_ADC_TEMP") (pin "2") (pinfunction "DGND/DSS_2") (pintype "bidirectional"))
      (node (ref "STAMP4_ADC_TEMP") (pin "21") (pinfunction "AVSS_21") (pintype "bidirectional"))
      (node (ref "STAMP4_ADC_TEMP") (pin "3") (pinfunction "CLK_3") (pintype "bidirectional"))
      (node (ref "STAMP5_ADC_SG1") (pin "10") (pinfunction "VREFCOM_10") (pintype "bidirectional"))
      (node (ref "STAMP5_ADC_SG1") (pin "2") (pinfunction "DGND/DSS_2") (pintype "bidirectional"))
      (node (ref "STAMP5_ADC_SG1") (pin "21") (pinfunction "AVSS_21") (pintype "bidirectional"))
      (node (ref "STAMP5_ADC_SG2") (pin "10") (pinfunction "VREFCOM_10") (pintype "bidirectional"))
      (node (ref "STAMP5_ADC_SG2") (pin "2") (pinfunction "DGND/DSS_2") (pintype "bidirectional"))
      (node (ref "STAMP5_ADC_SG2") (pin "21") (pinfunction "AVSS_21") (pintype "bidirectional"))
      (node (ref "STAMP5_ADC_TEMP") (pin "10") (pinfunction "VREFCOM_10") (pintype "bidirectional"))
      (node (ref "STAMP5_ADC_TEMP") (pin "2") (pinfunction "DGND/DSS_2") (pintype "bidirectional"))
      (node (ref "STAMP5_ADC_TEMP") (pin "21") (pinfunction "AVSS_21") (pintype "bidirectional"))
      (node (ref "STAMP5_ADC_TEMP") (pin "3") (pinfunction "CLK_3") (pintype "bidirectional"))
      (node (ref "STAMP6_ADC_SG1") (pin "10") (pinfunction "VREFCOM_10") (pintype "bidirectional"))
      (node (ref "STAMP6_ADC_SG1") (pin "2") (pinfunction "DGND/DSS_2") (pintype "bidirectional"))
      (node (ref "STAMP6_ADC_SG1") (pin "21") (pinfunction "AVSS_21") (pintype "bidirectional"))
      (node (ref "STAMP6_ADC_SG2") (pin "10") (pinfunction "VREFCOM_10") (pintype "bidirectional"))
      (node (ref "STAMP6_ADC_SG2") (pin "2") (pinfunction "DGND/DSS_2") (pintype "bidirectional"))
      (node (ref "STAMP6_ADC_SG2") (pin "21") (pinfunction "AVSS_21") (pintype "bidirectional"))
      (node (ref "STAMP6_ADC_TEMP") (pin "10") (pinfunction "VREFCOM_10") (pintype "bidirectional"))
      (node (ref "STAMP6_ADC_TEMP") (pin "2") (pinfunction "DGND/DSS_2") (pintype "bidirectional"))
      (node (ref "STAMP6_ADC_TEMP") (pin "21") (pinfunction "AVSS_21") (pintype "bidirectional"))
      (node (ref "STAMP6_ADC_TEMP") (pin "3") (pinfunction "CLK_3") (pintype "bidirectional"))
      (node (ref "TPS78512QKVURQ1") (pin "4") (pinfunction "GND_4") (pintype "bidirectional"))
      (node (ref "TPS78512QKVURQ1") (pin "5") (pinfunction "GND_5") (pintype "bidirectional"))
      (node (ref "U$1") (pin "P11") (pinfunction "GND_P11") (pintype "bidirectional"))
      (node (ref "U$10") (pin "P$1") (pinfunction "1_P$1") (pintype "passive"))
      (node (ref "U$11") (pin "P$1") (pinfunction "1_P$1") (pintype "passive"))
      (node (ref "U$12") (pin "P$1") (pinfunction "1_P$1") (pintype "passive"))
      (node (ref "U$13") (pin "P$1") (pinfunction "1_P$1") (pintype "passive"))
      (node (ref "U$14") (pin "P$1") (pinfunction "1_P$1") (pintype "passive"))
      (node (ref "U$15") (pin "P$1") (pinfunction "1_P$1") (pintype "passive"))
      (node (ref "U$16") (pin "P$1") (pinfunction "1_P$1") (pintype "passive"))
      (node (ref "U$19") (pin "P$1") (pinfunction "1_P$1") (pintype "passive"))
      (node (ref "U$2") (pin "P11") (pinfunction "GND_P11") (pintype "bidirectional"))
      (node (ref "U$20") (pin "P$1") (pinfunction "1_P$1") (pintype "passive"))
      (node (ref "U$3") (pin "P11") (pinfunction "GND_P11") (pintype "bidirectional"))
      (node (ref "U$5") (pin "P2") (pinfunction "GND_P2") (pintype "bidirectional"))
      (node (ref "U$6") (pin "P$1") (pinfunction "1_P$1") (pintype "passive"))
      (node (ref "U$7") (pin "P$1") (pinfunction "1_P$1") (pintype "passive"))
      (node (ref "U$9") (pin "P$1") (pinfunction "1_P$1") (pintype "passive"))
      (node (ref "USB") (pin "1") (pinfunction "GND_1") (pintype "bidirectional"))
      (node (ref "USB") (pin "10") (pinfunction "AGND_10") (pintype "bidirectional"))
      (node (ref "USB") (pin "11") (pinfunction "GND_11") (pintype "bidirectional"))
      (node (ref "USB") (pin "13") (pinfunction "TEST_13") (pintype "bidirectional"))
      (node (ref "USB") (pin "15") (pinfunction "GND_15") (pintype "bidirectional"))
      (node (ref "USB") (pin "25") (pinfunction "GND_25") (pintype "bidirectional"))
      (node (ref "USB") (pin "35") (pinfunction "GND_35") (pintype "bidirectional"))
      (node (ref "USB") (pin "47") (pinfunction "GND_47") (pintype "bidirectional"))
      (node (ref "USB") (pin "5") (pinfunction "GND_5") (pintype "bidirectional"))
      (node (ref "USB") (pin "51") (pinfunction "GND_51") (pintype "bidirectional"))
      (node (ref "USB_CONN") (pin "GND") (pinfunction "GND_GND") (pintype "power_in"))
      (node (ref "U_LT1528") (pin "3") (pinfunction "GND_3") (pintype "bidirectional"))
      (node (ref "U_LT1528") (pin "6") (pinfunction "GND_6") (pintype "bidirectional"))
      (node (ref "U_OPTO_3") (pin "3") (pinfunction "A2_3") (pintype "bidirectional"))
      (node (ref "U_OPTO_3") (pin "4") (pinfunction "C2_4") (pintype "bidirectional"))
      (node (ref "U_OPTO_3") (pin "5") (pinfunction "EMT2_5") (pintype "output"))
      (node (ref "U_OPTO_3") (pin "6") (pinfunction "COL2_6") (pintype "input"))
      (node (ref "U_OPTO_3") (pin "7") (pinfunction "EMT1_7") (pintype "output"))
      (node (ref "U_OPTO_5") (pin "5") (pinfunction "EMT2_5") (pintype "output"))
      (node (ref "U_OPTO_5") (pin "7") (pinfunction "EMT1_7") (pintype "output"))
      (node (ref "U_TRACODCDC") (pin "5") (pinfunction "-VOUT_5") (pintype "passive"))
      (node (ref "WP") (pin "1") (pinfunction "1_1") (pintype "passive"))
      (node (ref "ZE05H-4P-2V") (pin "P5") (pinfunction "P$5_P5") (pintype "bidirectional"))
      (node (ref "ZE05H-4P-2V") (pin "P6") (pinfunction "P$5_P6") (pintype "bidirectional"))
    )
    (net (code "37") (name "LED_FPGA_LOADED") (class "Default")
      (node (ref "Q3") (pin "1") (pinfunction "G_1") (pintype "passive"))
      (node (ref "R44") (pin "2") (pinfunction "2_2") (pintype "passive"))
      (node (ref "SF2_M2S010TQ1") (pin "23") (pinfunction "MSIOD84PB6/CCC_NE1_CLKI2_23") (pintype "bidirectional"))
    )
    (net (code "38") (name "LED_HB_MEMSYNC") (class "Default")
      (node (ref "Q6") (pin "1") (pinfunction "G_1") (pintype "passive"))
      (node (ref "R53") (pin "2") (pinfunction "2_2") (pintype "passive"))
      (node (ref "SF2_M2S010TQ1") (pin "28") (pinfunction "MSIOD90PB6_28") (pintype "bidirectional"))
    )
    (net (code "39") (name "LED_HB_MSS") (class "Default")
      (node (ref "Q5") (pin "1") (pinfunction "G_1") (pintype "passive"))
      (node (ref "R34") (pin "2") (pinfunction "2_2") (pintype "passive"))
      (node (ref "SF2_M2S010TQ1") (pin "24") (pinfunction "MSIOD85PB6/CCC_NE1_CLKI1_24") (pintype "bidirectional"))
    )
    (net (code "40") (name "LED_RECORDING") (class "Default")
      (node (ref "Q4") (pin "1") (pinfunction "G_1") (pintype "passive"))
      (node (ref "R21") (pin "2") (pinfunction "2_2") (pintype "passive"))
      (node (ref "SF2_M2S010TQ1") (pin "27") (pinfunction "MSIOD90NB6_27") (pintype "bidirectional"))
    )
    (net (code "41") (name "LO") (class "Default")
      (node (ref "SF2_M2S010TQ1") (pin "125") (pinfunction "DDRIO44PB0_125") (pintype "bidirectional"))
      (node (ref "U_OPTO_5") (pin "8") (pinfunction "COL1_8") (pintype "input"))
    )
    (net (code "42") (name "MAIN_EXTAL") (class "Default")
      (node (ref "RCJ1") (pin "1") (pinfunction "1_1") (pintype "passive"))
      (node (ref "SF2_M2S010TQ1") (pin "71") (pinfunction "XTLOSC_MAIN_EXTAL_71") (pintype "bidirectional"))
      (node (ref "Y1J2") (pin "2") (pinfunction "2_2") (pintype "passive"))
    )
    (net (code "43") (name "MAIN_XTAL") (class "Default")
      (node (ref "RCJ2") (pin "1") (pinfunction "1_1") (pintype "passive"))
      (node (ref "SF2_M2S010TQ1") (pin "70") (pinfunction "XTLOSC_MAIN_XTAL_70") (pintype "bidirectional"))
      (node (ref "Y1J1") (pin "1") (pinfunction "1_1") (pintype "passive"))
    )
    (net (code "44") (name "Net-(C21-Pad2)") (class "Default")
      (node (ref "C21") (pin "2") (pinfunction "2_2") (pintype "passive"))
      (node (ref "USB_CONN") (pin "VBUS") (pinfunction "VBUS_VBUS") (pintype "power_in"))
    )
    (net (code "45") (name "Net-(C27-Pad1)") (class "Default")
      (node (ref "C27") (pin "1") (pinfunction "1_1") (pintype "passive"))
      (node (ref "R4") (pin "1") (pinfunction "1_1") (pintype "passive"))
      (node (ref "RCJ1") (pin "2") (pinfunction "2_2") (pintype "passive"))
    )
    (net (code "46") (name "Net-(C30-Pad1)") (class "Default")
      (node (ref "C30") (pin "1") (pinfunction "1_1") (pintype "passive"))
      (node (ref "Y1") (pin "1") (pinfunction "1_1") (pintype "passive"))
      (node (ref "Y1J1") (pin "2") (pinfunction "2_2") (pintype "passive"))
    )
    (net (code "47") (name "Net-(C32-Pad1)") (class "Default")
      (node (ref "C32") (pin "1") (pinfunction "1_1") (pintype "passive"))
      (node (ref "Y1") (pin "2") (pinfunction "2_2") (pintype "passive"))
      (node (ref "Y1J2") (pin "1") (pinfunction "1_1") (pintype "passive"))
    )
    (net (code "48") (name "Net-(C44-Pad1)") (class "Default")
      (node (ref "C44") (pin "1") (pinfunction "1_1") (pintype "passive"))
      (node (ref "R10") (pin "1") (pinfunction "1_1") (pintype "passive"))
      (node (ref "R15") (pin "2") (pinfunction "2_2") (pintype "passive"))
    )
    (net (code "49") (name "Net-(FL-PadA)") (class "Default")
      (node (ref "FL") (pin "A") (pinfunction "A_A") (pintype "passive"))
      (node (ref "R19") (pin "2") (pinfunction "2_2") (pintype "passive"))
    )
    (net (code "50") (name "Net-(FT_EEPROM-DOUT)") (class "Default")
      (node (ref "FT_EEPROM") (pin "4") (pinfunction "DOUT_4") (pintype "bidirectional"))
      (node (ref "R24") (pin "1") (pinfunction "1_1") (pintype "passive"))
      (node (ref "R27") (pin "1") (pinfunction "1_1") (pintype "passive"))
    )
    (net (code "51") (name "Net-(MS-PadA)") (class "Default")
      (node (ref "MS") (pin "A") (pinfunction "A_A") (pintype "passive"))
      (node (ref "R52") (pin "2") (pinfunction "2_2") (pintype "passive"))
    )
    (net (code "52") (name "Net-(MSS-PadA)") (class "Default")
      (node (ref "MSS") (pin "A") (pinfunction "A_A") (pintype "passive"))
      (node (ref "R20") (pin "2") (pinfunction "2_2") (pintype "passive"))
    )
    (net (code "53") (name "Net-(PWR-PadA)") (class "Default")
      (node (ref "PWR") (pin "A") (pinfunction "A_A") (pintype "passive"))
      (node (ref "R18") (pin "2") (pinfunction "2_2") (pintype "passive"))
    )
    (net (code "54") (name "Net-(Q1-D)") (class "Default")
      (node (ref "Q1") (pin "3") (pinfunction "D_3") (pintype "passive"))
      (node (ref "U_OPTO_4") (pin "2") (pinfunction "C1_2") (pintype "bidirectional"))
    )
    (net (code "55") (name "Net-(Q3-D)") (class "Default")
      (node (ref "FL") (pin "C") (pinfunction "C_C") (pintype "passive"))
      (node (ref "Q3") (pin "3") (pinfunction "D_3") (pintype "passive"))
      (node (ref "ZE05H-4P-2V") (pin "P3") (pinfunction "P$3_P3") (pintype "bidirectional"))
    )
    (net (code "56") (name "Net-(Q4-D)") (class "Default")
      (node (ref "Q4") (pin "3") (pinfunction "D_3") (pintype "passive"))
      (node (ref "RC") (pin "C") (pinfunction "C_C") (pintype "passive"))
      (node (ref "ZE05H-4P-2V") (pin "P1") (pinfunction "P$1_P1") (pintype "bidirectional"))
    )
    (net (code "57") (name "Net-(Q5-D)") (class "Default")
      (node (ref "MSS") (pin "C") (pinfunction "C_C") (pintype "passive"))
      (node (ref "Q5") (pin "3") (pinfunction "D_3") (pintype "passive"))
    )
    (net (code "58") (name "Net-(Q6-D)") (class "Default")
      (node (ref "MS") (pin "C") (pinfunction "C_C") (pintype "passive"))
      (node (ref "Q6") (pin "3") (pinfunction "D_3") (pintype "passive"))
    )
    (net (code "59") (name "Net-(R30-Pad1)") (class "Default")
      (node (ref "R30") (pin "1") (pinfunction "1_1") (pintype "passive"))
      (node (ref "R32") (pin "2") (pinfunction "2_2") (pintype "passive"))
      (node (ref "R33") (pin "1") (pinfunction "1_1") (pintype "passive"))
    )
    (net (code "60") (name "Net-(R49-Pad2)") (class "Default")
      (node (ref "R49") (pin "2") (pinfunction "2_2") (pintype "passive"))
      (node (ref "RC") (pin "A") (pinfunction "A_A") (pintype "passive"))
    )
    (net (code "61") (name "Net-(R69-Pad1)") (class "Default")
      (node (ref "R69") (pin "1") (pinfunction "1_1") (pintype "passive"))
      (node (ref "R73") (pin "2") (pinfunction "2_2") (pintype "passive"))
      (node (ref "R74") (pin "1") (pinfunction "1_1") (pintype "passive"))
    )
    (net (code "62") (name "Net-(R76-Pad1)") (class "Default")
      (node (ref "R76") (pin "1") (pinfunction "1_1") (pintype "passive"))
      (node (ref "R85") (pin "2") (pinfunction "2_2") (pintype "passive"))
      (node (ref "R86") (pin "1") (pinfunction "1_1") (pintype "passive"))
    )
    (net (code "63") (name "Net-(R88-Pad1)") (class "Default")
      (node (ref "R88") (pin "1") (pinfunction "1_1") (pintype "passive"))
      (node (ref "R91") (pin "2") (pinfunction "2_2") (pintype "passive"))
      (node (ref "R92") (pin "1") (pinfunction "1_1") (pintype "passive"))
    )
    (net (code "64") (name "Net-(R101-Pad1)") (class "Default")
      (node (ref "R101") (pin "1") (pinfunction "1_1") (pintype "passive"))
      (node (ref "R104") (pin "2") (pinfunction "2_2") (pintype "passive"))
      (node (ref "R105") (pin "1") (pinfunction "1_1") (pintype "passive"))
    )
    (net (code "65") (name "Net-(R107-Pad1)") (class "Default")
      (node (ref "R107") (pin "1") (pinfunction "1_1") (pintype "passive"))
      (node (ref "R110") (pin "2") (pinfunction "2_2") (pintype "passive"))
      (node (ref "R111") (pin "1") (pinfunction "1_1") (pintype "passive"))
    )
    (net (code "66") (name "Net-(R120-Pad1)") (class "Default")
      (node (ref "R120") (pin "1") (pinfunction "1_1") (pintype "passive"))
      (node (ref "R123") (pin "2") (pinfunction "2_2") (pintype "passive"))
      (node (ref "R124") (pin "1") (pinfunction "1_1") (pintype "passive"))
    )
    (net (code "67") (name "Net-(R126-Pad1)") (class "Default")
      (node (ref "R126") (pin "1") (pinfunction "1_1") (pintype "passive"))
      (node (ref "R129") (pin "2") (pinfunction "2_2") (pintype "passive"))
      (node (ref "R130") (pin "1") (pinfunction "1_1") (pintype "passive"))
    )
    (net (code "68") (name "Net-(R139-Pad1)") (class "Default")
      (node (ref "R139") (pin "1") (pinfunction "1_1") (pintype "passive"))
      (node (ref "R142") (pin "2") (pinfunction "2_2") (pintype "passive"))
      (node (ref "R143") (pin "1") (pinfunction "1_1") (pintype "passive"))
    )
    (net (code "69") (name "Net-(R145-Pad1)") (class "Default")
      (node (ref "R145") (pin "1") (pinfunction "1_1") (pintype "passive"))
      (node (ref "R148") (pin "2") (pinfunction "2_2") (pintype "passive"))
      (node (ref "R149") (pin "1") (pinfunction "1_1") (pintype "passive"))
    )
    (net (code "70") (name "Net-(R177-Pad1)") (class "Default")
      (node (ref "R177") (pin "1") (pinfunction "1_1") (pintype "passive"))
      (node (ref "R180") (pin "2") (pinfunction "2_2") (pintype "passive"))
      (node (ref "R181") (pin "1") (pinfunction "1_1") (pintype "passive"))
    )
    (net (code "71") (name "Net-(R183-Pad1)") (class "Default")
      (node (ref "R183") (pin "1") (pinfunction "1_1") (pintype "passive"))
      (node (ref "R186") (pin "2") (pinfunction "2_2") (pintype "passive"))
      (node (ref "R187") (pin "1") (pinfunction "1_1") (pintype "passive"))
    )
    (net (code "72") (name "Net-(SF2_M2S010TQ1A-DDRIO29PB0)") (class "Default")
      (node (ref "SF2_M2S010TQ1") (pin "110") (pinfunction "DDRIO29PB0_110") (pintype "bidirectional"))
      (node (ref "U$2") (pin "P9") (pinfunction "A8_P9") (pintype "bidirectional"))
    )
    (net (code "73") (name "Net-(SF2_M2S010TQ1A-DDRIO30NB0)") (class "Default")
      (node (ref "SF2_M2S010TQ1") (pin "112") (pinfunction "DDRIO30NB0_112") (pintype "bidirectional"))
      (node (ref "U$2") (pin "P7") (pinfunction "A6_P7") (pintype "bidirectional"))
    )
    (net (code "74") (name "Net-(SF2_M2S010TQ1A-DDRIO30PB0)") (class "Default")
      (node (ref "SF2_M2S010TQ1") (pin "111") (pinfunction "DDRIO30PB0_111") (pintype "bidirectional"))
      (node (ref "U$2") (pin "P8") (pinfunction "A7_P8") (pintype "bidirectional"))
    )
    (net (code "75") (name "Net-(SF2_M2S010TQ1A-DDRIO35NB0)") (class "Default")
      (node (ref "SF2_M2S010TQ1") (pin "115") (pinfunction "DDRIO35NB0_115") (pintype "bidirectional"))
      (node (ref "U$2") (pin "P6") (pinfunction "A5_P6") (pintype "bidirectional"))
    )
    (net (code "76") (name "Net-(SF2_M2S010TQ1A-DDRIO35PB0)") (class "Default")
      (node (ref "SF2_M2S010TQ1") (pin "116") (pinfunction "DDRIO35PB0_116") (pintype "bidirectional"))
      (node (ref "U$2") (pin "P5") (pinfunction "A4_P5") (pintype "bidirectional"))
    )
    (net (code "77") (name "Net-(SF2_M2S010TQ1A-DDRIO37NB0)") (class "Default")
      (node (ref "SF2_M2S010TQ1") (pin "117") (pinfunction "DDRIO37NB0_117") (pintype "bidirectional"))
      (node (ref "U$2") (pin "P4") (pinfunction "A3_P4") (pintype "bidirectional"))
    )
    (net (code "78") (name "Net-(SF2_M2S010TQ1A-DDRIO37PB0)") (class "Default")
      (node (ref "SF2_M2S010TQ1") (pin "118") (pinfunction "DDRIO37PB0_118") (pintype "bidirectional"))
      (node (ref "U$2") (pin "P3") (pinfunction "A2_P3") (pintype "bidirectional"))
    )
    (net (code "79") (name "Net-(SF2_M2S010TQ1A-DDRIO43NB0)") (class "Default")
      (node (ref "SF2_M2S010TQ1") (pin "122") (pinfunction "DDRIO43NB0_122") (pintype "bidirectional"))
      (node (ref "U$2") (pin "P1") (pinfunction "A1_P1") (pintype "bidirectional"))
    )
    (net (code "80") (name "Net-(SF2_M2S010TQ1A-DDRIO47PB0)") (class "Default")
      (node (ref "SF2_M2S010TQ1") (pin "129") (pinfunction "DDRIO47PB0_129") (pintype "bidirectional"))
      (node (ref "U$1") (pin "P1") (pinfunction "A1_P1") (pintype "bidirectional"))
    )
    (net (code "81") (name "Net-(SF2_M2S010TQ1A-DDRIO48NB0)") (class "Default")
      (node (ref "SF2_M2S010TQ1") (pin "130") (pinfunction "DDRIO48NB0_130") (pintype "bidirectional"))
      (node (ref "U$1") (pin "P3") (pinfunction "A2_P3") (pintype "bidirectional"))
    )
    (net (code "82") (name "Net-(SF2_M2S010TQ1A-DDRIO48PB0)") (class "Default")
      (node (ref "SF2_M2S010TQ1") (pin "131") (pinfunction "DDRIO48PB0_131") (pintype "bidirectional"))
      (node (ref "U$1") (pin "P4") (pinfunction "A3_P4") (pintype "bidirectional"))
    )
    (net (code "83") (name "Net-(SF2_M2S010TQ1A-DDRIO53NB0)") (class "Default")
      (node (ref "SF2_M2S010TQ1") (pin "134") (pinfunction "DDRIO53NB0_134") (pintype "bidirectional"))
      (node (ref "U$1") (pin "P5") (pinfunction "A4_P5") (pintype "bidirectional"))
    )
    (net (code "84") (name "Net-(SF2_M2S010TQ1A-DDRIO53PB0)") (class "Default")
      (node (ref "SF2_M2S010TQ1") (pin "135") (pinfunction "DDRIO53PB0_135") (pintype "bidirectional"))
      (node (ref "U$1") (pin "P6") (pinfunction "A5_P6") (pintype "bidirectional"))
    )
    (net (code "85") (name "Net-(SF2_M2S010TQ1A-DDRIO55NB0)") (class "Default")
      (node (ref "SF2_M2S010TQ1") (pin "136") (pinfunction "DDRIO55NB0_136") (pintype "bidirectional"))
      (node (ref "U$1") (pin "P7") (pinfunction "A6_P7") (pintype "bidirectional"))
    )
    (net (code "86") (name "Net-(SF2_M2S010TQ1A-DDRIO55PB0{slash}CCC_NE0_CLKI3)") (class "Default")
      (node (ref "SF2_M2S010TQ1") (pin "137") (pinfunction "DDRIO55PB0/CCC_NE0_CLKI3_137") (pintype "bidirectional"))
      (node (ref "U$1") (pin "P8") (pinfunction "A7_P8") (pintype "bidirectional"))
    )
    (net (code "87") (name "Net-(SF2_M2S010TQ1A-DDRIO59NB0{slash}GB4)") (class "Default")
      (node (ref "SF2_M2S010TQ1") (pin "141") (pinfunction "DDRIO59NB0/GB4_141") (pintype "bidirectional"))
      (node (ref "U$1") (pin "P9") (pinfunction "A8_P9") (pintype "bidirectional"))
    )
    (net (code "88") (name "Net-(SF2_M2S010TQ1B-MSIO3NB2{slash}USB_DATA1_B)") (class "Default")
      (node (ref "R46") (pin "1") (pinfunction "1_1") (pintype "passive"))
      (node (ref "SF2_M2S010TQ1") (pin "90") (pinfunction "MSIO3NB2/USB_DATA1_B_90") (pintype "bidirectional"))
    )
    (net (code "89") (name "Net-(SF2_M2S010TQ1B-MSIO4NB2{slash}USB_DATA3_B)") (class "Default")
      (node (ref "R45") (pin "2") (pinfunction "2_2") (pintype "passive"))
      (node (ref "SF2_M2S010TQ1") (pin "91") (pinfunction "MSIO4NB2/USB_DATA3_B_91") (pintype "bidirectional"))
    )
    (net (code "90") (name "Net-(SF2_M2S010TQ1C-JTAGSEL)") (class "Default")
      (node (ref "R26") (pin "2") (pinfunction "2_2") (pintype "passive"))
      (node (ref "SF2_M2S010TQ1") (pin "73") (pinfunction "JTAGSEL_73") (pintype "bidirectional"))
    )
    (net (code "91") (name "Net-(SF2_M2S010TQ1C-JTAG_TCK{slash}M3_TCK)") (class "Default")
      (node (ref "SF2_M2S010TQ1") (pin "75") (pinfunction "JTAG_TCK/M3_TCK_75") (pintype "bidirectional"))
      (node (ref "USB") (pin "16") (pinfunction "ADBUS0_16") (pintype "bidirectional"))
    )
    (net (code "92") (name "Net-(SF2_M2S010TQ1C-JTAG_TDI{slash}M3_TDI)") (class "Default")
      (node (ref "SF2_M2S010TQ1") (pin "79") (pinfunction "JTAG_TDI/M3_TDI_79") (pintype "bidirectional"))
      (node (ref "USB") (pin "17") (pinfunction "ADBUS1_17") (pintype "bidirectional"))
    )
    (net (code "93") (name "Net-(SF2_M2S010TQ1C-JTAG_TDO{slash}M3_TDO{slash}M3_SWO)") (class "Default")
      (node (ref "SF2_M2S010TQ1") (pin "74") (pinfunction "JTAG_TDO/M3_TDO/M3_SWO_74") (pintype "bidirectional"))
      (node (ref "USB") (pin "18") (pinfunction "ADBUS2_18") (pintype "bidirectional"))
    )
    (net (code "94") (name "Net-(SF2_M2S010TQ1C-JTAG_TMS{slash}M3_TMS{slash}M3_SWDIO)") (class "Default")
      (node (ref "SF2_M2S010TQ1") (pin "78") (pinfunction "JTAG_TMS/M3_TMS/M3_SWDIO_78") (pintype "bidirectional"))
      (node (ref "USB") (pin "19") (pinfunction "ADBUS3_19") (pintype "bidirectional"))
    )
    (net (code "95") (name "Net-(SF2_M2S010TQ1D-MSIO105NB4)") (class "Default")
      (node (ref "R50") (pin "1") (pinfunction "1_1") (pintype "passive"))
      (node (ref "SF2_M2S010TQ1") (pin "53") (pinfunction "MSIO105NB4_53") (pintype "bidirectional"))
    )
    (net (code "96") (name "Net-(SF2_M2S010TQ1D-MSIO106NB4)") (class "Default")
      (node (ref "R56") (pin "2") (pinfunction "2_2") (pintype "passive"))
      (node (ref "SF2_M2S010TQ1") (pin "56") (pinfunction "MSIO106NB4_56") (pintype "bidirectional"))
    )
    (net (code "97") (name "Net-(SF2_M2S010TQ1D-MSIO106PB4)") (class "Default")
      (node (ref "R51") (pin "1") (pinfunction "1_1") (pintype "passive"))
      (node (ref "SF2_M2S010TQ1") (pin "55") (pinfunction "MSIO106PB4_55") (pintype "bidirectional"))
    )
    (net (code "98") (name "Net-(SF2_M2S010TQ1D-MSIO108PB4)") (class "Default")
      (node (ref "R55") (pin "2") (pinfunction "2_2") (pintype "passive"))
      (node (ref "SF2_M2S010TQ1") (pin "57") (pinfunction "MSIO108PB4_57") (pintype "bidirectional"))
    )
    (net (code "99") (name "Net-(SF2_M2S010TQ1E-MSIOD93PB6)") (class "Default")
      (node (ref "SF2_M2S010TQ1") (pin "30") (pinfunction "MSIOD93PB6_30") (pintype "bidirectional"))
      (node (ref "U$3") (pin "P7") (pinfunction "A6_P7") (pintype "bidirectional"))
    )
    (net (code "100") (name "Net-(SF2_M2S010TQ1E-MSIOD96NB6)") (class "Default")
      (node (ref "SF2_M2S010TQ1") (pin "33") (pinfunction "MSIOD96NB6_33") (pintype "bidirectional"))
      (node (ref "U$3") (pin "P3") (pinfunction "A2_P3") (pintype "bidirectional"))
    )
    (net (code "101") (name "Net-(SF2_M2S010TQ1E-MSIOD96PB6)") (class "Default")
      (node (ref "SF2_M2S010TQ1") (pin "32") (pinfunction "MSIOD96PB6_32") (pintype "bidirectional"))
      (node (ref "U$3") (pin "P1") (pinfunction "A1_P1") (pintype "bidirectional"))
    )
    (net (code "102") (name "Net-(SF2_M2S010TQ1E-MSIOD98NB6)") (class "Default")
      (node (ref "SF2_M2S010TQ1") (pin "36") (pinfunction "MSIOD98NB6_36") (pintype "bidirectional"))
      (node (ref "U$3") (pin "P4") (pinfunction "A3_P4") (pintype "bidirectional"))
    )
    (net (code "103") (name "Net-(SF2_M2S010TQ1E-MSIOD99NB6)") (class "Default")
      (node (ref "SF2_M2S010TQ1") (pin "38") (pinfunction "MSIOD99NB6_38") (pintype "bidirectional"))
      (node (ref "U$3") (pin "P6") (pinfunction "A5_P6") (pintype "bidirectional"))
    )
    (net (code "104") (name "Net-(SF2_M2S010TQ1E-MSIOD99PB6)") (class "Default")
      (node (ref "SF2_M2S010TQ1") (pin "37") (pinfunction "MSIOD99PB6_37") (pintype "bidirectional"))
      (node (ref "U$3") (pin "P5") (pinfunction "A4_P5") (pintype "bidirectional"))
    )
    (net (code "105") (name "Net-(SF2_M2S010TQ1F-MSIO64NB7)") (class "Default")
      (node (ref "R60") (pin "1") (pinfunction "1_1") (pintype "passive"))
      (node (ref "SF2_M2S010TQ1") (pin "1") (pinfunction "MSIO64NB7_1") (pintype "bidirectional"))
    )
    (net (code "106") (name "Net-(SF2_M2S010TQ1F-MSIO64PB7)") (class "Default")
      (node (ref "R61") (pin "1") (pinfunction "1_1") (pintype "passive"))
      (node (ref "SF2_M2S010TQ1") (pin "2") (pinfunction "MSIO64PB7_2") (pintype "bidirectional"))
    )
    (net (code "107") (name "Net-(SF2_M2S010TQ1G-CCC_NE0_PLL_VDDA)") (class "Default")
      (node (ref "C5") (pin "2") (pinfunction "2_2") (pintype "passive"))
      (node (ref "C6") (pin "2") (pinfunction "2_2") (pintype "passive"))
      (node (ref "R3") (pin "2") (pinfunction "2_2") (pintype "passive"))
      (node (ref "SF2_M2S010TQ1") (pin "109") (pinfunction "CCC_NE0_PLL_VDDA_109") (pintype "bidirectional"))
    )
    (net (code "108") (name "Net-(SF2_M2S010TQ1G-CCC_NE0_PLL_VSSA)") (class "Default")
      (node (ref "C5") (pin "1") (pinfunction "1_1") (pintype "passive"))
      (node (ref "C6") (pin "1") (pinfunction "1_1") (pintype "passive"))
      (node (ref "SF2_M2S010TQ1") (pin "108") (pinfunction "CCC_NE0_PLL_VSSA_108") (pintype "bidirectional"))
    )
    (net (code "109") (name "Net-(SF2_M2S010TQ1G-CCC_NE1_PLL_VDDA)") (class "Default")
      (node (ref "C3") (pin "2") (pinfunction "2_2") (pintype "passive"))
      (node (ref "C4") (pin "2") (pinfunction "2_2") (pintype "passive"))
      (node (ref "R2") (pin "2") (pinfunction "2_2") (pintype "passive"))
      (node (ref "SF2_M2S010TQ1") (pin "107") (pinfunction "CCC_NE1_PLL_VDDA_107") (pintype "bidirectional"))
    )
    (net (code "110") (name "Net-(SF2_M2S010TQ1G-CCC_NE1_PLL_VSSA)") (class "Default")
      (node (ref "C3") (pin "1") (pinfunction "1_1") (pintype "passive"))
      (node (ref "C4") (pin "1") (pinfunction "1_1") (pintype "passive"))
      (node (ref "SF2_M2S010TQ1") (pin "106") (pinfunction "CCC_NE1_PLL_VSSA_106") (pintype "bidirectional"))
    )
    (net (code "111") (name "Net-(SF2_M2S010TQ1G-DEVRST_N)") (class "Default")
      (node (ref "R1") (pin "2") (pinfunction "2_2") (pintype "passive"))
      (node (ref "SF2_M2S010TQ1") (pin "72") (pinfunction "DEVRST_N_72") (pintype "bidirectional"))
    )
    (net (code "112") (name "Net-(STAMP1_ADC_SG1-AIN0{slash}IEXC)") (class "Default")
      (node (ref "C46") (pin "2") (pinfunction "2_2") (pintype "passive"))
      (node (ref "C47") (pin "1") (pinfunction "1_1") (pintype "passive"))
      (node (ref "R29") (pin "1") (pinfunction "1_1") (pintype "passive"))
      (node (ref "STAMP1_ADC_SG1") (pin "11") (pinfunction "AIN0/IEXC_11") (pintype "bidirectional"))
    )
    (net (code "113") (name "Net-(STAMP1_ADC_SG1-AIN1{slash}IEXC)") (class "Default")
      (node (ref "C47") (pin "2") (pinfunction "2_2") (pintype "passive"))
      (node (ref "C48") (pin "1") (pinfunction "1_1") (pintype "passive"))
      (node (ref "R32") (pin "1") (pinfunction "1_1") (pintype "passive"))
      (node (ref "STAMP1_ADC_SG1") (pin "12") (pinfunction "AIN1/IEXC_12") (pintype "bidirectional"))
    )
    (net (code "114") (name "Net-(STAMP1_ADC_SG1-DOUT{slash}~{DRDY})") (class "Default")
      (node (ref "R31") (pin "2") (pinfunction "2_2") (pintype "passive"))
      (node (ref "STAMP1_ADC_SG1") (pin "26") (pinfunction "DOUT/~{DRDY}_26") (pintype "bidirectional"))
    )
    (net (code "115") (name "Net-(STAMP1_ADC_SG1-VREFOUT)") (class "Default")
      (node (ref "C34") (pin "1") (pinfunction "1_1") (pintype "passive"))
      (node (ref "STAMP1_ADC_SG1") (pin "9") (pinfunction "VREFOUT_9") (pintype "bidirectional"))
    )
    (net (code "116") (name "Net-(STAMP1_ADC_SG1-~{RESET})") (class "Default")
      (node (ref "R28") (pin "1") (pinfunction "1_1") (pintype "passive"))
      (node (ref "STAMP1_ADC_SG1") (pin "4") (pinfunction "~{RESET}_4") (pintype "bidirectional"))
    )
    (net (code "117") (name "Net-(STAMP1_ADC_SG2-AIN0{slash}IEXC)") (class "Default")
      (node (ref "C52") (pin "2") (pinfunction "2_2") (pintype "passive"))
      (node (ref "C53") (pin "1") (pinfunction "1_1") (pintype "passive"))
      (node (ref "R72") (pin "1") (pinfunction "1_1") (pintype "passive"))
      (node (ref "STAMP1_ADC_SG2") (pin "11") (pinfunction "AIN0/IEXC_11") (pintype "bidirectional"))
    )
    (net (code "118") (name "Net-(STAMP1_ADC_SG2-AIN1{slash}IEXC)") (class "Default")
      (node (ref "C53") (pin "2") (pinfunction "2_2") (pintype "passive"))
      (node (ref "C54") (pin "1") (pinfunction "1_1") (pintype "passive"))
      (node (ref "R73") (pin "1") (pinfunction "1_1") (pintype "passive"))
      (node (ref "STAMP1_ADC_SG2") (pin "12") (pinfunction "AIN1/IEXC_12") (pintype "bidirectional"))
    )
    (net (code "119") (name "Net-(STAMP1_ADC_SG2-DOUT{slash}~{DRDY})") (class "Default")
      (node (ref "R70") (pin "2") (pinfunction "2_2") (pintype "passive"))
      (node (ref "STAMP1_ADC_SG2") (pin "26") (pinfunction "DOUT/~{DRDY}_26") (pintype "bidirectional"))
    )
    (net (code "120") (name "Net-(STAMP1_ADC_SG2-VREFOUT)") (class "Default")
      (node (ref "C50") (pin "1") (pinfunction "1_1") (pintype "passive"))
      (node (ref "STAMP1_ADC_SG2") (pin "9") (pinfunction "VREFOUT_9") (pintype "bidirectional"))
    )
    (net (code "121") (name "Net-(STAMP1_ADC_SG2-~{RESET})") (class "Default")
      (node (ref "R68") (pin "1") (pinfunction "1_1") (pintype "passive"))
      (node (ref "STAMP1_ADC_SG2") (pin "4") (pinfunction "~{RESET}_4") (pintype "bidirectional"))
    )
    (net (code "122") (name "Net-(STAMP1_ADC_TEMP-AIN1{slash}IEXC)") (class "Default")
      (node (ref "C57") (pin "2") (pinfunction "2_2") (pintype "passive"))
      (node (ref "C58") (pin "1") (pinfunction "1_1") (pintype "passive"))
      (node (ref "R78") (pin "1") (pinfunction "1_1") (pintype "passive"))
      (node (ref "STAMP1_ADC_TEMP") (pin "12") (pinfunction "AIN1/IEXC_12") (pintype "bidirectional"))
    )
    (net (code "123") (name "Net-(STAMP1_ADC_TEMP-AIN2{slash}IEXC{slash}GPIO2)") (class "Default")
      (node (ref "C58") (pin "2") (pinfunction "2_2") (pintype "passive"))
      (node (ref "C59") (pin "1") (pinfunction "1_1") (pintype "passive"))
      (node (ref "R79") (pin "1") (pinfunction "1_1") (pintype "passive"))
      (node (ref "STAMP1_ADC_TEMP") (pin "17") (pinfunction "AIN2/IEXC/GPIO2_17") (pintype "bidirectional"))
    )
    (net (code "124") (name "Net-(STAMP1_ADC_TEMP-DOUT{slash}~{DRDY})") (class "Default")
      (node (ref "R75") (pin "2") (pinfunction "2_2") (pintype "passive"))
      (node (ref "STAMP1_ADC_TEMP") (pin "26") (pinfunction "DOUT/~{DRDY}_26") (pintype "bidirectional"))
    )
    (net (code "125") (name "Net-(STAMP1_ADC_TEMP-REFN0{slash}GPIO1)") (class "Default")
      (node (ref "C68") (pin "2") (pinfunction "2_2") (pintype "passive"))
      (node (ref "C69") (pin "1") (pinfunction "1_1") (pintype "passive"))
      (node (ref "R81") (pin "1") (pinfunction "1_1") (pintype "passive"))
      (node (ref "STAMP1_ADC_TEMP") (pin "6") (pinfunction "REFN0/GPIO1_6") (pintype "bidirectional"))
    )
    (net (code "126") (name "Net-(STAMP1_ADC_TEMP-REFP0{slash}GPIO0)") (class "Default")
      (node (ref "C68") (pin "1") (pinfunction "1_1") (pintype "passive"))
      (node (ref "C70") (pin "2") (pinfunction "2_2") (pintype "passive"))
      (node (ref "R80") (pin "1") (pinfunction "1_1") (pintype "passive"))
      (node (ref "STAMP1_ADC_TEMP") (pin "5") (pinfunction "REFP0/GPIO0_5") (pintype "bidirectional"))
    )
    (net (code "127") (name "Net-(STAMP1_ADC_TEMP-VREFOUT)") (class "Default")
      (node (ref "C63") (pin "1") (pinfunction "1_1") (pintype "passive"))
      (node (ref "STAMP1_ADC_TEMP") (pin "9") (pinfunction "VREFOUT_9") (pintype "bidirectional"))
    )
    (net (code "128") (name "Net-(STAMP1_ADC_TEMP-~{RESET})") (class "Default")
      (node (ref "R77") (pin "1") (pinfunction "1_1") (pintype "passive"))
      (node (ref "STAMP1_ADC_TEMP") (pin "4") (pinfunction "~{RESET}_4") (pintype "bidirectional"))
    )
    (net (code "129") (name "Net-(STAMP2_ADC_SG1-AIN0{slash}IEXC)") (class "Default")
      (node (ref "C95") (pin "2") (pinfunction "2_2") (pintype "passive"))
      (node (ref "C96") (pin "1") (pinfunction "1_1") (pintype "passive"))
      (node (ref "R84") (pin "1") (pinfunction "1_1") (pintype "passive"))
      (node (ref "STAMP2_ADC_SG1") (pin "11") (pinfunction "AIN0/IEXC_11") (pintype "bidirectional"))
    )
    (net (code "130") (name "Net-(STAMP2_ADC_SG1-AIN1{slash}IEXC)") (class "Default")
      (node (ref "C96") (pin "2") (pinfunction "2_2") (pintype "passive"))
      (node (ref "C97") (pin "1") (pinfunction "1_1") (pintype "passive"))
      (node (ref "R85") (pin "1") (pinfunction "1_1") (pintype "passive"))
      (node (ref "STAMP2_ADC_SG1") (pin "12") (pinfunction "AIN1/IEXC_12") (pintype "bidirectional"))
    )
    (net (code "131") (name "Net-(STAMP2_ADC_SG1-DOUT{slash}~{DRDY})") (class "Default")
      (node (ref "R83") (pin "2") (pinfunction "2_2") (pintype "passive"))
      (node (ref "STAMP2_ADC_SG1") (pin "26") (pinfunction "DOUT/~{DRDY}_26") (pintype "bidirectional"))
    )
    (net (code "132") (name "Net-(STAMP2_ADC_SG1-VREFOUT)") (class "Default")
      (node (ref "C93") (pin "1") (pinfunction "1_1") (pintype "passive"))
      (node (ref "STAMP2_ADC_SG1") (pin "9") (pinfunction "VREFOUT_9") (pintype "bidirectional"))
    )
    (net (code "133") (name "Net-(STAMP2_ADC_SG1-~{RESET})") (class "Default")
      (node (ref "R71") (pin "1") (pinfunction "1_1") (pintype "passive"))
      (node (ref "STAMP2_ADC_SG1") (pin "4") (pinfunction "~{RESET}_4") (pintype "bidirectional"))
    )
    (net (code "134") (name "Net-(STAMP2_ADC_SG2-AIN0{slash}IEXC)") (class "Default")
      (node (ref "C101") (pin "2") (pinfunction "2_2") (pintype "passive"))
      (node (ref "C102") (pin "1") (pinfunction "1_1") (pintype "passive"))
      (node (ref "R90") (pin "1") (pinfunction "1_1") (pintype "passive"))
      (node (ref "STAMP2_ADC_SG2") (pin "11") (pinfunction "AIN0/IEXC_11") (pintype "bidirectional"))
    )
    (net (code "135") (name "Net-(STAMP2_ADC_SG2-AIN1{slash}IEXC)") (class "Default")
      (node (ref "C102") (pin "2") (pinfunction "2_2") (pintype "passive"))
      (node (ref "C103") (pin "1") (pinfunction "1_1") (pintype "passive"))
      (node (ref "R91") (pin "1") (pinfunction "1_1") (pintype "passive"))
      (node (ref "STAMP2_ADC_SG2") (pin "12") (pinfunction "AIN1/IEXC_12") (pintype "bidirectional"))
    )
    (net (code "136") (name "Net-(STAMP2_ADC_SG2-DOUT{slash}~{DRDY})") (class "Default")
      (node (ref "R89") (pin "2") (pinfunction "2_2") (pintype "passive"))
      (node (ref "STAMP2_ADC_SG2") (pin "26") (pinfunction "DOUT/~{DRDY}_26") (pintype "bidirectional"))
    )
    (net (code "137") (name "Net-(STAMP2_ADC_SG2-VREFOUT)") (class "Default")
      (node (ref "C99") (pin "1") (pinfunction "1_1") (pintype "passive"))
      (node (ref "STAMP2_ADC_SG2") (pin "9") (pinfunction "VREFOUT_9") (pintype "bidirectional"))
    )
    (net (code "138") (name "Net-(STAMP2_ADC_SG2-~{RESET})") (class "Default")
      (node (ref "R87") (pin "1") (pinfunction "1_1") (pintype "passive"))
      (node (ref "STAMP2_ADC_SG2") (pin "4") (pinfunction "~{RESET}_4") (pintype "bidirectional"))
    )
    (net (code "139") (name "Net-(STAMP2_ADC_TEMP-AIN1{slash}IEXC)") (class "Default")
      (node (ref "C106") (pin "2") (pinfunction "2_2") (pintype "passive"))
      (node (ref "C107") (pin "1") (pinfunction "1_1") (pintype "passive"))
      (node (ref "R95") (pin "1") (pinfunction "1_1") (pintype "passive"))
      (node (ref "STAMP2_ADC_TEMP") (pin "12") (pinfunction "AIN1/IEXC_12") (pintype "bidirectional"))
    )
    (net (code "140") (name "Net-(STAMP2_ADC_TEMP-AIN2{slash}IEXC{slash}GPIO2)") (class "Default")
      (node (ref "C107") (pin "2") (pinfunction "2_2") (pintype "passive"))
      (node (ref "C108") (pin "1") (pinfunction "1_1") (pintype "passive"))
      (node (ref "R96") (pin "1") (pinfunction "1_1") (pintype "passive"))
      (node (ref "STAMP2_ADC_TEMP") (pin "17") (pinfunction "AIN2/IEXC/GPIO2_17") (pintype "bidirectional"))
    )
    (net (code "141") (name "Net-(STAMP2_ADC_TEMP-DOUT{slash}~{DRDY})") (class "Default")
      (node (ref "R93") (pin "2") (pinfunction "2_2") (pintype "passive"))
      (node (ref "STAMP2_ADC_TEMP") (pin "26") (pinfunction "DOUT/~{DRDY}_26") (pintype "bidirectional"))
    )
    (net (code "142") (name "Net-(STAMP2_ADC_TEMP-REFN0{slash}GPIO1)") (class "Default")
      (node (ref "C110") (pin "2") (pinfunction "2_2") (pintype "passive"))
      (node (ref "C111") (pin "1") (pinfunction "1_1") (pintype "passive"))
      (node (ref "R98") (pin "1") (pinfunction "1_1") (pintype "passive"))
      (node (ref "STAMP2_ADC_TEMP") (pin "6") (pinfunction "REFN0/GPIO1_6") (pintype "bidirectional"))
    )
    (net (code "143") (name "Net-(STAMP2_ADC_TEMP-REFP0{slash}GPIO0)") (class "Default")
      (node (ref "C110") (pin "1") (pinfunction "1_1") (pintype "passive"))
      (node (ref "C112") (pin "2") (pinfunction "2_2") (pintype "passive"))
      (node (ref "R97") (pin "1") (pinfunction "1_1") (pintype "passive"))
      (node (ref "STAMP2_ADC_TEMP") (pin "5") (pinfunction "REFP0/GPIO0_5") (pintype "bidirectional"))
    )
    (net (code "144") (name "Net-(STAMP2_ADC_TEMP-VREFOUT)") (class "Default")
      (node (ref "C109") (pin "1") (pinfunction "1_1") (pintype "passive"))
      (node (ref "STAMP2_ADC_TEMP") (pin "9") (pinfunction "VREFOUT_9") (pintype "bidirectional"))
    )
    (net (code "145") (name "Net-(STAMP2_ADC_TEMP-~{RESET})") (class "Default")
      (node (ref "R94") (pin "1") (pinfunction "1_1") (pintype "passive"))
      (node (ref "STAMP2_ADC_TEMP") (pin "4") (pinfunction "~{RESET}_4") (pintype "bidirectional"))
    )
    (net (code "146") (name "Net-(STAMP3_ADC_SG1-AIN0{slash}IEXC)") (class "Default")
      (node (ref "C137") (pin "2") (pinfunction "2_2") (pintype "passive"))
      (node (ref "C138") (pin "1") (pinfunction "1_1") (pintype "passive"))
      (node (ref "R122") (pin "1") (pinfunction "1_1") (pintype "passive"))
      (node (ref "STAMP3_ADC_SG1") (pin "11") (pinfunction "AIN0/IEXC_11") (pintype "bidirectional"))
    )
    (net (code "147") (name "Net-(STAMP3_ADC_SG1-AIN1{slash}IEXC)") (class "Default")
      (node (ref "C138") (pin "2") (pinfunction "2_2") (pintype "passive"))
      (node (ref "C139") (pin "1") (pinfunction "1_1") (pintype "passive"))
      (node (ref "R123") (pin "1") (pinfunction "1_1") (pintype "passive"))
      (node (ref "STAMP3_ADC_SG1") (pin "12") (pinfunction "AIN1/IEXC_12") (pintype "bidirectional"))
    )
    (net (code "148") (name "Net-(STAMP3_ADC_SG1-DOUT{slash}~{DRDY})") (class "Default")
      (node (ref "R121") (pin "2") (pinfunction "2_2") (pintype "passive"))
      (node (ref "STAMP3_ADC_SG1") (pin "26") (pinfunction "DOUT/~{DRDY}_26") (pintype "bidirectional"))
    )
    (net (code "149") (name "Net-(STAMP3_ADC_SG1-VREFOUT)") (class "Default")
      (node (ref "C135") (pin "1") (pinfunction "1_1") (pintype "passive"))
      (node (ref "STAMP3_ADC_SG1") (pin "9") (pinfunction "VREFOUT_9") (pintype "bidirectional"))
    )
    (net (code "150") (name "Net-(STAMP3_ADC_SG1-~{RESET})") (class "Default")
      (node (ref "R119") (pin "1") (pinfunction "1_1") (pintype "passive"))
      (node (ref "STAMP3_ADC_SG1") (pin "4") (pinfunction "~{RESET}_4") (pintype "bidirectional"))
    )
    (net (code "151") (name "Net-(STAMP3_ADC_SG2-AIN0{slash}IEXC)") (class "Default")
      (node (ref "C143") (pin "2") (pinfunction "2_2") (pintype "passive"))
      (node (ref "C144") (pin "1") (pinfunction "1_1") (pintype "passive"))
      (node (ref "R128") (pin "1") (pinfunction "1_1") (pintype "passive"))
      (node (ref "STAMP3_ADC_SG2") (pin "11") (pinfunction "AIN0/IEXC_11") (pintype "bidirectional"))
    )
    (net (code "152") (name "Net-(STAMP3_ADC_SG2-AIN1{slash}IEXC)") (class "Default")
      (node (ref "C144") (pin "2") (pinfunction "2_2") (pintype "passive"))
      (node (ref "C145") (pin "1") (pinfunction "1_1") (pintype "passive"))
      (node (ref "R129") (pin "1") (pinfunction "1_1") (pintype "passive"))
      (node (ref "STAMP3_ADC_SG2") (pin "12") (pinfunction "AIN1/IEXC_12") (pintype "bidirectional"))
    )
    (net (code "153") (name "Net-(STAMP3_ADC_SG2-DOUT{slash}~{DRDY})") (class "Default")
      (node (ref "R127") (pin "2") (pinfunction "2_2") (pintype "passive"))
      (node (ref "STAMP3_ADC_SG2") (pin "26") (pinfunction "DOUT/~{DRDY}_26") (pintype "bidirectional"))
    )
    (net (code "154") (name "Net-(STAMP3_ADC_SG2-VREFOUT)") (class "Default")
      (node (ref "C141") (pin "1") (pinfunction "1_1") (pintype "passive"))
      (node (ref "STAMP3_ADC_SG2") (pin "9") (pinfunction "VREFOUT_9") (pintype "bidirectional"))
    )
    (net (code "155") (name "Net-(STAMP3_ADC_SG2-~{RESET})") (class "Default")
      (node (ref "R125") (pin "1") (pinfunction "1_1") (pintype "passive"))
      (node (ref "STAMP3_ADC_SG2") (pin "4") (pinfunction "~{RESET}_4") (pintype "bidirectional"))
    )
    (net (code "156") (name "Net-(STAMP3_ADC_TEMP-AIN1{slash}IEXC)") (class "Default")
      (node (ref "C148") (pin "2") (pinfunction "2_2") (pintype "passive"))
      (node (ref "C149") (pin "1") (pinfunction "1_1") (pintype "passive"))
      (node (ref "R133") (pin "1") (pinfunction "1_1") (pintype "passive"))
      (node (ref "STAMP3_ADC_TEMP") (pin "12") (pinfunction "AIN1/IEXC_12") (pintype "bidirectional"))
    )
    (net (code "157") (name "Net-(STAMP3_ADC_TEMP-AIN2{slash}IEXC{slash}GPIO2)") (class "Default")
      (node (ref "C149") (pin "2") (pinfunction "2_2") (pintype "passive"))
      (node (ref "C150") (pin "1") (pinfunction "1_1") (pintype "passive"))
      (node (ref "R134") (pin "1") (pinfunction "1_1") (pintype "passive"))
      (node (ref "STAMP3_ADC_TEMP") (pin "17") (pinfunction "AIN2/IEXC/GPIO2_17") (pintype "bidirectional"))
    )
    (net (code "158") (name "Net-(STAMP3_ADC_TEMP-DOUT{slash}~{DRDY})") (class "Default")
      (node (ref "R131") (pin "2") (pinfunction "2_2") (pintype "passive"))
      (node (ref "STAMP3_ADC_TEMP") (pin "26") (pinfunction "DOUT/~{DRDY}_26") (pintype "bidirectional"))
    )
    (net (code "159") (name "Net-(STAMP3_ADC_TEMP-REFN0{slash}GPIO1)") (class "Default")
      (node (ref "C152") (pin "2") (pinfunction "2_2") (pintype "passive"))
      (node (ref "C153") (pin "1") (pinfunction "1_1") (pintype "passive"))
      (node (ref "R136") (pin "1") (pinfunction "1_1") (pintype "passive"))
      (node (ref "STAMP3_ADC_TEMP") (pin "6") (pinfunction "REFN0/GPIO1_6") (pintype "bidirectional"))
    )
    (net (code "160") (name "Net-(STAMP3_ADC_TEMP-REFP0{slash}GPIO0)") (class "Default")
      (node (ref "C152") (pin "1") (pinfunction "1_1") (pintype "passive"))
      (node (ref "C154") (pin "2") (pinfunction "2_2") (pintype "passive"))
      (node (ref "R135") (pin "1") (pinfunction "1_1") (pintype "passive"))
      (node (ref "STAMP3_ADC_TEMP") (pin "5") (pinfunction "REFP0/GPIO0_5") (pintype "bidirectional"))
    )
    (net (code "161") (name "Net-(STAMP3_ADC_TEMP-VREFOUT)") (class "Default")
      (node (ref "C151") (pin "1") (pinfunction "1_1") (pintype "passive"))
      (node (ref "STAMP3_ADC_TEMP") (pin "9") (pinfunction "VREFOUT_9") (pintype "bidirectional"))
    )
    (net (code "162") (name "Net-(STAMP3_ADC_TEMP-~{RESET})") (class "Default")
      (node (ref "R132") (pin "1") (pinfunction "1_1") (pintype "passive"))
      (node (ref "STAMP3_ADC_TEMP") (pin "4") (pinfunction "~{RESET}_4") (pintype "bidirectional"))
    )
    (net (code "163") (name "Net-(STAMP4_ADC_SG1-AIN0{slash}IEXC)") (class "Default")
      (node (ref "C158") (pin "2") (pinfunction "2_2") (pintype "passive"))
      (node (ref "C159") (pin "1") (pinfunction "1_1") (pintype "passive"))
      (node (ref "R141") (pin "1") (pinfunction "1_1") (pintype "passive"))
      (node (ref "STAMP4_ADC_SG1") (pin "11") (pinfunction "AIN0/IEXC_11") (pintype "bidirectional"))
    )
    (net (code "164") (name "Net-(STAMP4_ADC_SG1-AIN1{slash}IEXC)") (class "Default")
      (node (ref "C159") (pin "2") (pinfunction "2_2") (pintype "passive"))
      (node (ref "C160") (pin "1") (pinfunction "1_1") (pintype "passive"))
      (node (ref "R142") (pin "1") (pinfunction "1_1") (pintype "passive"))
      (node (ref "STAMP4_ADC_SG1") (pin "12") (pinfunction "AIN1/IEXC_12") (pintype "bidirectional"))
    )
    (net (code "165") (name "Net-(STAMP4_ADC_SG1-DOUT{slash}~{DRDY})") (class "Default")
      (node (ref "R140") (pin "2") (pinfunction "2_2") (pintype "passive"))
      (node (ref "STAMP4_ADC_SG1") (pin "26") (pinfunction "DOUT/~{DRDY}_26") (pintype "bidirectional"))
    )
    (net (code "166") (name "Net-(STAMP4_ADC_SG1-VREFOUT)") (class "Default")
      (node (ref "C156") (pin "1") (pinfunction "1_1") (pintype "passive"))
      (node (ref "STAMP4_ADC_SG1") (pin "9") (pinfunction "VREFOUT_9") (pintype "bidirectional"))
    )
    (net (code "167") (name "Net-(STAMP4_ADC_SG1-~{RESET})") (class "Default")
      (node (ref "R138") (pin "1") (pinfunction "1_1") (pintype "passive"))
      (node (ref "STAMP4_ADC_SG1") (pin "4") (pinfunction "~{RESET}_4") (pintype "bidirectional"))
    )
    (net (code "168") (name "Net-(STAMP4_ADC_SG2-AIN0{slash}IEXC)") (class "Default")
      (node (ref "C164") (pin "2") (pinfunction "2_2") (pintype "passive"))
      (node (ref "C165") (pin "1") (pinfunction "1_1") (pintype "passive"))
      (node (ref "R147") (pin "1") (pinfunction "1_1") (pintype "passive"))
      (node (ref "STAMP4_ADC_SG2") (pin "11") (pinfunction "AIN0/IEXC_11") (pintype "bidirectional"))
    )
    (net (code "169") (name "Net-(STAMP4_ADC_SG2-AIN1{slash}IEXC)") (class "Default")
      (node (ref "C165") (pin "2") (pinfunction "2_2") (pintype "passive"))
      (node (ref "C166") (pin "1") (pinfunction "1_1") (pintype "passive"))
      (node (ref "R148") (pin "1") (pinfunction "1_1") (pintype "passive"))
      (node (ref "STAMP4_ADC_SG2") (pin "12") (pinfunction "AIN1/IEXC_12") (pintype "bidirectional"))
    )
    (net (code "170") (name "Net-(STAMP4_ADC_SG2-DOUT{slash}~{DRDY})") (class "Default")
      (node (ref "R146") (pin "2") (pinfunction "2_2") (pintype "passive"))
      (node (ref "STAMP4_ADC_SG2") (pin "26") (pinfunction "DOUT/~{DRDY}_26") (pintype "bidirectional"))
    )
    (net (code "171") (name "Net-(STAMP4_ADC_SG2-VREFOUT)") (class "Default")
      (node (ref "C162") (pin "1") (pinfunction "1_1") (pintype "passive"))
      (node (ref "STAMP4_ADC_SG2") (pin "9") (pinfunction "VREFOUT_9") (pintype "bidirectional"))
    )
    (net (code "172") (name "Net-(STAMP4_ADC_SG2-~{RESET})") (class "Default")
      (node (ref "R144") (pin "1") (pinfunction "1_1") (pintype "passive"))
      (node (ref "STAMP4_ADC_SG2") (pin "4") (pinfunction "~{RESET}_4") (pintype "bidirectional"))
    )
    (net (code "173") (name "Net-(STAMP4_ADC_TEMP-AIN1{slash}IEXC)") (class "Default")
      (node (ref "C169") (pin "2") (pinfunction "2_2") (pintype "passive"))
      (node (ref "C170") (pin "1") (pinfunction "1_1") (pintype "passive"))
      (node (ref "R152") (pin "1") (pinfunction "1_1") (pintype "passive"))
      (node (ref "STAMP4_ADC_TEMP") (pin "12") (pinfunction "AIN1/IEXC_12") (pintype "bidirectional"))
    )
    (net (code "174") (name "Net-(STAMP4_ADC_TEMP-AIN2{slash}IEXC{slash}GPIO2)") (class "Default")
      (node (ref "C170") (pin "2") (pinfunction "2_2") (pintype "passive"))
      (node (ref "C171") (pin "1") (pinfunction "1_1") (pintype "passive"))
      (node (ref "R153") (pin "1") (pinfunction "1_1") (pintype "passive"))
      (node (ref "STAMP4_ADC_TEMP") (pin "17") (pinfunction "AIN2/IEXC/GPIO2_17") (pintype "bidirectional"))
    )
    (net (code "175") (name "Net-(STAMP4_ADC_TEMP-DOUT{slash}~{DRDY})") (class "Default")
      (node (ref "R150") (pin "2") (pinfunction "2_2") (pintype "passive"))
      (node (ref "STAMP4_ADC_TEMP") (pin "26") (pinfunction "DOUT/~{DRDY}_26") (pintype "bidirectional"))
    )
    (net (code "176") (name "Net-(STAMP4_ADC_TEMP-REFN0{slash}GPIO1)") (class "Default")
      (node (ref "C173") (pin "2") (pinfunction "2_2") (pintype "passive"))
      (node (ref "C174") (pin "1") (pinfunction "1_1") (pintype "passive"))
      (node (ref "R155") (pin "1") (pinfunction "1_1") (pintype "passive"))
      (node (ref "STAMP4_ADC_TEMP") (pin "6") (pinfunction "REFN0/GPIO1_6") (pintype "bidirectional"))
    )
    (net (code "177") (name "Net-(STAMP4_ADC_TEMP-REFP0{slash}GPIO0)") (class "Default")
      (node (ref "C173") (pin "1") (pinfunction "1_1") (pintype "passive"))
      (node (ref "C175") (pin "2") (pinfunction "2_2") (pintype "passive"))
      (node (ref "R154") (pin "1") (pinfunction "1_1") (pintype "passive"))
      (node (ref "STAMP4_ADC_TEMP") (pin "5") (pinfunction "REFP0/GPIO0_5") (pintype "bidirectional"))
    )
    (net (code "178") (name "Net-(STAMP4_ADC_TEMP-VREFOUT)") (class "Default")
      (node (ref "C172") (pin "1") (pinfunction "1_1") (pintype "passive"))
      (node (ref "STAMP4_ADC_TEMP") (pin "9") (pinfunction "VREFOUT_9") (pintype "bidirectional"))
    )
    (net (code "179") (name "Net-(STAMP4_ADC_TEMP-~{RESET})") (class "Default")
      (node (ref "R151") (pin "1") (pinfunction "1_1") (pintype "passive"))
      (node (ref "STAMP4_ADC_TEMP") (pin "4") (pinfunction "~{RESET}_4") (pintype "bidirectional"))
    )
    (net (code "180") (name "Net-(STAMP5_ADC_SG1-AIN0{slash}IEXC)") (class "Default")
      (node (ref "C116") (pin "2") (pinfunction "2_2") (pintype "passive"))
      (node (ref "C117") (pin "1") (pinfunction "1_1") (pintype "passive"))
      (node (ref "R103") (pin "1") (pinfunction "1_1") (pintype "passive"))
      (node (ref "STAMP5_ADC_SG1") (pin "11") (pinfunction "AIN0/IEXC_11") (pintype "bidirectional"))
    )
    (net (code "181") (name "Net-(STAMP5_ADC_SG1-AIN1{slash}IEXC)") (class "Default")
      (node (ref "C117") (pin "2") (pinfunction "2_2") (pintype "passive"))
      (node (ref "C118") (pin "1") (pinfunction "1_1") (pintype "passive"))
      (node (ref "R104") (pin "1") (pinfunction "1_1") (pintype "passive"))
      (node (ref "STAMP5_ADC_SG1") (pin "12") (pinfunction "AIN1/IEXC_12") (pintype "bidirectional"))
    )
    (net (code "182") (name "Net-(STAMP5_ADC_SG1-DOUT{slash}~{DRDY})") (class "Default")
      (node (ref "R102") (pin "2") (pinfunction "2_2") (pintype "passive"))
      (node (ref "STAMP5_ADC_SG1") (pin "26") (pinfunction "DOUT/~{DRDY}_26") (pintype "bidirectional"))
    )
    (net (code "183") (name "Net-(STAMP5_ADC_SG1-VREFOUT)") (class "Default")
      (node (ref "C114") (pin "1") (pinfunction "1_1") (pintype "passive"))
      (node (ref "STAMP5_ADC_SG1") (pin "9") (pinfunction "VREFOUT_9") (pintype "bidirectional"))
    )
    (net (code "184") (name "Net-(STAMP5_ADC_SG1-~{RESET})") (class "Default")
      (node (ref "R100") (pin "1") (pinfunction "1_1") (pintype "passive"))
      (node (ref "STAMP5_ADC_SG1") (pin "4") (pinfunction "~{RESET}_4") (pintype "bidirectional"))
    )
    (net (code "185") (name "Net-(STAMP5_ADC_SG2-AIN0{slash}IEXC)") (class "Default")
      (node (ref "C122") (pin "2") (pinfunction "2_2") (pintype "passive"))
      (node (ref "C123") (pin "1") (pinfunction "1_1") (pintype "passive"))
      (node (ref "R109") (pin "1") (pinfunction "1_1") (pintype "passive"))
      (node (ref "STAMP5_ADC_SG2") (pin "11") (pinfunction "AIN0/IEXC_11") (pintype "bidirectional"))
    )
    (net (code "186") (name "Net-(STAMP5_ADC_SG2-AIN1{slash}IEXC)") (class "Default")
      (node (ref "C123") (pin "2") (pinfunction "2_2") (pintype "passive"))
      (node (ref "C124") (pin "1") (pinfunction "1_1") (pintype "passive"))
      (node (ref "R110") (pin "1") (pinfunction "1_1") (pintype "passive"))
      (node (ref "STAMP5_ADC_SG2") (pin "12") (pinfunction "AIN1/IEXC_12") (pintype "bidirectional"))
    )
    (net (code "187") (name "Net-(STAMP5_ADC_SG2-DOUT{slash}~{DRDY})") (class "Default")
      (node (ref "R108") (pin "2") (pinfunction "2_2") (pintype "passive"))
      (node (ref "STAMP5_ADC_SG2") (pin "26") (pinfunction "DOUT/~{DRDY}_26") (pintype "bidirectional"))
    )
    (net (code "188") (name "Net-(STAMP5_ADC_SG2-VREFOUT)") (class "Default")
      (node (ref "C120") (pin "1") (pinfunction "1_1") (pintype "passive"))
      (node (ref "STAMP5_ADC_SG2") (pin "9") (pinfunction "VREFOUT_9") (pintype "bidirectional"))
    )
    (net (code "189") (name "Net-(STAMP5_ADC_SG2-~{RESET})") (class "Default")
      (node (ref "R106") (pin "1") (pinfunction "1_1") (pintype "passive"))
      (node (ref "STAMP5_ADC_SG2") (pin "4") (pinfunction "~{RESET}_4") (pintype "bidirectional"))
    )
    (net (code "190") (name "Net-(STAMP5_ADC_TEMP-AIN1{slash}IEXC)") (class "Default")
      (node (ref "C127") (pin "2") (pinfunction "2_2") (pintype "passive"))
      (node (ref "C128") (pin "1") (pinfunction "1_1") (pintype "passive"))
      (node (ref "R114") (pin "1") (pinfunction "1_1") (pintype "passive"))
      (node (ref "STAMP5_ADC_TEMP") (pin "12") (pinfunction "AIN1/IEXC_12") (pintype "bidirectional"))
    )
    (net (code "191") (name "Net-(STAMP5_ADC_TEMP-AIN2{slash}IEXC{slash}GPIO2)") (class "Default")
      (node (ref "C128") (pin "2") (pinfunction "2_2") (pintype "passive"))
      (node (ref "C129") (pin "1") (pinfunction "1_1") (pintype "passive"))
      (node (ref "R115") (pin "1") (pinfunction "1_1") (pintype "passive"))
      (node (ref "STAMP5_ADC_TEMP") (pin "17") (pinfunction "AIN2/IEXC/GPIO2_17") (pintype "bidirectional"))
    )
    (net (code "192") (name "Net-(STAMP5_ADC_TEMP-DOUT{slash}~{DRDY})") (class "Default")
      (node (ref "R112") (pin "2") (pinfunction "2_2") (pintype "passive"))
      (node (ref "STAMP5_ADC_TEMP") (pin "26") (pinfunction "DOUT/~{DRDY}_26") (pintype "bidirectional"))
    )
    (net (code "193") (name "Net-(STAMP5_ADC_TEMP-REFN0{slash}GPIO1)") (class "Default")
      (node (ref "C131") (pin "2") (pinfunction "2_2") (pintype "passive"))
      (node (ref "C132") (pin "1") (pinfunction "1_1") (pintype "passive"))
      (node (ref "R117") (pin "1") (pinfunction "1_1") (pintype "passive"))
      (node (ref "STAMP5_ADC_TEMP") (pin "6") (pinfunction "REFN0/GPIO1_6") (pintype "bidirectional"))
    )
    (net (code "194") (name "Net-(STAMP5_ADC_TEMP-REFP0{slash}GPIO0)") (class "Default")
      (node (ref "C131") (pin "1") (pinfunction "1_1") (pintype "passive"))
      (node (ref "C133") (pin "2") (pinfunction "2_2") (pintype "passive"))
      (node (ref "R116") (pin "1") (pinfunction "1_1") (pintype "passive"))
      (node (ref "STAMP5_ADC_TEMP") (pin "5") (pinfunction "REFP0/GPIO0_5") (pintype "bidirectional"))
    )
    (net (code "195") (name "Net-(STAMP5_ADC_TEMP-VREFOUT)") (class "Default")
      (node (ref "C130") (pin "1") (pinfunction "1_1") (pintype "passive"))
      (node (ref "STAMP5_ADC_TEMP") (pin "9") (pinfunction "VREFOUT_9") (pintype "bidirectional"))
    )
    (net (code "196") (name "Net-(STAMP5_ADC_TEMP-~{RESET})") (class "Default")
      (node (ref "R113") (pin "1") (pinfunction "1_1") (pintype "passive"))
      (node (ref "STAMP5_ADC_TEMP") (pin "4") (pinfunction "~{RESET}_4") (pintype "bidirectional"))
    )
    (net (code "197") (name "Net-(STAMP6_ADC_SG1-AIN0{slash}IEXC)") (class "Default")
      (node (ref "C200") (pin "2") (pinfunction "2_2") (pintype "passive"))
      (node (ref "C201") (pin "1") (pinfunction "1_1") (pintype "passive"))
      (node (ref "R179") (pin "1") (pinfunction "1_1") (pintype "passive"))
      (node (ref "STAMP6_ADC_SG1") (pin "11") (pinfunction "AIN0/IEXC_11") (pintype "bidirectional"))
    )
    (net (code "198") (name "Net-(STAMP6_ADC_SG1-AIN1{slash}IEXC)") (class "Default")
      (node (ref "C201") (pin "2") (pinfunction "2_2") (pintype "passive"))
      (node (ref "C202") (pin "1") (pinfunction "1_1") (pintype "passive"))
      (node (ref "R180") (pin "1") (pinfunction "1_1") (pintype "passive"))
      (node (ref "STAMP6_ADC_SG1") (pin "12") (pinfunction "AIN1/IEXC_12") (pintype "bidirectional"))
    )
    (net (code "199") (name "Net-(STAMP6_ADC_SG1-DOUT{slash}~{DRDY})") (class "Default")
      (node (ref "R178") (pin "2") (pinfunction "2_2") (pintype "passive"))
      (node (ref "STAMP6_ADC_SG1") (pin "26") (pinfunction "DOUT/~{DRDY}_26") (pintype "bidirectional"))
    )
    (net (code "200") (name "Net-(STAMP6_ADC_SG1-VREFOUT)") (class "Default")
      (node (ref "C198") (pin "1") (pinfunction "1_1") (pintype "passive"))
      (node (ref "STAMP6_ADC_SG1") (pin "9") (pinfunction "VREFOUT_9") (pintype "bidirectional"))
    )
    (net (code "201") (name "Net-(STAMP6_ADC_SG1-~{RESET})") (class "Default")
      (node (ref "R176") (pin "1") (pinfunction "1_1") (pintype "passive"))
      (node (ref "STAMP6_ADC_SG1") (pin "4") (pinfunction "~{RESET}_4") (pintype "bidirectional"))
    )
    (net (code "202") (name "Net-(STAMP6_ADC_SG2-AIN0{slash}IEXC)") (class "Default")
      (node (ref "C206") (pin "2") (pinfunction "2_2") (pintype "passive"))
      (node (ref "C207") (pin "1") (pinfunction "1_1") (pintype "passive"))
      (node (ref "R185") (pin "1") (pinfunction "1_1") (pintype "passive"))
      (node (ref "STAMP6_ADC_SG2") (pin "11") (pinfunction "AIN0/IEXC_11") (pintype "bidirectional"))
    )
    (net (code "203") (name "Net-(STAMP6_ADC_SG2-AIN1{slash}IEXC)") (class "Default")
      (node (ref "C207") (pin "2") (pinfunction "2_2") (pintype "passive"))
      (node (ref "C208") (pin "1") (pinfunction "1_1") (pintype "passive"))
      (node (ref "R186") (pin "1") (pinfunction "1_1") (pintype "passive"))
      (node (ref "STAMP6_ADC_SG2") (pin "12") (pinfunction "AIN1/IEXC_12") (pintype "bidirectional"))
    )
    (net (code "204") (name "Net-(STAMP6_ADC_SG2-DOUT{slash}~{DRDY})") (class "Default")
      (node (ref "R184") (pin "2") (pinfunction "2_2") (pintype "passive"))
      (node (ref "STAMP6_ADC_SG2") (pin "26") (pinfunction "DOUT/~{DRDY}_26") (pintype "bidirectional"))
    )
    (net (code "205") (name "Net-(STAMP6_ADC_SG2-VREFOUT)") (class "Default")
      (node (ref "C204") (pin "1") (pinfunction "1_1") (pintype "passive"))
      (node (ref "STAMP6_ADC_SG2") (pin "9") (pinfunction "VREFOUT_9") (pintype "bidirectional"))
    )
    (net (code "206") (name "Net-(STAMP6_ADC_SG2-~{RESET})") (class "Default")
      (node (ref "R182") (pin "1") (pinfunction "1_1") (pintype "passive"))
      (node (ref "STAMP6_ADC_SG2") (pin "4") (pinfunction "~{RESET}_4") (pintype "bidirectional"))
    )
    (net (code "207") (name "Net-(STAMP6_ADC_TEMP-AIN1{slash}IEXC)") (class "Default")
      (node (ref "C211") (pin "2") (pinfunction "2_2") (pintype "passive"))
      (node (ref "C212") (pin "1") (pinfunction "1_1") (pintype "passive"))
      (node (ref "R190") (pin "1") (pinfunction "1_1") (pintype "passive"))
      (node (ref "STAMP6_ADC_TEMP") (pin "12") (pinfunction "AIN1/IEXC_12") (pintype "bidirectional"))
    )
    (net (code "208") (name "Net-(STAMP6_ADC_TEMP-AIN2{slash}IEXC{slash}GPIO2)") (class "Default")
      (node (ref "C212") (pin "2") (pinfunction "2_2") (pintype "passive"))
      (node (ref "C213") (pin "1") (pinfunction "1_1") (pintype "passive"))
      (node (ref "R191") (pin "1") (pinfunction "1_1") (pintype "passive"))
      (node (ref "STAMP6_ADC_TEMP") (pin "17") (pinfunction "AIN2/IEXC/GPIO2_17") (pintype "bidirectional"))
    )
    (net (code "209") (name "Net-(STAMP6_ADC_TEMP-DOUT{slash}~{DRDY})") (class "Default")
      (node (ref "R188") (pin "2") (pinfunction "2_2") (pintype "passive"))
      (node (ref "STAMP6_ADC_TEMP") (pin "26") (pinfunction "DOUT/~{DRDY}_26") (pintype "bidirectional"))
    )
    (net (code "210") (name "Net-(STAMP6_ADC_TEMP-REFN0{slash}GPIO1)") (class "Default")
      (node (ref "C215") (pin "2") (pinfunction "2_2") (pintype "passive"))
      (node (ref "C216") (pin "1") (pinfunction "1_1") (pintype "passive"))
      (node (ref "R193") (pin "1") (pinfunction "1_1") (pintype "passive"))
      (node (ref "STAMP6_ADC_TEMP") (pin "6") (pinfunction "REFN0/GPIO1_6") (pintype "bidirectional"))
    )
    (net (code "211") (name "Net-(STAMP6_ADC_TEMP-REFP0{slash}GPIO0)") (class "Default")
      (node (ref "C215") (pin "1") (pinfunction "1_1") (pintype "passive"))
      (node (ref "C217") (pin "2") (pinfunction "2_2") (pintype "passive"))
      (node (ref "R192") (pin "1") (pinfunction "1_1") (pintype "passive"))
      (node (ref "STAMP6_ADC_TEMP") (pin "5") (pinfunction "REFP0/GPIO0_5") (pintype "bidirectional"))
    )
    (net (code "212") (name "Net-(STAMP6_ADC_TEMP-VREFOUT)") (class "Default")
      (node (ref "C214") (pin "1") (pinfunction "1_1") (pintype "passive"))
      (node (ref "STAMP6_ADC_TEMP") (pin "9") (pinfunction "VREFOUT_9") (pintype "bidirectional"))
    )
    (net (code "213") (name "Net-(STAMP6_ADC_TEMP-~{RESET})") (class "Default")
      (node (ref "R189") (pin "1") (pinfunction "1_1") (pintype "passive"))
      (node (ref "STAMP6_ADC_TEMP") (pin "4") (pinfunction "~{RESET}_4") (pintype "bidirectional"))
    )
    (net (code "214") (name "Net-(U$1-B1)") (class "Default")
      (node (ref "R36") (pin "2") (pinfunction "2_2") (pintype "passive"))
      (node (ref "U$1") (pin "P20") (pinfunction "B1_P20") (pintype "bidirectional"))
    )
    (net (code "215") (name "Net-(U$1-B2)") (class "Default")
      (node (ref "R35") (pin "2") (pinfunction "2_2") (pintype "passive"))
      (node (ref "U$1") (pin "P18") (pinfunction "B2_P18") (pintype "bidirectional"))
    )
    (net (code "216") (name "Net-(U$2-B1)") (class "Default")
      (node (ref "R41") (pin "1") (pinfunction "1_1") (pintype "passive"))
      (node (ref "U$2") (pin "P20") (pinfunction "B1_P20") (pintype "bidirectional"))
    )
    (net (code "217") (name "Net-(U$2-B2)") (class "Default")
      (node (ref "R40") (pin "1") (pinfunction "1_1") (pintype "passive"))
      (node (ref "U$2") (pin "P18") (pinfunction "B2_P18") (pintype "bidirectional"))
    )
    (net (code "218") (name "Net-(U$5-OUT)") (class "Default")
      (node (ref "R14") (pin "1") (pinfunction "1_1") (pintype "passive"))
      (node (ref "U$5") (pin "P3") (pinfunction "OUT_P3") (pintype "bidirectional"))
    )
    (net (code "219") (name "Net-(U$6-3)") (class "Default")
      (node (ref "R29") (pin "2") (pinfunction "2_2") (pintype "passive"))
      (node (ref "U$6") (pin "P$3") (pinfunction "3_P$3") (pintype "passive"))
    )
    (net (code "220") (name "Net-(U$7-3)") (class "Default")
      (node (ref "R72") (pin "2") (pinfunction "2_2") (pintype "passive"))
      (node (ref "U$7") (pin "P$3") (pinfunction "3_P$3") (pintype "passive"))
    )
    (net (code "221") (name "Net-(U$9-3)") (class "Default")
      (node (ref "R84") (pin "2") (pinfunction "2_2") (pintype "passive"))
      (node (ref "U$9") (pin "P$3") (pinfunction "3_P$3") (pintype "passive"))
    )
    (net (code "222") (name "Net-(U$10-3)") (class "Default")
      (node (ref "R90") (pin "2") (pinfunction "2_2") (pintype "passive"))
      (node (ref "U$10") (pin "P$3") (pinfunction "3_P$3") (pintype "passive"))
    )
    (net (code "223") (name "Net-(U$11-3)") (class "Default")
      (node (ref "R103") (pin "2") (pinfunction "2_2") (pintype "passive"))
      (node (ref "U$11") (pin "P$3") (pinfunction "3_P$3") (pintype "passive"))
    )
    (net (code "224") (name "Net-(U$12-3)") (class "Default")
      (node (ref "R109") (pin "2") (pinfunction "2_2") (pintype "passive"))
      (node (ref "U$12") (pin "P$3") (pinfunction "3_P$3") (pintype "passive"))
    )
    (net (code "225") (name "Net-(U$13-3)") (class "Default")
      (node (ref "R122") (pin "2") (pinfunction "2_2") (pintype "passive"))
      (node (ref "U$13") (pin "P$3") (pinfunction "3_P$3") (pintype "passive"))
    )
    (net (code "226") (name "Net-(U$14-3)") (class "Default")
      (node (ref "R128") (pin "2") (pinfunction "2_2") (pintype "passive"))
      (node (ref "U$14") (pin "P$3") (pinfunction "3_P$3") (pintype "passive"))
    )
    (net (code "227") (name "Net-(U$15-3)") (class "Default")
      (node (ref "R141") (pin "2") (pinfunction "2_2") (pintype "passive"))
      (node (ref "U$15") (pin "P$3") (pinfunction "3_P$3") (pintype "passive"))
    )
    (net (code "228") (name "Net-(U$16-3)") (class "Default")
      (node (ref "R147") (pin "2") (pinfunction "2_2") (pintype "passive"))
      (node (ref "U$16") (pin "P$3") (pinfunction "3_P$3") (pintype "passive"))
    )
    (net (code "229") (name "Net-(U$19-3)") (class "Default")
      (node (ref "R179") (pin "2") (pinfunction "2_2") (pintype "passive"))
      (node (ref "U$19") (pin "P$3") (pinfunction "3_P$3") (pintype "passive"))
    )
    (net (code "230") (name "Net-(U$20-3)") (class "Default")
      (node (ref "R185") (pin "2") (pinfunction "2_2") (pintype "passive"))
      (node (ref "U$20") (pin "P$3") (pinfunction "3_P$3") (pintype "passive"))
    )
    (net (code "231") (name "Net-(USB-NRESET)") (class "Default")
      (node (ref "R57") (pin "2") (pinfunction "2_2") (pintype "passive"))
      (node (ref "USB") (pin "14") (pinfunction "NRESET_14") (pintype "bidirectional"))
    )
    (net (code "232") (name "Net-(USB-OSCI)") (class "Default")
      (node (ref "C74") (pin "1") (pinfunction "1_1") (pintype "passive"))
      (node (ref "Q2") (pin "2") (pinfunction "2_2") (pintype "passive"))
      (node (ref "USB") (pin "2") (pinfunction "OSCI_2") (pintype "bidirectional"))
    )
    (net (code "233") (name "Net-(USB-OSCO)") (class "Default")
      (node (ref "C75") (pin "1") (pinfunction "1_1") (pintype "passive"))
      (node (ref "Q2") (pin "1") (pinfunction "1_1") (pintype "passive"))
      (node (ref "USB") (pin "3") (pinfunction "OSCO_3") (pintype "bidirectional"))
    )
    (net (code "234") (name "Net-(USB-REF)") (class "Default")
      (node (ref "R9") (pin "2") (pinfunction "2_2") (pintype "passive"))
      (node (ref "USB") (pin "6") (pinfunction "REF_6") (pintype "bidirectional"))
    )
    (net (code "235") (name "Net-(USB-VPHY)") (class "Default")
      (node (ref "C22") (pin "1") (pinfunction "1_1") (pintype "passive"))
      (node (ref "C24") (pin "1") (pinfunction "1_1") (pintype "passive"))
      (node (ref "L1") (pin "2") (pinfunction "2_2") (pintype "passive"))
      (node (ref "USB") (pin "4") (pinfunction "VPHY_4") (pintype "bidirectional"))
    )
    (net (code "236") (name "Net-(USB-VPLL)") (class "Default")
      (node (ref "C25") (pin "2") (pinfunction "2_2") (pintype "passive"))
      (node (ref "C26") (pin "2") (pinfunction "2_2") (pintype "passive"))
      (node (ref "L2") (pin "2") (pinfunction "2_2") (pintype "passive"))
      (node (ref "USB") (pin "9") (pinfunction "VPLL_9") (pintype "bidirectional"))
    )
    (net (code "237") (name "Net-(USB-VREGOUT)") (class "Default")
      (node (ref "C76") (pin "2") (pinfunction "2_2") (pintype "passive"))
      (node (ref "C77") (pin "2") (pinfunction "2_2") (pintype "passive"))
      (node (ref "C78") (pin "2") (pinfunction "2_2") (pintype "passive"))
      (node (ref "C79") (pin "2") (pinfunction "2_2") (pintype "passive"))
      (node (ref "USB") (pin "12") (pinfunction "VCORE_12") (pintype "bidirectional"))
      (node (ref "USB") (pin "37") (pinfunction "VCORE_37") (pintype "bidirectional"))
      (node (ref "USB") (pin "49") (pinfunction "VREGOUT_49") (pintype "bidirectional"))
      (node (ref "USB") (pin "64") (pinfunction "VCORE_64") (pintype "bidirectional"))
    )
    (net (code "238") (name "Net-(U_OPTO_3-A1)") (class "Default")
      (node (ref "R13") (pin "2") (pinfunction "2_2") (pintype "passive"))
      (node (ref "U_OPTO_3") (pin "1") (pinfunction "A1_1") (pintype "bidirectional"))
    )
    (net (code "239") (name "Net-(U_OPTO_4-A1)") (class "Default")
      (node (ref "R22") (pin "1") (pinfunction "1_1") (pintype "passive"))
      (node (ref "U_OPTO_4") (pin "1") (pinfunction "A1_1") (pintype "bidirectional"))
    )
    (net (code "240") (name "Net-(U_OPTO_4-C2)") (class "Default")
      (node (ref "R23") (pin "1") (pinfunction "1_1") (pintype "passive"))
      (node (ref "U_OPTO_4") (pin "4") (pinfunction "C2_4") (pintype "bidirectional"))
    )
    (net (code "241") (name "Net-(U_OPTO_5-A1)") (class "Default")
      (node (ref "R11") (pin "2") (pinfunction "2_2") (pintype "passive"))
      (node (ref "U_OPTO_5") (pin "1") (pinfunction "A1_1") (pintype "bidirectional"))
    )
    (net (code "242") (name "Net-(U_OPTO_5-A2)") (class "Default")
      (node (ref "R12") (pin "2") (pinfunction "2_2") (pintype "passive"))
      (node (ref "U_OPTO_5") (pin "3") (pinfunction "A2_3") (pintype "bidirectional"))
    )
    (net (code "243") (name "Net-(ZE05H-4P-2V-P$2)") (class "Default")
      (node (ref "R48") (pin "2") (pinfunction "2_2") (pintype "passive"))
      (node (ref "ZE05H-4P-2V") (pin "P2") (pinfunction "P$2_P2") (pintype "bidirectional"))
    )
    (net (code "244") (name "Net-(ZE05H-4P-2V-P$4)") (class "Default")
      (node (ref "R47") (pin "2") (pinfunction "2_2") (pintype "passive"))
      (node (ref "ZE05H-4P-2V") (pin "P4") (pinfunction "P$4_P4") (pintype "bidirectional"))
    )
    (net (code "245") (name "PROBE_A") (class "Default")
      (node (ref "PROBES") (pin "1") (pinfunction "1_1") (pintype "passive"))
      (node (ref "SF2_M2S010TQ1") (pin "47") (pinfunction "MSIO103PB4/PROBE_A_47") (pintype "bidirectional"))
    )
    (net (code "246") (name "PROBE_B") (class "Default")
      (node (ref "PROBES") (pin "3") (pinfunction "3_3") (pintype "passive"))
      (node (ref "SF2_M2S010TQ1") (pin "46") (pinfunction "MSIO103NB4/PROBE_B_46") (pintype "bidirectional"))
    )
    (net (code "247") (name "RXSM_LO") (class "Default")
      (node (ref "U_OPTO_5") (pin "2") (pinfunction "C1_2") (pintype "bidirectional"))
      (node (ref "X1") (pin "5") (pinfunction "5_5") (pintype "passive"))
    )
    (net (code "248") (name "RXSM_SODS") (class "Default")
      (node (ref "U_OPTO_5") (pin "4") (pinfunction "C2_4") (pintype "bidirectional"))
      (node (ref "X1") (pin "3") (pinfunction "3_3") (pintype "passive"))
    )
    (net (code "249") (name "RXSM_SOE") (class "Default")
      (node (ref "U_OPTO_3") (pin "2") (pinfunction "C1_2") (pintype "bidirectional"))
      (node (ref "X1") (pin "4") (pinfunction "4_4") (pintype "passive"))
    )
    (net (code "250") (name "SG_CLK") (class "Default")
      (node (ref "R14") (pin "2") (pinfunction "2_2") (pintype "passive"))
      (node (ref "STAMP1_ADC_SG1") (pin "3") (pinfunction "CLK_3") (pintype "bidirectional"))
      (node (ref "STAMP1_ADC_SG2") (pin "3") (pinfunction "CLK_3") (pintype "bidirectional"))
      (node (ref "STAMP2_ADC_SG1") (pin "3") (pinfunction "CLK_3") (pintype "bidirectional"))
      (node (ref "STAMP2_ADC_SG2") (pin "3") (pinfunction "CLK_3") (pintype "bidirectional"))
      (node (ref "STAMP3_ADC_SG1") (pin "3") (pinfunction "CLK_3") (pintype "bidirectional"))
      (node (ref "STAMP3_ADC_SG2") (pin "3") (pinfunction "CLK_3") (pintype "bidirectional"))
      (node (ref "STAMP4_ADC_SG1") (pin "3") (pinfunction "CLK_3") (pintype "bidirectional"))
      (node (ref "STAMP4_ADC_SG2") (pin "3") (pinfunction "CLK_3") (pintype "bidirectional"))
      (node (ref "STAMP5_ADC_SG1") (pin "3") (pinfunction "CLK_3") (pintype "bidirectional"))
      (node (ref "STAMP5_ADC_SG2") (pin "3") (pinfunction "CLK_3") (pintype "bidirectional"))
      (node (ref "STAMP6_ADC_SG1") (pin "3") (pinfunction "CLK_3") (pintype "bidirectional"))
      (node (ref "STAMP6_ADC_SG2") (pin "3") (pinfunction "CLK_3") (pintype "bidirectional"))
    )
    (net (code "251") (name "SODS") (class "Default")
      (node (ref "SF2_M2S010TQ1") (pin "124") (pinfunction "DDRIO44NB0_124") (pintype "bidirectional"))
      (node (ref "U_OPTO_5") (pin "6") (pinfunction "COL2_6") (pintype "input"))
    )
    (net (code "252") (name "SOE") (class "Default")
      (node (ref "SF2_M2S010TQ1") (pin "123") (pinfunction "DDRIO43PB0_123") (pintype "bidirectional"))
      (node (ref "U_OPTO_3") (pin "8") (pinfunction "COL1_8") (pintype "input"))
    )
    (net (code "253") (name "STAMP1_CS_SG1") (class "Default")
      (node (ref "STAMP1_ADC_SG1") (pin "24") (pinfunction "~{CS}_24") (pintype "bidirectional"))
      (node (ref "U$1") (pin "P13") (pinfunction "B7_P13") (pintype "bidirectional"))
    )
    (net (code "254") (name "STAMP1_CS_SG2") (class "Default")
      (node (ref "STAMP1_ADC_SG2") (pin "24") (pinfunction "~{CS}_24") (pintype "bidirectional"))
      (node (ref "U$1") (pin "P12") (pinfunction "B8_P12") (pintype "bidirectional"))
    )
    (net (code "255") (name "STAMP1_CS_TEMP") (class "Default")
      (node (ref "STAMP1_ADC_TEMP") (pin "24") (pinfunction "~{CS}_24") (pintype "bidirectional"))
      (node (ref "U$3") (pin "P12") (pinfunction "B8_P12") (pintype "bidirectional"))
    )
    (net (code "256") (name "STAMP1_CS_TEMP_1V2") (class "Default")
      (node (ref "SF2_M2S010TQ1") (pin "142") (pinfunction "DDRIO60NB0/CCC_NE1_CLKI3_142") (pintype "bidirectional"))
      (node (ref "U$3") (pin "P9") (pinfunction "A8_P9") (pintype "bidirectional"))
    )
    (net (code "257") (name "STAMP1_DRDY_SG1") (class "Default")
      (node (ref "STAMP1_ADC_SG1") (pin "25") (pinfunction "~{DRDY}_25") (pintype "bidirectional"))
      (node (ref "U$1") (pin "P16") (pinfunction "B4_P16") (pintype "bidirectional"))
    )
    (net (code "258") (name "STAMP1_DRDY_SG2") (class "Default")
      (node (ref "STAMP1_ADC_SG2") (pin "25") (pinfunction "~{DRDY}_25") (pintype "bidirectional"))
      (node (ref "U$1") (pin "P15") (pinfunction "B5_P15") (pintype "bidirectional"))
    )
    (net (code "259") (name "STAMP1_DRDY_TEMP") (class "Default")
      (node (ref "STAMP1_ADC_TEMP") (pin "25") (pinfunction "~{DRDY}_25") (pintype "bidirectional"))
      (node (ref "U$1") (pin "P14") (pinfunction "B6_P14") (pintype "bidirectional"))
    )
    (net (code "260") (name "STAMP1_MISO") (class "Default")
      (node (ref "R31") (pin "1") (pinfunction "1_1") (pintype "passive"))
      (node (ref "R70") (pin "1") (pinfunction "1_1") (pintype "passive"))
      (node (ref "R75") (pin "1") (pinfunction "1_1") (pintype "passive"))
      (node (ref "U$1") (pin "P17") (pinfunction "B3_P17") (pintype "bidirectional"))
    )
    (net (code "261") (name "STAMP1_MOSI") (class "Default")
      (node (ref "R35") (pin "1") (pinfunction "1_1") (pintype "passive"))
      (node (ref "STAMP1_ADC_SG1") (pin "27") (pinfunction "DIN_27") (pintype "bidirectional"))
      (node (ref "STAMP1_ADC_SG2") (pin "27") (pinfunction "DIN_27") (pintype "bidirectional"))
      (node (ref "STAMP1_ADC_TEMP") (pin "27") (pinfunction "DIN_27") (pintype "bidirectional"))
    )
    (net (code "262") (name "STAMP1_SCLK") (class "Default")
      (node (ref "R36") (pin "1") (pinfunction "1_1") (pintype "passive"))
      (node (ref "STAMP1_ADC_SG1") (pin "28") (pinfunction "SCLK_28") (pintype "bidirectional"))
      (node (ref "STAMP1_ADC_SG2") (pin "28") (pinfunction "SCLK_28") (pintype "bidirectional"))
      (node (ref "STAMP1_ADC_TEMP") (pin "28") (pinfunction "SCLK_28") (pintype "bidirectional"))
    )
    (net (code "263") (name "STAMP1_SG1_AIN1") (class "Default")
      (node (ref "CON_STAMP1") (pin "P$1") (pinfunction "P$1_P$1") (pintype "bidirectional"))
      (node (ref "U$6") (pin "P$6") (pinfunction "6_P$6") (pintype "passive"))
    )
    (net (code "264") (name "STAMP1_SG1_AIN2") (class "Default")
      (node (ref "CON_STAMP1") (pin "P$2") (pinfunction "P$2_P$2") (pintype "bidirectional"))
      (node (ref "U$6") (pin "P$4") (pinfunction "4_P$4") (pintype "passive"))
    )
    (net (code "265") (name "STAMP1_SG1_AIN3") (class "Default")
      (node (ref "CON_STAMP1") (pin "P$3") (pinfunction "P$3_P$3") (pintype "bidirectional"))
      (node (ref "U$6") (pin "P$2") (pinfunction "2_P$2") (pintype "passive"))
    )
    (net (code "266") (name "STAMP1_SG2_AIN1") (class "Default")
      (node (ref "CON_STAMP1") (pin "P$10") (pinfunction "P$10_P$10") (pintype "bidirectional"))
      (node (ref "U$7") (pin "P$6") (pinfunction "6_P$6") (pintype "passive"))
    )
    (net (code "267") (name "STAMP1_SG2_AIN2") (class "Default")
      (node (ref "CON_STAMP1") (pin "P$9") (pinfunction "P$9_P$9") (pintype "bidirectional"))
      (node (ref "U$7") (pin "P$4") (pinfunction "4_P$4") (pintype "passive"))
    )
    (net (code "268") (name "STAMP1_SG2_AIN3") (class "Default")
      (node (ref "CON_STAMP1") (pin "P$8") (pinfunction "P$8_P$8") (pintype "bidirectional"))
      (node (ref "U$7") (pin "P$2") (pinfunction "2_P$2") (pintype "passive"))
    )
    (net (code "269") (name "STAMP1_TEMP_AIN1") (class "Default")
      (node (ref "CON_STAMP1") (pin "P$4") (pinfunction "P$4_P$4") (pintype "bidirectional"))
      (node (ref "R78") (pin "2") (pinfunction "2_2") (pintype "passive"))
      (node (ref "STAMP1_ADC_TEMP") (pin "11") (pinfunction "AIN0/IEXC_11") (pintype "bidirectional"))
    )
    (net (code "270") (name "STAMP1_TEMP_AIN2") (class "Default")
      (node (ref "CON_STAMP1") (pin "P$5") (pinfunction "P$5_P$5") (pintype "bidirectional"))
      (node (ref "R79") (pin "2") (pinfunction "2_2") (pintype "passive"))
      (node (ref "STAMP1_ADC_TEMP") (pin "18") (pinfunction "AIN3/IEXC/GPIO3_18") (pintype "bidirectional"))
    )
    (net (code "271") (name "STAMP1_TEMP_AIN3") (class "Default")
      (node (ref "CON_STAMP1") (pin "P$6") (pinfunction "P$6_P$6") (pintype "bidirectional"))
      (node (ref "R80") (pin "2") (pinfunction "2_2") (pintype "passive"))
      (node (ref "R82") (pin "2") (pinfunction "2_2") (pintype "passive"))
    )
    (net (code "272") (name "STAMP2_CS_SG1") (class "Default")
      (node (ref "SF2_M2S010TQ1") (pin "87") (pinfunction "MSIO2NB2/USB_NXT_B_87") (pintype "bidirectional"))
      (node (ref "STAMP2_ADC_SG1") (pin "24") (pinfunction "~{CS}_24") (pintype "bidirectional"))
    )
    (net (code "273") (name "STAMP2_CS_SG2") (class "Default")
      (node (ref "SF2_M2S010TQ1") (pin "88") (pinfunction "MSIO3PB2/USB_DATA0_B_88") (pintype "bidirectional"))
      (node (ref "STAMP2_ADC_SG2") (pin "24") (pinfunction "~{CS}_24") (pintype "bidirectional"))
    )
    (net (code "274") (name "STAMP2_CS_TEMP") (class "Default")
      (node (ref "SF2_M2S010TQ1") (pin "89") (pinfunction "MSIO4PB2/USB_DATA2_B_89") (pintype "bidirectional"))
      (node (ref "STAMP2_ADC_TEMP") (pin "24") (pinfunction "~{CS}_24") (pintype "bidirectional"))
    )
    (net (code "275") (name "STAMP2_DRDY_SG1") (class "Default")
      (node (ref "SF2_M2S010TQ1") (pin "82") (pinfunction "MSIO1PB2/USB_XCLK_B_82") (pintype "bidirectional"))
      (node (ref "STAMP2_ADC_SG1") (pin "25") (pinfunction "~{DRDY}_25") (pintype "bidirectional"))
    )
    (net (code "276") (name "STAMP2_DRDY_SG2") (class "Default")
      (node (ref "SF2_M2S010TQ1") (pin "83") (pinfunction "MSIO1NB2/USB_DIR_B_83") (pintype "bidirectional"))
      (node (ref "STAMP2_ADC_SG2") (pin "25") (pinfunction "~{DRDY}_25") (pintype "bidirectional"))
    )
    (net (code "277") (name "STAMP2_DRDY_TEMP") (class "Default")
      (node (ref "SF2_M2S010TQ1") (pin "85") (pinfunction "MSIO2PB2/USB_STP_B_85") (pintype "bidirectional"))
      (node (ref "STAMP2_ADC_TEMP") (pin "25") (pinfunction "~{DRDY}_25") (pintype "bidirectional"))
    )
    (net (code "278") (name "STAMP2_MISO") (class "Default")
      (node (ref "R83") (pin "1") (pinfunction "1_1") (pintype "passive"))
      (node (ref "R89") (pin "1") (pinfunction "1_1") (pintype "passive"))
      (node (ref "R93") (pin "1") (pinfunction "1_1") (pintype "passive"))
      (node (ref "SF2_M2S010TQ1") (pin "81") (pinfunction "MSIO0NB2/USB_DATA7_B_81") (pintype "bidirectional"))
    )
    (net (code "279") (name "STAMP2_MOSI") (class "Default")
      (node (ref "R41") (pin "2") (pinfunction "2_2") (pintype "passive"))
      (node (ref "STAMP2_ADC_SG1") (pin "27") (pinfunction "DIN_27") (pintype "bidirectional"))
      (node (ref "STAMP2_ADC_SG2") (pin "27") (pinfunction "DIN_27") (pintype "bidirectional"))
      (node (ref "STAMP2_ADC_TEMP") (pin "27") (pinfunction "DIN_27") (pintype "bidirectional"))
    )
    (net (code "280") (name "STAMP2_SCLK") (class "Default")
      (node (ref "R40") (pin "2") (pinfunction "2_2") (pintype "passive"))
      (node (ref "STAMP2_ADC_SG1") (pin "28") (pinfunction "SCLK_28") (pintype "bidirectional"))
      (node (ref "STAMP2_ADC_SG2") (pin "28") (pinfunction "SCLK_28") (pintype "bidirectional"))
      (node (ref "STAMP2_ADC_TEMP") (pin "28") (pinfunction "SCLK_28") (pintype "bidirectional"))
    )
    (net (code "281") (name "STAMP2_SG1_AIN1") (class "Default")
      (node (ref "CON_STAMP2") (pin "P$1") (pinfunction "P$1_P$1") (pintype "bidirectional"))
      (node (ref "U$9") (pin "P$6") (pinfunction "6_P$6") (pintype "passive"))
    )
    (net (code "282") (name "STAMP2_SG1_AIN2") (class "Default")
      (node (ref "CON_STAMP2") (pin "P$2") (pinfunction "P$2_P$2") (pintype "bidirectional"))
      (node (ref "U$9") (pin "P$4") (pinfunction "4_P$4") (pintype "passive"))
    )
    (net (code "283") (name "STAMP2_SG1_AIN3") (class "Default")
      (node (ref "CON_STAMP2") (pin "P$3") (pinfunction "P$3_P$3") (pintype "bidirectional"))
      (node (ref "U$9") (pin "P$2") (pinfunction "2_P$2") (pintype "passive"))
    )
    (net (code "284") (name "STAMP2_SG2_AIN1") (class "Default")
      (node (ref "CON_STAMP2") (pin "P$10") (pinfunction "P$10_P$10") (pintype "bidirectional"))
      (node (ref "U$10") (pin "P$6") (pinfunction "6_P$6") (pintype "passive"))
    )
    (net (code "285") (name "STAMP2_SG2_AIN2") (class "Default")
      (node (ref "CON_STAMP2") (pin "P$9") (pinfunction "P$9_P$9") (pintype "bidirectional"))
      (node (ref "U$10") (pin "P$4") (pinfunction "4_P$4") (pintype "passive"))
    )
    (net (code "286") (name "STAMP2_SG2_AIN3") (class "Default")
      (node (ref "CON_STAMP2") (pin "P$8") (pinfunction "P$8_P$8") (pintype "bidirectional"))
      (node (ref "U$10") (pin "P$2") (pinfunction "2_P$2") (pintype "passive"))
    )
    (net (code "287") (name "STAMP2_TEMP_AIN1") (class "Default")
      (node (ref "CON_STAMP2") (pin "P$4") (pinfunction "P$4_P$4") (pintype "bidirectional"))
      (node (ref "R95") (pin "2") (pinfunction "2_2") (pintype "passive"))
      (node (ref "STAMP2_ADC_TEMP") (pin "11") (pinfunction "AIN0/IEXC_11") (pintype "bidirectional"))
    )
    (net (code "288") (name "STAMP2_TEMP_AIN2") (class "Default")
      (node (ref "CON_STAMP2") (pin "P$5") (pinfunction "P$5_P$5") (pintype "bidirectional"))
      (node (ref "R96") (pin "2") (pinfunction "2_2") (pintype "passive"))
      (node (ref "STAMP2_ADC_TEMP") (pin "18") (pinfunction "AIN3/IEXC/GPIO3_18") (pintype "bidirectional"))
    )
    (net (code "289") (name "STAMP2_TEMP_AIN3") (class "Default")
      (node (ref "CON_STAMP2") (pin "P$6") (pinfunction "P$6_P$6") (pintype "bidirectional"))
      (node (ref "R97") (pin "2") (pinfunction "2_2") (pintype "passive"))
      (node (ref "R99") (pin "2") (pinfunction "2_2") (pintype "passive"))
    )
    (net (code "290") (name "STAMP3_CS_SG1") (class "Default")
      (node (ref "SF2_M2S010TQ1") (pin "48") (pinfunction "MSIO104NB4/GB7_48") (pintype "bidirectional"))
      (node (ref "STAMP3_ADC_SG1") (pin "24") (pinfunction "~{CS}_24") (pintype "bidirectional"))
    )
    (net (code "291") (name "STAMP3_CS_SG2") (class "Default")
      (node (ref "SF2_M2S010TQ1") (pin "49") (pinfunction "MSIO104PB4/GB3_49") (pintype "bidirectional"))
      (node (ref "STAMP3_ADC_SG2") (pin "24") (pinfunction "~{CS}_24") (pintype "bidirectional"))
    )
    (net (code "292") (name "STAMP3_CS_TEMP") (class "Default")
      (node (ref "SF2_M2S010TQ1") (pin "52") (pinfunction "MSIO105PB4/CCC_NE0_CLKI0_52") (pintype "bidirectional"))
      (node (ref "STAMP3_ADC_TEMP") (pin "24") (pinfunction "~{CS}_24") (pintype "bidirectional"))
    )
    (net (code "293") (name "STAMP3_DRDY_SG1") (class "Default")
      (node (ref "SF2_M2S010TQ1") (pin "93") (pinfunction "MSIO5NB2/USB_DATA5_B_93") (pintype "bidirectional"))
      (node (ref "STAMP3_ADC_SG1") (pin "25") (pinfunction "~{DRDY}_25") (pintype "bidirectional"))
    )
    (net (code "294") (name "STAMP3_DRDY_SG2") (class "Default")
      (node (ref "SF2_M2S010TQ1") (pin "43") (pinfunction "MSIO102PB4_43") (pintype "bidirectional"))
      (node (ref "STAMP3_ADC_SG2") (pin "25") (pinfunction "~{DRDY}_25") (pintype "bidirectional"))
    )
    (net (code "295") (name "STAMP3_DRDY_TEMP") (class "Default")
      (node (ref "SF2_M2S010TQ1") (pin "44") (pinfunction "MSIO102NB4/CCC_NE1_CLKI0_44") (pintype "bidirectional"))
      (node (ref "STAMP3_ADC_TEMP") (pin "25") (pinfunction "~{DRDY}_25") (pintype "bidirectional"))
    )
    (net (code "296") (name "STAMP3_MISO") (class "Default")
      (node (ref "R121") (pin "1") (pinfunction "1_1") (pintype "passive"))
      (node (ref "R127") (pin "1") (pinfunction "1_1") (pintype "passive"))
      (node (ref "R131") (pin "1") (pinfunction "1_1") (pintype "passive"))
      (node (ref "SF2_M2S010TQ1") (pin "92") (pinfunction "MSIO5PB2/USB_DATA4_B_92") (pintype "bidirectional"))
    )
    (net (code "297") (name "STAMP3_MOSI") (class "Default")
      (node (ref "R45") (pin "1") (pinfunction "1_1") (pintype "passive"))
      (node (ref "STAMP3_ADC_SG1") (pin "27") (pinfunction "DIN_27") (pintype "bidirectional"))
      (node (ref "STAMP3_ADC_SG2") (pin "27") (pinfunction "DIN_27") (pintype "bidirectional"))
      (node (ref "STAMP3_ADC_TEMP") (pin "27") (pinfunction "DIN_27") (pintype "bidirectional"))
    )
    (net (code "298") (name "STAMP3_SCLK") (class "Default")
      (node (ref "R46") (pin "2") (pinfunction "2_2") (pintype "passive"))
      (node (ref "STAMP3_ADC_SG1") (pin "28") (pinfunction "SCLK_28") (pintype "bidirectional"))
      (node (ref "STAMP3_ADC_SG2") (pin "28") (pinfunction "SCLK_28") (pintype "bidirectional"))
      (node (ref "STAMP3_ADC_TEMP") (pin "28") (pinfunction "SCLK_28") (pintype "bidirectional"))
    )
    (net (code "299") (name "STAMP3_SG1_AIN1") (class "Default")
      (node (ref "CON_STAMP3") (pin "P$1") (pinfunction "P$1_P$1") (pintype "bidirectional"))
      (node (ref "U$13") (pin "P$6") (pinfunction "6_P$6") (pintype "passive"))
    )
    (net (code "300") (name "STAMP3_SG1_AIN2") (class "Default")
      (node (ref "CON_STAMP3") (pin "P$2") (pinfunction "P$2_P$2") (pintype "bidirectional"))
      (node (ref "U$13") (pin "P$4") (pinfunction "4_P$4") (pintype "passive"))
    )
    (net (code "301") (name "STAMP3_SG1_AIN3") (class "Default")
      (node (ref "CON_STAMP3") (pin "P$3") (pinfunction "P$3_P$3") (pintype "bidirectional"))
      (node (ref "U$13") (pin "P$2") (pinfunction "2_P$2") (pintype "passive"))
    )
    (net (code "302") (name "STAMP3_SG2_AIN1") (class "Default")
      (node (ref "CON_STAMP3") (pin "P$10") (pinfunction "P$10_P$10") (pintype "bidirectional"))
      (node (ref "U$14") (pin "P$6") (pinfunction "6_P$6") (pintype "passive"))
    )
    (net (code "303") (name "STAMP3_SG2_AIN2") (class "Default")
      (node (ref "CON_STAMP3") (pin "P$9") (pinfunction "P$9_P$9") (pintype "bidirectional"))
      (node (ref "U$14") (pin "P$4") (pinfunction "4_P$4") (pintype "passive"))
    )
    (net (code "304") (name "STAMP3_SG2_AIN3") (class "Default")
      (node (ref "CON_STAMP3") (pin "P$8") (pinfunction "P$8_P$8") (pintype "bidirectional"))
      (node (ref "U$14") (pin "P$2") (pinfunction "2_P$2") (pintype "passive"))
    )
    (net (code "305") (name "STAMP3_TEMP_AIN1") (class "Default")
      (node (ref "CON_STAMP3") (pin "P$4") (pinfunction "P$4_P$4") (pintype "bidirectional"))
      (node (ref "R133") (pin "2") (pinfunction "2_2") (pintype "passive"))
      (node (ref "STAMP3_ADC_TEMP") (pin "11") (pinfunction "AIN0/IEXC_11") (pintype "bidirectional"))
    )
    (net (code "306") (name "STAMP3_TEMP_AIN2") (class "Default")
      (node (ref "CON_STAMP3") (pin "P$5") (pinfunction "P$5_P$5") (pintype "bidirectional"))
      (node (ref "R134") (pin "2") (pinfunction "2_2") (pintype "passive"))
      (node (ref "STAMP3_ADC_TEMP") (pin "18") (pinfunction "AIN3/IEXC/GPIO3_18") (pintype "bidirectional"))
    )
    (net (code "307") (name "STAMP3_TEMP_AIN3") (class "Default")
      (node (ref "CON_STAMP3") (pin "P$6") (pinfunction "P$6_P$6") (pintype "bidirectional"))
      (node (ref "R135") (pin "2") (pinfunction "2_2") (pintype "passive"))
      (node (ref "R137") (pin "2") (pinfunction "2_2") (pintype "passive"))
    )
    (net (code "308") (name "STAMP4_CS_SG1") (class "Default")
      (node (ref "SF2_M2S010TQ1") (pin "61") (pinfunction "MSIO109NB4_61") (pintype "bidirectional"))
      (node (ref "STAMP4_ADC_SG1") (pin "24") (pinfunction "~{CS}_24") (pintype "bidirectional"))
    )
    (net (code "309") (name "STAMP4_CS_SG2") (class "Default")
      (node (ref "SF2_M2S010TQ1") (pin "60") (pinfunction "MSIO109PB4_60") (pintype "bidirectional"))
      (node (ref "STAMP4_ADC_SG2") (pin "24") (pinfunction "~{CS}_24") (pintype "bidirectional"))
    )
    (net (code "310") (name "STAMP4_CS_TEMP") (class "Default")
      (node (ref "SF2_M2S010TQ1") (pin "58") (pinfunction "MSIO108NB4_58") (pintype "bidirectional"))
      (node (ref "STAMP4_ADC_TEMP") (pin "24") (pinfunction "~{CS}_24") (pintype "bidirectional"))
    )
    (net (code "311") (name "STAMP4_DRDY_SG1") (class "Default")
      (node (ref "SF2_M2S010TQ1") (pin "66") (pinfunction "MSIO114PB4_66") (pintype "bidirectional"))
      (node (ref "STAMP4_ADC_SG1") (pin "25") (pinfunction "~{DRDY}_25") (pintype "bidirectional"))
    )
    (net (code "312") (name "STAMP4_DRDY_SG2") (class "Default")
      (node (ref "SF2_M2S010TQ1") (pin "64") (pinfunction "MSIO113NB4_64") (pintype "bidirectional"))
      (node (ref "STAMP4_ADC_SG2") (pin "25") (pinfunction "~{DRDY}_25") (pintype "bidirectional"))
    )
    (net (code "313") (name "STAMP4_DRDY_TEMP") (class "Default")
      (node (ref "SF2_M2S010TQ1") (pin "63") (pinfunction "MSIO113PB4_63") (pintype "bidirectional"))
      (node (ref "STAMP4_ADC_TEMP") (pin "25") (pinfunction "~{DRDY}_25") (pintype "bidirectional"))
    )
    (net (code "314") (name "STAMP4_MISO") (class "Default")
      (node (ref "R140") (pin "1") (pinfunction "1_1") (pintype "passive"))
      (node (ref "R146") (pin "1") (pinfunction "1_1") (pintype "passive"))
      (node (ref "R150") (pin "1") (pinfunction "1_1") (pintype "passive"))
      (node (ref "SF2_M2S010TQ1") (pin "67") (pinfunction "MSIO114NB4_67") (pintype "bidirectional"))
    )
    (net (code "315") (name "STAMP4_MOSI") (class "Default")
      (node (ref "R51") (pin "2") (pinfunction "2_2") (pintype "passive"))
      (node (ref "STAMP4_ADC_SG1") (pin "27") (pinfunction "DIN_27") (pintype "bidirectional"))
      (node (ref "STAMP4_ADC_SG2") (pin "27") (pinfunction "DIN_27") (pintype "bidirectional"))
      (node (ref "STAMP4_ADC_TEMP") (pin "27") (pinfunction "DIN_27") (pintype "bidirectional"))
    )
    (net (code "316") (name "STAMP4_SCLK") (class "Default")
      (node (ref "R50") (pin "2") (pinfunction "2_2") (pintype "passive"))
      (node (ref "STAMP4_ADC_SG1") (pin "28") (pinfunction "SCLK_28") (pintype "bidirectional"))
      (node (ref "STAMP4_ADC_SG2") (pin "28") (pinfunction "SCLK_28") (pintype "bidirectional"))
      (node (ref "STAMP4_ADC_TEMP") (pin "28") (pinfunction "SCLK_28") (pintype "bidirectional"))
    )
    (net (code "317") (name "STAMP4_SG1_AIN1") (class "Default")
      (node (ref "CON_STAMP4") (pin "P$1") (pinfunction "P$1_P$1") (pintype "bidirectional"))
      (node (ref "U$15") (pin "P$6") (pinfunction "6_P$6") (pintype "passive"))
    )
    (net (code "318") (name "STAMP4_SG1_AIN2") (class "Default")
      (node (ref "CON_STAMP4") (pin "P$2") (pinfunction "P$2_P$2") (pintype "bidirectional"))
      (node (ref "U$15") (pin "P$4") (pinfunction "4_P$4") (pintype "passive"))
    )
    (net (code "319") (name "STAMP4_SG1_AIN3") (class "Default")
      (node (ref "CON_STAMP4") (pin "P$3") (pinfunction "P$3_P$3") (pintype "bidirectional"))
      (node (ref "U$15") (pin "P$2") (pinfunction "2_P$2") (pintype "passive"))
    )
    (net (code "320") (name "STAMP4_SG2_AIN1") (class "Default")
      (node (ref "CON_STAMP4") (pin "P$10") (pinfunction "P$10_P$10") (pintype "bidirectional"))
      (node (ref "U$16") (pin "P$6") (pinfunction "6_P$6") (pintype "passive"))
    )
    (net (code "321") (name "STAMP4_SG2_AIN2") (class "Default")
      (node (ref "CON_STAMP4") (pin "P$9") (pinfunction "P$9_P$9") (pintype "bidirectional"))
      (node (ref "U$16") (pin "P$4") (pinfunction "4_P$4") (pintype "passive"))
    )
    (net (code "322") (name "STAMP4_SG2_AIN3") (class "Default")
      (node (ref "CON_STAMP4") (pin "P$8") (pinfunction "P$8_P$8") (pintype "bidirectional"))
      (node (ref "U$16") (pin "P$2") (pinfunction "2_P$2") (pintype "passive"))
    )
    (net (code "323") (name "STAMP4_TEMP_AIN1") (class "Default")
      (node (ref "CON_STAMP4") (pin "P$4") (pinfunction "P$4_P$4") (pintype "bidirectional"))
      (node (ref "R152") (pin "2") (pinfunction "2_2") (pintype "passive"))
      (node (ref "STAMP4_ADC_TEMP") (pin "11") (pinfunction "AIN0/IEXC_11") (pintype "bidirectional"))
    )
    (net (code "324") (name "STAMP4_TEMP_AIN2") (class "Default")
      (node (ref "CON_STAMP4") (pin "P$5") (pinfunction "P$5_P$5") (pintype "bidirectional"))
      (node (ref "R153") (pin "2") (pinfunction "2_2") (pintype "passive"))
      (node (ref "STAMP4_ADC_TEMP") (pin "18") (pinfunction "AIN3/IEXC/GPIO3_18") (pintype "bidirectional"))
    )
    (net (code "325") (name "STAMP4_TEMP_AIN3") (class "Default")
      (node (ref "CON_STAMP4") (pin "P$6") (pinfunction "P$6_P$6") (pintype "bidirectional"))
      (node (ref "R154") (pin "2") (pinfunction "2_2") (pintype "passive"))
      (node (ref "R156") (pin "2") (pinfunction "2_2") (pintype "passive"))
    )
    (net (code "326") (name "STAMP5_CS_SG1") (class "Default")
      (node (ref "STAMP5_ADC_SG1") (pin "24") (pinfunction "~{CS}_24") (pintype "bidirectional"))
      (node (ref "U$3") (pin "P15") (pinfunction "B5_P15") (pintype "bidirectional"))
    )
    (net (code "327") (name "STAMP5_CS_SG2") (class "Default")
      (node (ref "SF2_M2S010TQ1") (pin "13") (pinfunction "MSIO76NB7_13") (pintype "bidirectional"))
      (node (ref "STAMP5_ADC_SG2") (pin "24") (pinfunction "~{CS}_24") (pintype "bidirectional"))
    )
    (net (code "328") (name "STAMP5_CS_TEMP") (class "Default")
      (node (ref "SF2_M2S010TQ1") (pin "14") (pinfunction "MSIO76PB7_14") (pintype "bidirectional"))
      (node (ref "STAMP5_ADC_TEMP") (pin "24") (pinfunction "~{CS}_24") (pintype "bidirectional"))
    )
    (net (code "329") (name "STAMP5_DRDY_SG1") (class "Default")
      (node (ref "STAMP5_ADC_SG1") (pin "25") (pinfunction "~{DRDY}_25") (pintype "bidirectional"))
      (node (ref "U$3") (pin "P18") (pinfunction "B2_P18") (pintype "bidirectional"))
    )
    (net (code "330") (name "STAMP5_DRDY_SG2") (class "Default")
      (node (ref "STAMP5_ADC_SG2") (pin "25") (pinfunction "~{DRDY}_25") (pintype "bidirectional"))
      (node (ref "U$3") (pin "P17") (pinfunction "B3_P17") (pintype "bidirectional"))
    )
    (net (code "331") (name "STAMP5_DRDY_TEMP") (class "Default")
      (node (ref "STAMP5_ADC_TEMP") (pin "25") (pinfunction "~{DRDY}_25") (pintype "bidirectional"))
      (node (ref "U$3") (pin "P16") (pinfunction "B4_P16") (pintype "bidirectional"))
    )
    (net (code "332") (name "STAMP5_MISO") (class "Default")
      (node (ref "R102") (pin "1") (pinfunction "1_1") (pintype "passive"))
      (node (ref "R108") (pin "1") (pinfunction "1_1") (pintype "passive"))
      (node (ref "R112") (pin "1") (pinfunction "1_1") (pintype "passive"))
      (node (ref "U$3") (pin "P20") (pinfunction "B1_P20") (pintype "bidirectional"))
    )
    (net (code "333") (name "STAMP5_MOSI") (class "Default")
      (node (ref "R55") (pin "1") (pinfunction "1_1") (pintype "passive"))
      (node (ref "STAMP5_ADC_SG1") (pin "27") (pinfunction "DIN_27") (pintype "bidirectional"))
      (node (ref "STAMP5_ADC_SG2") (pin "27") (pinfunction "DIN_27") (pintype "bidirectional"))
      (node (ref "STAMP5_ADC_TEMP") (pin "27") (pinfunction "DIN_27") (pintype "bidirectional"))
    )
    (net (code "334") (name "STAMP5_SCLK") (class "Default")
      (node (ref "R56") (pin "1") (pinfunction "1_1") (pintype "passive"))
      (node (ref "STAMP5_ADC_SG1") (pin "28") (pinfunction "SCLK_28") (pintype "bidirectional"))
      (node (ref "STAMP5_ADC_SG2") (pin "28") (pinfunction "SCLK_28") (pintype "bidirectional"))
      (node (ref "STAMP5_ADC_TEMP") (pin "28") (pinfunction "SCLK_28") (pintype "bidirectional"))
    )
    (net (code "335") (name "STAMP5_SG1_AIN1") (class "Default")
      (node (ref "CON_STAMP5") (pin "P$1") (pinfunction "P$1_P$1") (pintype "bidirectional"))
      (node (ref "U$11") (pin "P$6") (pinfunction "6_P$6") (pintype "passive"))
    )
    (net (code "336") (name "STAMP5_SG1_AIN2") (class "Default")
      (node (ref "CON_STAMP5") (pin "P$2") (pinfunction "P$2_P$2") (pintype "bidirectional"))
      (node (ref "U$11") (pin "P$4") (pinfunction "4_P$4") (pintype "passive"))
    )
    (net (code "337") (name "STAMP5_SG1_AIN3") (class "Default")
      (node (ref "CON_STAMP5") (pin "P$3") (pinfunction "P$3_P$3") (pintype "bidirectional"))
      (node (ref "U$11") (pin "P$2") (pinfunction "2_P$2") (pintype "passive"))
    )
    (net (code "338") (name "STAMP5_SG2_AIN1") (class "Default")
      (node (ref "CON_STAMP5") (pin "P$10") (pinfunction "P$10_P$10") (pintype "bidirectional"))
      (node (ref "U$12") (pin "P$6") (pinfunction "6_P$6") (pintype "passive"))
    )
    (net (code "339") (name "STAMP5_SG2_AIN2") (class "Default")
      (node (ref "CON_STAMP5") (pin "P$9") (pinfunction "P$9_P$9") (pintype "bidirectional"))
      (node (ref "U$12") (pin "P$4") (pinfunction "4_P$4") (pintype "passive"))
    )
    (net (code "340") (name "STAMP5_SG2_AIN3") (class "Default")
      (node (ref "CON_STAMP5") (pin "P$8") (pinfunction "P$8_P$8") (pintype "bidirectional"))
      (node (ref "U$12") (pin "P$2") (pinfunction "2_P$2") (pintype "passive"))
    )
    (net (code "341") (name "STAMP5_TEMP_AIN1") (class "Default")
      (node (ref "CON_STAMP5") (pin "P$4") (pinfunction "P$4_P$4") (pintype "bidirectional"))
      (node (ref "R114") (pin "2") (pinfunction "2_2") (pintype "passive"))
      (node (ref "STAMP5_ADC_TEMP") (pin "11") (pinfunction "AIN0/IEXC_11") (pintype "bidirectional"))
    )
    (net (code "342") (name "STAMP5_TEMP_AIN2") (class "Default")
      (node (ref "CON_STAMP5") (pin "P$5") (pinfunction "P$5_P$5") (pintype "bidirectional"))
      (node (ref "R115") (pin "2") (pinfunction "2_2") (pintype "passive"))
      (node (ref "STAMP5_ADC_TEMP") (pin "18") (pinfunction "AIN3/IEXC/GPIO3_18") (pintype "bidirectional"))
    )
    (net (code "343") (name "STAMP5_TEMP_AIN3") (class "Default")
      (node (ref "CON_STAMP5") (pin "P$6") (pinfunction "P$6_P$6") (pintype "bidirectional"))
      (node (ref "R116") (pin "2") (pinfunction "2_2") (pintype "passive"))
      (node (ref "R118") (pin "2") (pinfunction "2_2") (pintype "passive"))
    )
    (net (code "344") (name "STAMP6_CS_SG1") (class "Default")
      (node (ref "SF2_M2S010TQ1") (pin "9") (pinfunction "MSIO72NB7_9") (pintype "bidirectional"))
      (node (ref "STAMP6_ADC_SG1") (pin "24") (pinfunction "~{CS}_24") (pintype "bidirectional"))
    )
    (net (code "345") (name "STAMP6_CS_SG2") (class "Default")
      (node (ref "SF2_M2S010TQ1") (pin "10") (pinfunction "MSIO73NB7_10") (pintype "bidirectional"))
      (node (ref "STAMP6_ADC_SG2") (pin "24") (pinfunction "~{CS}_24") (pintype "bidirectional"))
    )
    (net (code "346") (name "STAMP6_CS_TEMP") (class "Default")
      (node (ref "SF2_M2S010TQ1") (pin "22") (pinfunction "MSIO81PB7_22") (pintype "bidirectional"))
      (node (ref "STAMP6_ADC_TEMP") (pin "24") (pinfunction "~{CS}_24") (pintype "bidirectional"))
    )
    (net (code "347") (name "STAMP6_DRDY_SG1") (class "Default")
      (node (ref "SF2_M2S010TQ1") (pin "4") (pinfunction "MSIO67PB7_4") (pintype "bidirectional"))
      (node (ref "STAMP6_ADC_SG1") (pin "25") (pinfunction "~{DRDY}_25") (pintype "bidirectional"))
    )
    (net (code "348") (name "STAMP6_DRDY_SG2") (class "Default")
      (node (ref "SF2_M2S010TQ1") (pin "7") (pinfunction "MSIO71NB7_7") (pintype "bidirectional"))
      (node (ref "STAMP6_ADC_SG2") (pin "25") (pinfunction "~{DRDY}_25") (pintype "bidirectional"))
    )
    (net (code "349") (name "STAMP6_DRDY_TEMP") (class "Default")
      (node (ref "SF2_M2S010TQ1") (pin "8") (pinfunction "MSIO71PB7_8") (pintype "bidirectional"))
      (node (ref "STAMP6_ADC_TEMP") (pin "25") (pinfunction "~{DRDY}_25") (pintype "bidirectional"))
    )
    (net (code "350") (name "STAMP6_MISO") (class "Default")
      (node (ref "R178") (pin "1") (pinfunction "1_1") (pintype "passive"))
      (node (ref "R184") (pin "1") (pinfunction "1_1") (pintype "passive"))
      (node (ref "R188") (pin "1") (pinfunction "1_1") (pintype "passive"))
      (node (ref "SF2_M2S010TQ1") (pin "3") (pinfunction "MSIO67NB7_3") (pintype "bidirectional"))
    )
    (net (code "351") (name "STAMP6_MOSI") (class "Default")
      (node (ref "R61") (pin "2") (pinfunction "2_2") (pintype "passive"))
      (node (ref "STAMP6_ADC_SG1") (pin "27") (pinfunction "DIN_27") (pintype "bidirectional"))
      (node (ref "STAMP6_ADC_SG2") (pin "27") (pinfunction "DIN_27") (pintype "bidirectional"))
      (node (ref "STAMP6_ADC_TEMP") (pin "27") (pinfunction "DIN_27") (pintype "bidirectional"))
    )
    (net (code "352") (name "STAMP6_SCLK") (class "Default")
      (node (ref "R60") (pin "2") (pinfunction "2_2") (pintype "passive"))
      (node (ref "STAMP6_ADC_SG1") (pin "28") (pinfunction "SCLK_28") (pintype "bidirectional"))
      (node (ref "STAMP6_ADC_SG2") (pin "28") (pinfunction "SCLK_28") (pintype "bidirectional"))
      (node (ref "STAMP6_ADC_TEMP") (pin "28") (pinfunction "SCLK_28") (pintype "bidirectional"))
    )
    (net (code "353") (name "STAMP6_SG1_AIN1") (class "Default")
      (node (ref "CON_STAMP6") (pin "P$1") (pinfunction "P$1_P$1") (pintype "bidirectional"))
      (node (ref "U$19") (pin "P$6") (pinfunction "6_P$6") (pintype "passive"))
    )
    (net (code "354") (name "STAMP6_SG1_AIN2") (class "Default")
      (node (ref "CON_STAMP6") (pin "P$2") (pinfunction "P$2_P$2") (pintype "bidirectional"))
      (node (ref "U$19") (pin "P$4") (pinfunction "4_P$4") (pintype "passive"))
    )
    (net (code "355") (name "STAMP6_SG1_AIN3") (class "Default")
      (node (ref "CON_STAMP6") (pin "P$3") (pinfunction "P$3_P$3") (pintype "bidirectional"))
      (node (ref "U$19") (pin "P$2") (pinfunction "2_P$2") (pintype "passive"))
    )
    (net (code "356") (name "STAMP6_SG2_AIN1") (class "Default")
      (node (ref "CON_STAMP6") (pin "P$10") (pinfunction "P$10_P$10") (pintype "bidirectional"))
      (node (ref "U$20") (pin "P$6") (pinfunction "6_P$6") (pintype "passive"))
    )
    (net (code "357") (name "STAMP6_SG2_AIN2") (class "Default")
      (node (ref "CON_STAMP6") (pin "P$9") (pinfunction "P$9_P$9") (pintype "bidirectional"))
      (node (ref "U$20") (pin "P$4") (pinfunction "4_P$4") (pintype "passive"))
    )
    (net (code "358") (name "STAMP6_SG2_AIN3") (class "Default")
      (node (ref "CON_STAMP6") (pin "P$8") (pinfunction "P$8_P$8") (pintype "bidirectional"))
      (node (ref "U$20") (pin "P$2") (pinfunction "2_P$2") (pintype "passive"))
    )
    (net (code "359") (name "STAMP6_TEMP_AIN1") (class "Default")
      (node (ref "CON_STAMP6") (pin "P$4") (pinfunction "P$4_P$4") (pintype "bidirectional"))
      (node (ref "R190") (pin "2") (pinfunction "2_2") (pintype "passive"))
      (node (ref "STAMP6_ADC_TEMP") (pin "11") (pinfunction "AIN0/IEXC_11") (pintype "bidirectional"))
    )
    (net (code "360") (name "STAMP6_TEMP_AIN2") (class "Default")
      (node (ref "CON_STAMP6") (pin "P$5") (pinfunction "P$5_P$5") (pintype "bidirectional"))
      (node (ref "R191") (pin "2") (pinfunction "2_2") (pintype "passive"))
      (node (ref "STAMP6_ADC_TEMP") (pin "18") (pinfunction "AIN3/IEXC/GPIO3_18") (pintype "bidirectional"))
    )
    (net (code "361") (name "STAMP6_TEMP_AIN3") (class "Default")
      (node (ref "CON_STAMP6") (pin "P$6") (pinfunction "P$6_P$6") (pintype "bidirectional"))
      (node (ref "R192") (pin "2") (pinfunction "2_2") (pintype "passive"))
      (node (ref "R194") (pin "2") (pinfunction "2_2") (pintype "passive"))
    )
    (net (code "362") (name "TM_RX") (class "Default")
      (node (ref "R42") (pin "2") (pinfunction "2_2") (pintype "passive"))
      (node (ref "SF2_M2S010TQ1") (pin "144") (pinfunction "DDRIO63PB0_144") (pintype "bidirectional"))
      (node (ref "U_OPTO_4") (pin "6") (pinfunction "COL2_6") (pintype "input"))
    )
    (net (code "363") (name "TM_TX") (class "Default")
      (node (ref "Q1") (pin "1") (pinfunction "G_1") (pintype "passive"))
      (node (ref "R43") (pin "1") (pinfunction "1_1") (pintype "passive"))
      (node (ref "SF2_M2S010TQ1") (pin "143") (pinfunction "DDRIO59PB0/GB0_143") (pintype "bidirectional"))
    )
    (net (code "364") (name "USB_N") (class "Default")
      (node (ref "USB") (pin "7") (pinfunction "DM_7") (pintype "bidirectional"))
      (node (ref "USB_CONN") (pin "D-") (pinfunction "D-_D-") (pintype "bidirectional"))
    )
    (net (code "365") (name "USB_P") (class "Default")
      (node (ref "USB") (pin "8") (pinfunction "DP_8") (pintype "bidirectional"))
      (node (ref "USB_CONN") (pin "D+") (pinfunction "D+_D+") (pintype "bidirectional"))
    )
    (net (code "366") (name "WP") (class "Default")
      (node (ref "S70FL") (pin "9") (pinfunction "WP#/IO2_9") (pintype "bidirectional"))
      (node (ref "U$3") (pin "P14") (pinfunction "B6_P14") (pintype "bidirectional"))
      (node (ref "WP") (pin "2") (pinfunction "2_2") (pintype "passive"))
    )
    (net (code "367") (name "unconnected-(S70FL-HOLD#{slash}IO3-Pad1)") (class "Default")
      (node (ref "S70FL") (pin "1") (pinfunction "HOLD#/IO3_1") (pintype "bidirectional"))
    )
    (net (code "368") (name "unconnected-(S70FL-RESET#-Pad3)") (class "Default")
      (node (ref "S70FL") (pin "3") (pinfunction "RESET#_3") (pintype "bidirectional"))
    )
    (net (code "369") (name "unconnected-(S70FL-VIO{slash}RFU-Pad14)") (class "Default")
      (node (ref "S70FL") (pin "14") (pinfunction "VIO/RFU_14") (pintype "bidirectional"))
    )
    (net (code "370") (name "unconnected-(SF2_M2S010TQ1C-JTAG_TRSTB{slash}M3_TRSTB-Pad76)") (class "Default")
      (node (ref "SF2_M2S010TQ1") (pin "76") (pinfunction "JTAG_TRSTB/M3_TRSTB_76") (pintype "bidirectional"))
    )
    (net (code "371") (name "unconnected-(SF2_M2S010TQ1E-MSIOD93NB6-Pad29)") (class "Default")
      (node (ref "SF2_M2S010TQ1") (pin "29") (pinfunction "MSIOD93NB6_29") (pintype "bidirectional"))
    )
    (net (code "372") (name "unconnected-(SF2_M2S010TQ1F-MSIO77NB7-Pad15)") (class "Default")
      (node (ref "SF2_M2S010TQ1") (pin "15") (pinfunction "MSIO77NB7_15") (pintype "bidirectional"))
    )
    (net (code "373") (name "unconnected-(SF2_M2S010TQ1F-MSIO77PB7-Pad16)") (class "Default")
      (node (ref "SF2_M2S010TQ1") (pin "16") (pinfunction "MSIO77PB7_16") (pintype "bidirectional"))
    )
    (net (code "374") (name "unconnected-(SF2_M2S010TQ1F-MSIO79NB7-Pad19)") (class "Default")
      (node (ref "SF2_M2S010TQ1") (pin "19") (pinfunction "MSIO79NB7_19") (pintype "bidirectional"))
    )
    (net (code "375") (name "unconnected-(SF2_M2S010TQ1F-MSIO79PB7{slash}GB1-Pad20)") (class "Default")
      (node (ref "SF2_M2S010TQ1") (pin "20") (pinfunction "MSIO79PB7/GB1_20") (pintype "bidirectional"))
    )
    (net (code "376") (name "unconnected-(SF2_M2S010TQ1F-MSIO81NB7-Pad21)") (class "Default")
      (node (ref "SF2_M2S010TQ1") (pin "21") (pinfunction "MSIO81NB7_21") (pintype "bidirectional"))
    )
    (net (code "377") (name "unconnected-(SF2_M2S010TQ1G-VREF0-Pad120)") (class "Default")
      (node (ref "SF2_M2S010TQ1") (pin "120") (pinfunction "VREF0_120") (pintype "bidirectional"))
    )
    (net (code "378") (name "unconnected-(SF2_M2S010TQ1G-XTLOSC_AUX_EXTAL-Pad69)") (class "Default")
      (node (ref "SF2_M2S010TQ1") (pin "69") (pinfunction "XTLOSC_AUX_EXTAL_69") (pintype "bidirectional"))
    )
    (net (code "379") (name "unconnected-(SF2_M2S010TQ1G-XTLOSC_AUX_XTAL-Pad68)") (class "Default")
      (node (ref "SF2_M2S010TQ1") (pin "68") (pinfunction "XTLOSC_AUX_XTAL_68") (pintype "bidirectional"))
    )
    (net (code "380") (name "unconnected-(STAMP1_ADC_SG1-AIN2{slash}IEXC{slash}GPIO2-Pad17)") (class "Default")
      (node (ref "STAMP1_ADC_SG1") (pin "17") (pinfunction "AIN2/IEXC/GPIO2_17") (pintype "bidirectional"))
    )
    (net (code "381") (name "unconnected-(STAMP1_ADC_SG1-AIN3{slash}IEXC{slash}GPIO3-Pad18)") (class "Default")
      (node (ref "STAMP1_ADC_SG1") (pin "18") (pinfunction "AIN3/IEXC/GPIO3_18") (pintype "bidirectional"))
    )
    (net (code "382") (name "unconnected-(STAMP1_ADC_SG1-AIN4{slash}IECG{slash}GPIO4-Pad13)") (class "Default")
      (node (ref "STAMP1_ADC_SG1") (pin "13") (pinfunction "AIN4/IECG/GPIO4_13") (pintype "bidirectional"))
    )
    (net (code "383") (name "unconnected-(STAMP1_ADC_SG1-AIN5{slash}IEXC{slash}GPIO5-Pad14)") (class "Default")
      (node (ref "STAMP1_ADC_SG1") (pin "14") (pinfunction "AIN5/IEXC/GPIO5_14") (pintype "bidirectional"))
    )
    (net (code "384") (name "unconnected-(STAMP1_ADC_SG1-AIN6{slash}IEXC{slash}GPIO6-Pad15)") (class "Default")
      (node (ref "STAMP1_ADC_SG1") (pin "15") (pinfunction "AIN6/IEXC/GPIO6_15") (pintype "bidirectional"))
    )
    (net (code "385") (name "unconnected-(STAMP1_ADC_SG1-AIN7{slash}IEXC{slash}GPIO7-Pad16)") (class "Default")
      (node (ref "STAMP1_ADC_SG1") (pin "16") (pinfunction "AIN7/IEXC/GPIO7_16") (pintype "bidirectional"))
    )
    (net (code "386") (name "unconnected-(STAMP1_ADC_SG1-IEXC1-Pad20)") (class "Default")
      (node (ref "STAMP1_ADC_SG1") (pin "20") (pinfunction "IEXC1_20") (pintype "bidirectional"))
    )
    (net (code "387") (name "unconnected-(STAMP1_ADC_SG1-IEXC2-Pad19)") (class "Default")
      (node (ref "STAMP1_ADC_SG1") (pin "19") (pinfunction "IEXC2_19") (pintype "bidirectional"))
    )
    (net (code "388") (name "unconnected-(STAMP1_ADC_SG1-REFN0{slash}GPIO1-Pad6)") (class "Default")
      (node (ref "STAMP1_ADC_SG1") (pin "6") (pinfunction "REFN0/GPIO1_6") (pintype "bidirectional"))
    )
    (net (code "389") (name "unconnected-(STAMP1_ADC_SG1-REFN1-Pad8)") (class "Default")
      (node (ref "STAMP1_ADC_SG1") (pin "8") (pinfunction "REFN1_8") (pintype "bidirectional"))
    )
    (net (code "390") (name "unconnected-(STAMP1_ADC_SG1-REFP0{slash}GPIO0-Pad5)") (class "Default")
      (node (ref "STAMP1_ADC_SG1") (pin "5") (pinfunction "REFP0/GPIO0_5") (pintype "bidirectional"))
    )
    (net (code "391") (name "unconnected-(STAMP1_ADC_SG1-REFP1-Pad7)") (class "Default")
      (node (ref "STAMP1_ADC_SG1") (pin "7") (pinfunction "REFP1_7") (pintype "bidirectional"))
    )
    (net (code "392") (name "unconnected-(STAMP1_ADC_SG2-AIN2{slash}IEXC{slash}GPIO2-Pad17)") (class "Default")
      (node (ref "STAMP1_ADC_SG2") (pin "17") (pinfunction "AIN2/IEXC/GPIO2_17") (pintype "bidirectional"))
    )
    (net (code "393") (name "unconnected-(STAMP1_ADC_SG2-AIN3{slash}IEXC{slash}GPIO3-Pad18)") (class "Default")
      (node (ref "STAMP1_ADC_SG2") (pin "18") (pinfunction "AIN3/IEXC/GPIO3_18") (pintype "bidirectional"))
    )
    (net (code "394") (name "unconnected-(STAMP1_ADC_SG2-AIN4{slash}IECG{slash}GPIO4-Pad13)") (class "Default")
      (node (ref "STAMP1_ADC_SG2") (pin "13") (pinfunction "AIN4/IECG/GPIO4_13") (pintype "bidirectional"))
    )
    (net (code "395") (name "unconnected-(STAMP1_ADC_SG2-AIN5{slash}IEXC{slash}GPIO5-Pad14)") (class "Default")
      (node (ref "STAMP1_ADC_SG2") (pin "14") (pinfunction "AIN5/IEXC/GPIO5_14") (pintype "bidirectional"))
    )
    (net (code "396") (name "unconnected-(STAMP1_ADC_SG2-AIN6{slash}IEXC{slash}GPIO6-Pad15)") (class "Default")
      (node (ref "STAMP1_ADC_SG2") (pin "15") (pinfunction "AIN6/IEXC/GPIO6_15") (pintype "bidirectional"))
    )
    (net (code "397") (name "unconnected-(STAMP1_ADC_SG2-AIN7{slash}IEXC{slash}GPIO7-Pad16)") (class "Default")
      (node (ref "STAMP1_ADC_SG2") (pin "16") (pinfunction "AIN7/IEXC/GPIO7_16") (pintype "bidirectional"))
    )
    (net (code "398") (name "unconnected-(STAMP1_ADC_SG2-IEXC1-Pad20)") (class "Default")
      (node (ref "STAMP1_ADC_SG2") (pin "20") (pinfunction "IEXC1_20") (pintype "bidirectional"))
    )
    (net (code "399") (name "unconnected-(STAMP1_ADC_SG2-IEXC2-Pad19)") (class "Default")
      (node (ref "STAMP1_ADC_SG2") (pin "19") (pinfunction "IEXC2_19") (pintype "bidirectional"))
    )
    (net (code "400") (name "unconnected-(STAMP1_ADC_SG2-REFN0{slash}GPIO1-Pad6)") (class "Default")
      (node (ref "STAMP1_ADC_SG2") (pin "6") (pinfunction "REFN0/GPIO1_6") (pintype "bidirectional"))
    )
    (net (code "401") (name "unconnected-(STAMP1_ADC_SG2-REFN1-Pad8)") (class "Default")
      (node (ref "STAMP1_ADC_SG2") (pin "8") (pinfunction "REFN1_8") (pintype "bidirectional"))
    )
    (net (code "402") (name "unconnected-(STAMP1_ADC_SG2-REFP0{slash}GPIO0-Pad5)") (class "Default")
      (node (ref "STAMP1_ADC_SG2") (pin "5") (pinfunction "REFP0/GPIO0_5") (pintype "bidirectional"))
    )
    (net (code "403") (name "unconnected-(STAMP1_ADC_SG2-REFP1-Pad7)") (class "Default")
      (node (ref "STAMP1_ADC_SG2") (pin "7") (pinfunction "REFP1_7") (pintype "bidirectional"))
    )
    (net (code "404") (name "unconnected-(STAMP1_ADC_TEMP-AIN4{slash}IECG{slash}GPIO4-Pad13)") (class "Default")
      (node (ref "STAMP1_ADC_TEMP") (pin "13") (pinfunction "AIN4/IECG/GPIO4_13") (pintype "bidirectional"))
    )
    (net (code "405") (name "unconnected-(STAMP1_ADC_TEMP-AIN5{slash}IEXC{slash}GPIO5-Pad14)") (class "Default")
      (node (ref "STAMP1_ADC_TEMP") (pin "14") (pinfunction "AIN5/IEXC/GPIO5_14") (pintype "bidirectional"))
    )
    (net (code "406") (name "unconnected-(STAMP1_ADC_TEMP-AIN6{slash}IEXC{slash}GPIO6-Pad15)") (class "Default")
      (node (ref "STAMP1_ADC_TEMP") (pin "15") (pinfunction "AIN6/IEXC/GPIO6_15") (pintype "bidirectional"))
    )
    (net (code "407") (name "unconnected-(STAMP1_ADC_TEMP-AIN7{slash}IEXC{slash}GPIO7-Pad16)") (class "Default")
      (node (ref "STAMP1_ADC_TEMP") (pin "16") (pinfunction "AIN7/IEXC/GPIO7_16") (pintype "bidirectional"))
    )
    (net (code "408") (name "unconnected-(STAMP1_ADC_TEMP-IEXC1-Pad20)") (class "Default")
      (node (ref "STAMP1_ADC_TEMP") (pin "20") (pinfunction "IEXC1_20") (pintype "bidirectional"))
    )
    (net (code "409") (name "unconnected-(STAMP1_ADC_TEMP-IEXC2-Pad19)") (class "Default")
      (node (ref "STAMP1_ADC_TEMP") (pin "19") (pinfunction "IEXC2_19") (pintype "bidirectional"))
    )
    (net (code "410") (name "unconnected-(STAMP1_ADC_TEMP-REFN1-Pad8)") (class "Default")
      (node (ref "STAMP1_ADC_TEMP") (pin "8") (pinfunction "REFN1_8") (pintype "bidirectional"))
    )
    (net (code "411") (name "unconnected-(STAMP1_ADC_TEMP-REFP1-Pad7)") (class "Default")
      (node (ref "STAMP1_ADC_TEMP") (pin "7") (pinfunction "REFP1_7") (pintype "bidirectional"))
    )
    (net (code "412") (name "unconnected-(STAMP2_ADC_SG1-AIN2{slash}IEXC{slash}GPIO2-Pad17)") (class "Default")
      (node (ref "STAMP2_ADC_SG1") (pin "17") (pinfunction "AIN2/IEXC/GPIO2_17") (pintype "bidirectional"))
    )
    (net (code "413") (name "unconnected-(STAMP2_ADC_SG1-AIN3{slash}IEXC{slash}GPIO3-Pad18)") (class "Default")
      (node (ref "STAMP2_ADC_SG1") (pin "18") (pinfunction "AIN3/IEXC/GPIO3_18") (pintype "bidirectional"))
    )
    (net (code "414") (name "unconnected-(STAMP2_ADC_SG1-AIN4{slash}IECG{slash}GPIO4-Pad13)") (class "Default")
      (node (ref "STAMP2_ADC_SG1") (pin "13") (pinfunction "AIN4/IECG/GPIO4_13") (pintype "bidirectional"))
    )
    (net (code "415") (name "unconnected-(STAMP2_ADC_SG1-AIN5{slash}IEXC{slash}GPIO5-Pad14)") (class "Default")
      (node (ref "STAMP2_ADC_SG1") (pin "14") (pinfunction "AIN5/IEXC/GPIO5_14") (pintype "bidirectional"))
    )
    (net (code "416") (name "unconnected-(STAMP2_ADC_SG1-AIN6{slash}IEXC{slash}GPIO6-Pad15)") (class "Default")
      (node (ref "STAMP2_ADC_SG1") (pin "15") (pinfunction "AIN6/IEXC/GPIO6_15") (pintype "bidirectional"))
    )
    (net (code "417") (name "unconnected-(STAMP2_ADC_SG1-AIN7{slash}IEXC{slash}GPIO7-Pad16)") (class "Default")
      (node (ref "STAMP2_ADC_SG1") (pin "16") (pinfunction "AIN7/IEXC/GPIO7_16") (pintype "bidirectional"))
    )
    (net (code "418") (name "unconnected-(STAMP2_ADC_SG1-IEXC1-Pad20)") (class "Default")
      (node (ref "STAMP2_ADC_SG1") (pin "20") (pinfunction "IEXC1_20") (pintype "bidirectional"))
    )
    (net (code "419") (name "unconnected-(STAMP2_ADC_SG1-IEXC2-Pad19)") (class "Default")
      (node (ref "STAMP2_ADC_SG1") (pin "19") (pinfunction "IEXC2_19") (pintype "bidirectional"))
    )
    (net (code "420") (name "unconnected-(STAMP2_ADC_SG1-REFN0{slash}GPIO1-Pad6)") (class "Default")
      (node (ref "STAMP2_ADC_SG1") (pin "6") (pinfunction "REFN0/GPIO1_6") (pintype "bidirectional"))
    )
    (net (code "421") (name "unconnected-(STAMP2_ADC_SG1-REFN1-Pad8)") (class "Default")
      (node (ref "STAMP2_ADC_SG1") (pin "8") (pinfunction "REFN1_8") (pintype "bidirectional"))
    )
    (net (code "422") (name "unconnected-(STAMP2_ADC_SG1-REFP0{slash}GPIO0-Pad5)") (class "Default")
      (node (ref "STAMP2_ADC_SG1") (pin "5") (pinfunction "REFP0/GPIO0_5") (pintype "bidirectional"))
    )
    (net (code "423") (name "unconnected-(STAMP2_ADC_SG1-REFP1-Pad7)") (class "Default")
      (node (ref "STAMP2_ADC_SG1") (pin "7") (pinfunction "REFP1_7") (pintype "bidirectional"))
    )
    (net (code "424") (name "unconnected-(STAMP2_ADC_SG2-AIN2{slash}IEXC{slash}GPIO2-Pad17)") (class "Default")
      (node (ref "STAMP2_ADC_SG2") (pin "17") (pinfunction "AIN2/IEXC/GPIO2_17") (pintype "bidirectional"))
    )
    (net (code "425") (name "unconnected-(STAMP2_ADC_SG2-AIN3{slash}IEXC{slash}GPIO3-Pad18)") (class "Default")
      (node (ref "STAMP2_ADC_SG2") (pin "18") (pinfunction "AIN3/IEXC/GPIO3_18") (pintype "bidirectional"))
    )
    (net (code "426") (name "unconnected-(STAMP2_ADC_SG2-AIN4{slash}IECG{slash}GPIO4-Pad13)") (class "Default")
      (node (ref "STAMP2_ADC_SG2") (pin "13") (pinfunction "AIN4/IECG/GPIO4_13") (pintype "bidirectional"))
    )
    (net (code "427") (name "unconnected-(STAMP2_ADC_SG2-AIN5{slash}IEXC{slash}GPIO5-Pad14)") (class "Default")
      (node (ref "STAMP2_ADC_SG2") (pin "14") (pinfunction "AIN5/IEXC/GPIO5_14") (pintype "bidirectional"))
    )
    (net (code "428") (name "unconnected-(STAMP2_ADC_SG2-AIN6{slash}IEXC{slash}GPIO6-Pad15)") (class "Default")
      (node (ref "STAMP2_ADC_SG2") (pin "15") (pinfunction "AIN6/IEXC/GPIO6_15") (pintype "bidirectional"))
    )
    (net (code "429") (name "unconnected-(STAMP2_ADC_SG2-AIN7{slash}IEXC{slash}GPIO7-Pad16)") (class "Default")
      (node (ref "STAMP2_ADC_SG2") (pin "16") (pinfunction "AIN7/IEXC/GPIO7_16") (pintype "bidirectional"))
    )
    (net (code "430") (name "unconnected-(STAMP2_ADC_SG2-IEXC1-Pad20)") (class "Default")
      (node (ref "STAMP2_ADC_SG2") (pin "20") (pinfunction "IEXC1_20") (pintype "bidirectional"))
    )
    (net (code "431") (name "unconnected-(STAMP2_ADC_SG2-IEXC2-Pad19)") (class "Default")
      (node (ref "STAMP2_ADC_SG2") (pin "19") (pinfunction "IEXC2_19") (pintype "bidirectional"))
    )
    (net (code "432") (name "unconnected-(STAMP2_ADC_SG2-REFN0{slash}GPIO1-Pad6)") (class "Default")
      (node (ref "STAMP2_ADC_SG2") (pin "6") (pinfunction "REFN0/GPIO1_6") (pintype "bidirectional"))
    )
    (net (code "433") (name "unconnected-(STAMP2_ADC_SG2-REFN1-Pad8)") (class "Default")
      (node (ref "STAMP2_ADC_SG2") (pin "8") (pinfunction "REFN1_8") (pintype "bidirectional"))
    )
    (net (code "434") (name "unconnected-(STAMP2_ADC_SG2-REFP0{slash}GPIO0-Pad5)") (class "Default")
      (node (ref "STAMP2_ADC_SG2") (pin "5") (pinfunction "REFP0/GPIO0_5") (pintype "bidirectional"))
    )
    (net (code "435") (name "unconnected-(STAMP2_ADC_SG2-REFP1-Pad7)") (class "Default")
      (node (ref "STAMP2_ADC_SG2") (pin "7") (pinfunction "REFP1_7") (pintype "bidirectional"))
    )
    (net (code "436") (name "unconnected-(STAMP2_ADC_TEMP-AIN4{slash}IECG{slash}GPIO4-Pad13)") (class "Default")
      (node (ref "STAMP2_ADC_TEMP") (pin "13") (pinfunction "AIN4/IECG/GPIO4_13") (pintype "bidirectional"))
    )
    (net (code "437") (name "unconnected-(STAMP2_ADC_TEMP-AIN5{slash}IEXC{slash}GPIO5-Pad14)") (class "Default")
      (node (ref "STAMP2_ADC_TEMP") (pin "14") (pinfunction "AIN5/IEXC/GPIO5_14") (pintype "bidirectional"))
    )
    (net (code "438") (name "unconnected-(STAMP2_ADC_TEMP-AIN6{slash}IEXC{slash}GPIO6-Pad15)") (class "Default")
      (node (ref "STAMP2_ADC_TEMP") (pin "15") (pinfunction "AIN6/IEXC/GPIO6_15") (pintype "bidirectional"))
    )
    (net (code "439") (name "unconnected-(STAMP2_ADC_TEMP-AIN7{slash}IEXC{slash}GPIO7-Pad16)") (class "Default")
      (node (ref "STAMP2_ADC_TEMP") (pin "16") (pinfunction "AIN7/IEXC/GPIO7_16") (pintype "bidirectional"))
    )
    (net (code "440") (name "unconnected-(STAMP2_ADC_TEMP-IEXC1-Pad20)") (class "Default")
      (node (ref "STAMP2_ADC_TEMP") (pin "20") (pinfunction "IEXC1_20") (pintype "bidirectional"))
    )
    (net (code "441") (name "unconnected-(STAMP2_ADC_TEMP-IEXC2-Pad19)") (class "Default")
      (node (ref "STAMP2_ADC_TEMP") (pin "19") (pinfunction "IEXC2_19") (pintype "bidirectional"))
    )
    (net (code "442") (name "unconnected-(STAMP2_ADC_TEMP-REFN1-Pad8)") (class "Default")
      (node (ref "STAMP2_ADC_TEMP") (pin "8") (pinfunction "REFN1_8") (pintype "bidirectional"))
    )
    (net (code "443") (name "unconnected-(STAMP2_ADC_TEMP-REFP1-Pad7)") (class "Default")
      (node (ref "STAMP2_ADC_TEMP") (pin "7") (pinfunction "REFP1_7") (pintype "bidirectional"))
    )
    (net (code "444") (name "unconnected-(STAMP3_ADC_SG1-AIN2{slash}IEXC{slash}GPIO2-Pad17)") (class "Default")
      (node (ref "STAMP3_ADC_SG1") (pin "17") (pinfunction "AIN2/IEXC/GPIO2_17") (pintype "bidirectional"))
    )
    (net (code "445") (name "unconnected-(STAMP3_ADC_SG1-AIN3{slash}IEXC{slash}GPIO3-Pad18)") (class "Default")
      (node (ref "STAMP3_ADC_SG1") (pin "18") (pinfunction "AIN3/IEXC/GPIO3_18") (pintype "bidirectional"))
    )
    (net (code "446") (name "unconnected-(STAMP3_ADC_SG1-AIN4{slash}IECG{slash}GPIO4-Pad13)") (class "Default")
      (node (ref "STAMP3_ADC_SG1") (pin "13") (pinfunction "AIN4/IECG/GPIO4_13") (pintype "bidirectional"))
    )
    (net (code "447") (name "unconnected-(STAMP3_ADC_SG1-AIN5{slash}IEXC{slash}GPIO5-Pad14)") (class "Default")
      (node (ref "STAMP3_ADC_SG1") (pin "14") (pinfunction "AIN5/IEXC/GPIO5_14") (pintype "bidirectional"))
    )
    (net (code "448") (name "unconnected-(STAMP3_ADC_SG1-AIN6{slash}IEXC{slash}GPIO6-Pad15)") (class "Default")
      (node (ref "STAMP3_ADC_SG1") (pin "15") (pinfunction "AIN6/IEXC/GPIO6_15") (pintype "bidirectional"))
    )
    (net (code "449") (name "unconnected-(STAMP3_ADC_SG1-AIN7{slash}IEXC{slash}GPIO7-Pad16)") (class "Default")
      (node (ref "STAMP3_ADC_SG1") (pin "16") (pinfunction "AIN7/IEXC/GPIO7_16") (pintype "bidirectional"))
    )
    (net (code "450") (name "unconnected-(STAMP3_ADC_SG1-IEXC1-Pad20)") (class "Default")
      (node (ref "STAMP3_ADC_SG1") (pin "20") (pinfunction "IEXC1_20") (pintype "bidirectional"))
    )
    (net (code "451") (name "unconnected-(STAMP3_ADC_SG1-IEXC2-Pad19)") (class "Default")
      (node (ref "STAMP3_ADC_SG1") (pin "19") (pinfunction "IEXC2_19") (pintype "bidirectional"))
    )
    (net (code "452") (name "unconnected-(STAMP3_ADC_SG1-REFN0{slash}GPIO1-Pad6)") (class "Default")
      (node (ref "STAMP3_ADC_SG1") (pin "6") (pinfunction "REFN0/GPIO1_6") (pintype "bidirectional"))
    )
    (net (code "453") (name "unconnected-(STAMP3_ADC_SG1-REFN1-Pad8)") (class "Default")
      (node (ref "STAMP3_ADC_SG1") (pin "8") (pinfunction "REFN1_8") (pintype "bidirectional"))
    )
    (net (code "454") (name "unconnected-(STAMP3_ADC_SG1-REFP0{slash}GPIO0-Pad5)") (class "Default")
      (node (ref "STAMP3_ADC_SG1") (pin "5") (pinfunction "REFP0/GPIO0_5") (pintype "bidirectional"))
    )
    (net (code "455") (name "unconnected-(STAMP3_ADC_SG1-REFP1-Pad7)") (class "Default")
      (node (ref "STAMP3_ADC_SG1") (pin "7") (pinfunction "REFP1_7") (pintype "bidirectional"))
    )
    (net (code "456") (name "unconnected-(STAMP3_ADC_SG2-AIN2{slash}IEXC{slash}GPIO2-Pad17)") (class "Default")
      (node (ref "STAMP3_ADC_SG2") (pin "17") (pinfunction "AIN2/IEXC/GPIO2_17") (pintype "bidirectional"))
    )
    (net (code "457") (name "unconnected-(STAMP3_ADC_SG2-AIN3{slash}IEXC{slash}GPIO3-Pad18)") (class "Default")
      (node (ref "STAMP3_ADC_SG2") (pin "18") (pinfunction "AIN3/IEXC/GPIO3_18") (pintype "bidirectional"))
    )
    (net (code "458") (name "unconnected-(STAMP3_ADC_SG2-AIN4{slash}IECG{slash}GPIO4-Pad13)") (class "Default")
      (node (ref "STAMP3_ADC_SG2") (pin "13") (pinfunction "AIN4/IECG/GPIO4_13") (pintype "bidirectional"))
    )
    (net (code "459") (name "unconnected-(STAMP3_ADC_SG2-AIN5{slash}IEXC{slash}GPIO5-Pad14)") (class "Default")
      (node (ref "STAMP3_ADC_SG2") (pin "14") (pinfunction "AIN5/IEXC/GPIO5_14") (pintype "bidirectional"))
    )
    (net (code "460") (name "unconnected-(STAMP3_ADC_SG2-AIN6{slash}IEXC{slash}GPIO6-Pad15)") (class "Default")
      (node (ref "STAMP3_ADC_SG2") (pin "15") (pinfunction "AIN6/IEXC/GPIO6_15") (pintype "bidirectional"))
    )
    (net (code "461") (name "unconnected-(STAMP3_ADC_SG2-AIN7{slash}IEXC{slash}GPIO7-Pad16)") (class "Default")
      (node (ref "STAMP3_ADC_SG2") (pin "16") (pinfunction "AIN7/IEXC/GPIO7_16") (pintype "bidirectional"))
    )
    (net (code "462") (name "unconnected-(STAMP3_ADC_SG2-IEXC1-Pad20)") (class "Default")
      (node (ref "STAMP3_ADC_SG2") (pin "20") (pinfunction "IEXC1_20") (pintype "bidirectional"))
    )
    (net (code "463") (name "unconnected-(STAMP3_ADC_SG2-IEXC2-Pad19)") (class "Default")
      (node (ref "STAMP3_ADC_SG2") (pin "19") (pinfunction "IEXC2_19") (pintype "bidirectional"))
    )
    (net (code "464") (name "unconnected-(STAMP3_ADC_SG2-REFN0{slash}GPIO1-Pad6)") (class "Default")
      (node (ref "STAMP3_ADC_SG2") (pin "6") (pinfunction "REFN0/GPIO1_6") (pintype "bidirectional"))
    )
    (net (code "465") (name "unconnected-(STAMP3_ADC_SG2-REFN1-Pad8)") (class "Default")
      (node (ref "STAMP3_ADC_SG2") (pin "8") (pinfunction "REFN1_8") (pintype "bidirectional"))
    )
    (net (code "466") (name "unconnected-(STAMP3_ADC_SG2-REFP0{slash}GPIO0-Pad5)") (class "Default")
      (node (ref "STAMP3_ADC_SG2") (pin "5") (pinfunction "REFP0/GPIO0_5") (pintype "bidirectional"))
    )
    (net (code "467") (name "unconnected-(STAMP3_ADC_SG2-REFP1-Pad7)") (class "Default")
      (node (ref "STAMP3_ADC_SG2") (pin "7") (pinfunction "REFP1_7") (pintype "bidirectional"))
    )
    (net (code "468") (name "unconnected-(STAMP3_ADC_TEMP-AIN4{slash}IECG{slash}GPIO4-Pad13)") (class "Default")
      (node (ref "STAMP3_ADC_TEMP") (pin "13") (pinfunction "AIN4/IECG/GPIO4_13") (pintype "bidirectional"))
    )
    (net (code "469") (name "unconnected-(STAMP3_ADC_TEMP-AIN5{slash}IEXC{slash}GPIO5-Pad14)") (class "Default")
      (node (ref "STAMP3_ADC_TEMP") (pin "14") (pinfunction "AIN5/IEXC/GPIO5_14") (pintype "bidirectional"))
    )
    (net (code "470") (name "unconnected-(STAMP3_ADC_TEMP-AIN6{slash}IEXC{slash}GPIO6-Pad15)") (class "Default")
      (node (ref "STAMP3_ADC_TEMP") (pin "15") (pinfunction "AIN6/IEXC/GPIO6_15") (pintype "bidirectional"))
    )
    (net (code "471") (name "unconnected-(STAMP3_ADC_TEMP-AIN7{slash}IEXC{slash}GPIO7-Pad16)") (class "Default")
      (node (ref "STAMP3_ADC_TEMP") (pin "16") (pinfunction "AIN7/IEXC/GPIO7_16") (pintype "bidirectional"))
    )
    (net (code "472") (name "unconnected-(STAMP3_ADC_TEMP-IEXC1-Pad20)") (class "Default")
      (node (ref "STAMP3_ADC_TEMP") (pin "20") (pinfunction "IEXC1_20") (pintype "bidirectional"))
    )
    (net (code "473") (name "unconnected-(STAMP3_ADC_TEMP-IEXC2-Pad19)") (class "Default")
      (node (ref "STAMP3_ADC_TEMP") (pin "19") (pinfunction "IEXC2_19") (pintype "bidirectional"))
    )
    (net (code "474") (name "unconnected-(STAMP3_ADC_TEMP-REFN1-Pad8)") (class "Default")
      (node (ref "STAMP3_ADC_TEMP") (pin "8") (pinfunction "REFN1_8") (pintype "bidirectional"))
    )
    (net (code "475") (name "unconnected-(STAMP3_ADC_TEMP-REFP1-Pad7)") (class "Default")
      (node (ref "STAMP3_ADC_TEMP") (pin "7") (pinfunction "REFP1_7") (pintype "bidirectional"))
    )
    (net (code "476") (name "unconnected-(STAMP4_ADC_SG1-AIN2{slash}IEXC{slash}GPIO2-Pad17)") (class "Default")
      (node (ref "STAMP4_ADC_SG1") (pin "17") (pinfunction "AIN2/IEXC/GPIO2_17") (pintype "bidirectional"))
    )
    (net (code "477") (name "unconnected-(STAMP4_ADC_SG1-AIN3{slash}IEXC{slash}GPIO3-Pad18)") (class "Default")
      (node (ref "STAMP4_ADC_SG1") (pin "18") (pinfunction "AIN3/IEXC/GPIO3_18") (pintype "bidirectional"))
    )
    (net (code "478") (name "unconnected-(STAMP4_ADC_SG1-AIN4{slash}IECG{slash}GPIO4-Pad13)") (class "Default")
      (node (ref "STAMP4_ADC_SG1") (pin "13") (pinfunction "AIN4/IECG/GPIO4_13") (pintype "bidirectional"))
    )
    (net (code "479") (name "unconnected-(STAMP4_ADC_SG1-AIN5{slash}IEXC{slash}GPIO5-Pad14)") (class "Default")
      (node (ref "STAMP4_ADC_SG1") (pin "14") (pinfunction "AIN5/IEXC/GPIO5_14") (pintype "bidirectional"))
    )
    (net (code "480") (name "unconnected-(STAMP4_ADC_SG1-AIN6{slash}IEXC{slash}GPIO6-Pad15)") (class "Default")
      (node (ref "STAMP4_ADC_SG1") (pin "15") (pinfunction "AIN6/IEXC/GPIO6_15") (pintype "bidirectional"))
    )
    (net (code "481") (name "unconnected-(STAMP4_ADC_SG1-AIN7{slash}IEXC{slash}GPIO7-Pad16)") (class "Default")
      (node (ref "STAMP4_ADC_SG1") (pin "16") (pinfunction "AIN7/IEXC/GPIO7_16") (pintype "bidirectional"))
    )
    (net (code "482") (name "unconnected-(STAMP4_ADC_SG1-IEXC1-Pad20)") (class "Default")
      (node (ref "STAMP4_ADC_SG1") (pin "20") (pinfunction "IEXC1_20") (pintype "bidirectional"))
    )
    (net (code "483") (name "unconnected-(STAMP4_ADC_SG1-IEXC2-Pad19)") (class "Default")
      (node (ref "STAMP4_ADC_SG1") (pin "19") (pinfunction "IEXC2_19") (pintype "bidirectional"))
    )
    (net (code "484") (name "unconnected-(STAMP4_ADC_SG1-REFN0{slash}GPIO1-Pad6)") (class "Default")
      (node (ref "STAMP4_ADC_SG1") (pin "6") (pinfunction "REFN0/GPIO1_6") (pintype "bidirectional"))
    )
    (net (code "485") (name "unconnected-(STAMP4_ADC_SG1-REFN1-Pad8)") (class "Default")
      (node (ref "STAMP4_ADC_SG1") (pin "8") (pinfunction "REFN1_8") (pintype "bidirectional"))
    )
    (net (code "486") (name "unconnected-(STAMP4_ADC_SG1-REFP0{slash}GPIO0-Pad5)") (class "Default")
      (node (ref "STAMP4_ADC_SG1") (pin "5") (pinfunction "REFP0/GPIO0_5") (pintype "bidirectional"))
    )
    (net (code "487") (name "unconnected-(STAMP4_ADC_SG1-REFP1-Pad7)") (class "Default")
      (node (ref "STAMP4_ADC_SG1") (pin "7") (pinfunction "REFP1_7") (pintype "bidirectional"))
    )
    (net (code "488") (name "unconnected-(STAMP4_ADC_SG2-AIN2{slash}IEXC{slash}GPIO2-Pad17)") (class "Default")
      (node (ref "STAMP4_ADC_SG2") (pin "17") (pinfunction "AIN2/IEXC/GPIO2_17") (pintype "bidirectional"))
    )
    (net (code "489") (name "unconnected-(STAMP4_ADC_SG2-AIN3{slash}IEXC{slash}GPIO3-Pad18)") (class "Default")
      (node (ref "STAMP4_ADC_SG2") (pin "18") (pinfunction "AIN3/IEXC/GPIO3_18") (pintype "bidirectional"))
    )
    (net (code "490") (name "unconnected-(STAMP4_ADC_SG2-AIN4{slash}IECG{slash}GPIO4-Pad13)") (class "Default")
      (node (ref "STAMP4_ADC_SG2") (pin "13") (pinfunction "AIN4/IECG/GPIO4_13") (pintype "bidirectional"))
    )
    (net (code "491") (name "unconnected-(STAMP4_ADC_SG2-AIN5{slash}IEXC{slash}GPIO5-Pad14)") (class "Default")
      (node (ref "STAMP4_ADC_SG2") (pin "14") (pinfunction "AIN5/IEXC/GPIO5_14") (pintype "bidirectional"))
    )
    (net (code "492") (name "unconnected-(STAMP4_ADC_SG2-AIN6{slash}IEXC{slash}GPIO6-Pad15)") (class "Default")
      (node (ref "STAMP4_ADC_SG2") (pin "15") (pinfunction "AIN6/IEXC/GPIO6_15") (pintype "bidirectional"))
    )
    (net (code "493") (name "unconnected-(STAMP4_ADC_SG2-AIN7{slash}IEXC{slash}GPIO7-Pad16)") (class "Default")
      (node (ref "STAMP4_ADC_SG2") (pin "16") (pinfunction "AIN7/IEXC/GPIO7_16") (pintype "bidirectional"))
    )
    (net (code "494") (name "unconnected-(STAMP4_ADC_SG2-IEXC1-Pad20)") (class "Default")
      (node (ref "STAMP4_ADC_SG2") (pin "20") (pinfunction "IEXC1_20") (pintype "bidirectional"))
    )
    (net (code "495") (name "unconnected-(STAMP4_ADC_SG2-IEXC2-Pad19)") (class "Default")
      (node (ref "STAMP4_ADC_SG2") (pin "19") (pinfunction "IEXC2_19") (pintype "bidirectional"))
    )
    (net (code "496") (name "unconnected-(STAMP4_ADC_SG2-REFN0{slash}GPIO1-Pad6)") (class "Default")
      (node (ref "STAMP4_ADC_SG2") (pin "6") (pinfunction "REFN0/GPIO1_6") (pintype "bidirectional"))
    )
    (net (code "497") (name "unconnected-(STAMP4_ADC_SG2-REFN1-Pad8)") (class "Default")
      (node (ref "STAMP4_ADC_SG2") (pin "8") (pinfunction "REFN1_8") (pintype "bidirectional"))
    )
    (net (code "498") (name "unconnected-(STAMP4_ADC_SG2-REFP0{slash}GPIO0-Pad5)") (class "Default")
      (node (ref "STAMP4_ADC_SG2") (pin "5") (pinfunction "REFP0/GPIO0_5") (pintype "bidirectional"))
    )
    (net (code "499") (name "unconnected-(STAMP4_ADC_SG2-REFP1-Pad7)") (class "Default")
      (node (ref "STAMP4_ADC_SG2") (pin "7") (pinfunction "REFP1_7") (pintype "bidirectional"))
    )
    (net (code "500") (name "unconnected-(STAMP4_ADC_TEMP-AIN4{slash}IECG{slash}GPIO4-Pad13)") (class "Default")
      (node (ref "STAMP4_ADC_TEMP") (pin "13") (pinfunction "AIN4/IECG/GPIO4_13") (pintype "bidirectional"))
    )
    (net (code "501") (name "unconnected-(STAMP4_ADC_TEMP-AIN5{slash}IEXC{slash}GPIO5-Pad14)") (class "Default")
      (node (ref "STAMP4_ADC_TEMP") (pin "14") (pinfunction "AIN5/IEXC/GPIO5_14") (pintype "bidirectional"))
    )
    (net (code "502") (name "unconnected-(STAMP4_ADC_TEMP-AIN6{slash}IEXC{slash}GPIO6-Pad15)") (class "Default")
      (node (ref "STAMP4_ADC_TEMP") (pin "15") (pinfunction "AIN6/IEXC/GPIO6_15") (pintype "bidirectional"))
    )
    (net (code "503") (name "unconnected-(STAMP4_ADC_TEMP-AIN7{slash}IEXC{slash}GPIO7-Pad16)") (class "Default")
      (node (ref "STAMP4_ADC_TEMP") (pin "16") (pinfunction "AIN7/IEXC/GPIO7_16") (pintype "bidirectional"))
    )
    (net (code "504") (name "unconnected-(STAMP4_ADC_TEMP-IEXC1-Pad20)") (class "Default")
      (node (ref "STAMP4_ADC_TEMP") (pin "20") (pinfunction "IEXC1_20") (pintype "bidirectional"))
    )
    (net (code "505") (name "unconnected-(STAMP4_ADC_TEMP-IEXC2-Pad19)") (class "Default")
      (node (ref "STAMP4_ADC_TEMP") (pin "19") (pinfunction "IEXC2_19") (pintype "bidirectional"))
    )
    (net (code "506") (name "unconnected-(STAMP4_ADC_TEMP-REFN1-Pad8)") (class "Default")
      (node (ref "STAMP4_ADC_TEMP") (pin "8") (pinfunction "REFN1_8") (pintype "bidirectional"))
    )
    (net (code "507") (name "unconnected-(STAMP4_ADC_TEMP-REFP1-Pad7)") (class "Default")
      (node (ref "STAMP4_ADC_TEMP") (pin "7") (pinfunction "REFP1_7") (pintype "bidirectional"))
    )
    (net (code "508") (name "unconnected-(STAMP5_ADC_SG1-AIN2{slash}IEXC{slash}GPIO2-Pad17)") (class "Default")
      (node (ref "STAMP5_ADC_SG1") (pin "17") (pinfunction "AIN2/IEXC/GPIO2_17") (pintype "bidirectional"))
    )
    (net (code "509") (name "unconnected-(STAMP5_ADC_SG1-AIN3{slash}IEXC{slash}GPIO3-Pad18)") (class "Default")
      (node (ref "STAMP5_ADC_SG1") (pin "18") (pinfunction "AIN3/IEXC/GPIO3_18") (pintype "bidirectional"))
    )
    (net (code "510") (name "unconnected-(STAMP5_ADC_SG1-AIN4{slash}IECG{slash}GPIO4-Pad13)") (class "Default")
      (node (ref "STAMP5_ADC_SG1") (pin "13") (pinfunction "AIN4/IECG/GPIO4_13") (pintype "bidirectional"))
    )
    (net (code "511") (name "unconnected-(STAMP5_ADC_SG1-AIN5{slash}IEXC{slash}GPIO5-Pad14)") (class "Default")
      (node (ref "STAMP5_ADC_SG1") (pin "14") (pinfunction "AIN5/IEXC/GPIO5_14") (pintype "bidirectional"))
    )
    (net (code "512") (name "unconnected-(STAMP5_ADC_SG1-AIN6{slash}IEXC{slash}GPIO6-Pad15)") (class "Default")
      (node (ref "STAMP5_ADC_SG1") (pin "15") (pinfunction "AIN6/IEXC/GPIO6_15") (pintype "bidirectional"))
    )
    (net (code "513") (name "unconnected-(STAMP5_ADC_SG1-AIN7{slash}IEXC{slash}GPIO7-Pad16)") (class "Default")
      (node (ref "STAMP5_ADC_SG1") (pin "16") (pinfunction "AIN7/IEXC/GPIO7_16") (pintype "bidirectional"))
    )
    (net (code "514") (name "unconnected-(STAMP5_ADC_SG1-IEXC1-Pad20)") (class "Default")
      (node (ref "STAMP5_ADC_SG1") (pin "20") (pinfunction "IEXC1_20") (pintype "bidirectional"))
    )
    (net (code "515") (name "unconnected-(STAMP5_ADC_SG1-IEXC2-Pad19)") (class "Default")
      (node (ref "STAMP5_ADC_SG1") (pin "19") (pinfunction "IEXC2_19") (pintype "bidirectional"))
    )
    (net (code "516") (name "unconnected-(STAMP5_ADC_SG1-REFN0{slash}GPIO1-Pad6)") (class "Default")
      (node (ref "STAMP5_ADC_SG1") (pin "6") (pinfunction "REFN0/GPIO1_6") (pintype "bidirectional"))
    )
    (net (code "517") (name "unconnected-(STAMP5_ADC_SG1-REFN1-Pad8)") (class "Default")
      (node (ref "STAMP5_ADC_SG1") (pin "8") (pinfunction "REFN1_8") (pintype "bidirectional"))
    )
    (net (code "518") (name "unconnected-(STAMP5_ADC_SG1-REFP0{slash}GPIO0-Pad5)") (class "Default")
      (node (ref "STAMP5_ADC_SG1") (pin "5") (pinfunction "REFP0/GPIO0_5") (pintype "bidirectional"))
    )
    (net (code "519") (name "unconnected-(STAMP5_ADC_SG1-REFP1-Pad7)") (class "Default")
      (node (ref "STAMP5_ADC_SG1") (pin "7") (pinfunction "REFP1_7") (pintype "bidirectional"))
    )
    (net (code "520") (name "unconnected-(STAMP5_ADC_SG2-AIN2{slash}IEXC{slash}GPIO2-Pad17)") (class "Default")
      (node (ref "STAMP5_ADC_SG2") (pin "17") (pinfunction "AIN2/IEXC/GPIO2_17") (pintype "bidirectional"))
    )
    (net (code "521") (name "unconnected-(STAMP5_ADC_SG2-AIN3{slash}IEXC{slash}GPIO3-Pad18)") (class "Default")
      (node (ref "STAMP5_ADC_SG2") (pin "18") (pinfunction "AIN3/IEXC/GPIO3_18") (pintype "bidirectional"))
    )
    (net (code "522") (name "unconnected-(STAMP5_ADC_SG2-AIN4{slash}IECG{slash}GPIO4-Pad13)") (class "Default")
      (node (ref "STAMP5_ADC_SG2") (pin "13") (pinfunction "AIN4/IECG/GPIO4_13") (pintype "bidirectional"))
    )
    (net (code "523") (name "unconnected-(STAMP5_ADC_SG2-AIN5{slash}IEXC{slash}GPIO5-Pad14)") (class "Default")
      (node (ref "STAMP5_ADC_SG2") (pin "14") (pinfunction "AIN5/IEXC/GPIO5_14") (pintype "bidirectional"))
    )
    (net (code "524") (name "unconnected-(STAMP5_ADC_SG2-AIN6{slash}IEXC{slash}GPIO6-Pad15)") (class "Default")
      (node (ref "STAMP5_ADC_SG2") (pin "15") (pinfunction "AIN6/IEXC/GPIO6_15") (pintype "bidirectional"))
    )
    (net (code "525") (name "unconnected-(STAMP5_ADC_SG2-AIN7{slash}IEXC{slash}GPIO7-Pad16)") (class "Default")
      (node (ref "STAMP5_ADC_SG2") (pin "16") (pinfunction "AIN7/IEXC/GPIO7_16") (pintype "bidirectional"))
    )
    (net (code "526") (name "unconnected-(STAMP5_ADC_SG2-IEXC1-Pad20)") (class "Default")
      (node (ref "STAMP5_ADC_SG2") (pin "20") (pinfunction "IEXC1_20") (pintype "bidirectional"))
    )
    (net (code "527") (name "unconnected-(STAMP5_ADC_SG2-IEXC2-Pad19)") (class "Default")
      (node (ref "STAMP5_ADC_SG2") (pin "19") (pinfunction "IEXC2_19") (pintype "bidirectional"))
    )
    (net (code "528") (name "unconnected-(STAMP5_ADC_SG2-REFN0{slash}GPIO1-Pad6)") (class "Default")
      (node (ref "STAMP5_ADC_SG2") (pin "6") (pinfunction "REFN0/GPIO1_6") (pintype "bidirectional"))
    )
    (net (code "529") (name "unconnected-(STAMP5_ADC_SG2-REFN1-Pad8)") (class "Default")
      (node (ref "STAMP5_ADC_SG2") (pin "8") (pinfunction "REFN1_8") (pintype "bidirectional"))
    )
    (net (code "530") (name "unconnected-(STAMP5_ADC_SG2-REFP0{slash}GPIO0-Pad5)") (class "Default")
      (node (ref "STAMP5_ADC_SG2") (pin "5") (pinfunction "REFP0/GPIO0_5") (pintype "bidirectional"))
    )
    (net (code "531") (name "unconnected-(STAMP5_ADC_SG2-REFP1-Pad7)") (class "Default")
      (node (ref "STAMP5_ADC_SG2") (pin "7") (pinfunction "REFP1_7") (pintype "bidirectional"))
    )
    (net (code "532") (name "unconnected-(STAMP5_ADC_TEMP-AIN4{slash}IECG{slash}GPIO4-Pad13)") (class "Default")
      (node (ref "STAMP5_ADC_TEMP") (pin "13") (pinfunction "AIN4/IECG/GPIO4_13") (pintype "bidirectional"))
    )
    (net (code "533") (name "unconnected-(STAMP5_ADC_TEMP-AIN5{slash}IEXC{slash}GPIO5-Pad14)") (class "Default")
      (node (ref "STAMP5_ADC_TEMP") (pin "14") (pinfunction "AIN5/IEXC/GPIO5_14") (pintype "bidirectional"))
    )
    (net (code "534") (name "unconnected-(STAMP5_ADC_TEMP-AIN6{slash}IEXC{slash}GPIO6-Pad15)") (class "Default")
      (node (ref "STAMP5_ADC_TEMP") (pin "15") (pinfunction "AIN6/IEXC/GPIO6_15") (pintype "bidirectional"))
    )
    (net (code "535") (name "unconnected-(STAMP5_ADC_TEMP-AIN7{slash}IEXC{slash}GPIO7-Pad16)") (class "Default")
      (node (ref "STAMP5_ADC_TEMP") (pin "16") (pinfunction "AIN7/IEXC/GPIO7_16") (pintype "bidirectional"))
    )
    (net (code "536") (name "unconnected-(STAMP5_ADC_TEMP-IEXC1-Pad20)") (class "Default")
      (node (ref "STAMP5_ADC_TEMP") (pin "20") (pinfunction "IEXC1_20") (pintype "bidirectional"))
    )
    (net (code "537") (name "unconnected-(STAMP5_ADC_TEMP-IEXC2-Pad19)") (class "Default")
      (node (ref "STAMP5_ADC_TEMP") (pin "19") (pinfunction "IEXC2_19") (pintype "bidirectional"))
    )
    (net (code "538") (name "unconnected-(STAMP5_ADC_TEMP-REFN1-Pad8)") (class "Default")
      (node (ref "STAMP5_ADC_TEMP") (pin "8") (pinfunction "REFN1_8") (pintype "bidirectional"))
    )
    (net (code "539") (name "unconnected-(STAMP5_ADC_TEMP-REFP1-Pad7)") (class "Default")
      (node (ref "STAMP5_ADC_TEMP") (pin "7") (pinfunction "REFP1_7") (pintype "bidirectional"))
    )
    (net (code "540") (name "unconnected-(STAMP6_ADC_SG1-AIN2{slash}IEXC{slash}GPIO2-Pad17)") (class "Default")
      (node (ref "STAMP6_ADC_SG1") (pin "17") (pinfunction "AIN2/IEXC/GPIO2_17") (pintype "bidirectional"))
    )
    (net (code "541") (name "unconnected-(STAMP6_ADC_SG1-AIN3{slash}IEXC{slash}GPIO3-Pad18)") (class "Default")
      (node (ref "STAMP6_ADC_SG1") (pin "18") (pinfunction "AIN3/IEXC/GPIO3_18") (pintype "bidirectional"))
    )
    (net (code "542") (name "unconnected-(STAMP6_ADC_SG1-AIN4{slash}IECG{slash}GPIO4-Pad13)") (class "Default")
      (node (ref "STAMP6_ADC_SG1") (pin "13") (pinfunction "AIN4/IECG/GPIO4_13") (pintype "bidirectional"))
    )
    (net (code "543") (name "unconnected-(STAMP6_ADC_SG1-AIN5{slash}IEXC{slash}GPIO5-Pad14)") (class "Default")
      (node (ref "STAMP6_ADC_SG1") (pin "14") (pinfunction "AIN5/IEXC/GPIO5_14") (pintype "bidirectional"))
    )
    (net (code "544") (name "unconnected-(STAMP6_ADC_SG1-AIN6{slash}IEXC{slash}GPIO6-Pad15)") (class "Default")
      (node (ref "STAMP6_ADC_SG1") (pin "15") (pinfunction "AIN6/IEXC/GPIO6_15") (pintype "bidirectional"))
    )
    (net (code "545") (name "unconnected-(STAMP6_ADC_SG1-AIN7{slash}IEXC{slash}GPIO7-Pad16)") (class "Default")
      (node (ref "STAMP6_ADC_SG1") (pin "16") (pinfunction "AIN7/IEXC/GPIO7_16") (pintype "bidirectional"))
    )
    (net (code "546") (name "unconnected-(STAMP6_ADC_SG1-IEXC1-Pad20)") (class "Default")
      (node (ref "STAMP6_ADC_SG1") (pin "20") (pinfunction "IEXC1_20") (pintype "bidirectional"))
    )
    (net (code "547") (name "unconnected-(STAMP6_ADC_SG1-IEXC2-Pad19)") (class "Default")
      (node (ref "STAMP6_ADC_SG1") (pin "19") (pinfunction "IEXC2_19") (pintype "bidirectional"))
    )
    (net (code "548") (name "unconnected-(STAMP6_ADC_SG1-REFN0{slash}GPIO1-Pad6)") (class "Default")
      (node (ref "STAMP6_ADC_SG1") (pin "6") (pinfunction "REFN0/GPIO1_6") (pintype "bidirectional"))
    )
    (net (code "549") (name "unconnected-(STAMP6_ADC_SG1-REFN1-Pad8)") (class "Default")
      (node (ref "STAMP6_ADC_SG1") (pin "8") (pinfunction "REFN1_8") (pintype "bidirectional"))
    )
    (net (code "550") (name "unconnected-(STAMP6_ADC_SG1-REFP0{slash}GPIO0-Pad5)") (class "Default")
      (node (ref "STAMP6_ADC_SG1") (pin "5") (pinfunction "REFP0/GPIO0_5") (pintype "bidirectional"))
    )
    (net (code "551") (name "unconnected-(STAMP6_ADC_SG1-REFP1-Pad7)") (class "Default")
      (node (ref "STAMP6_ADC_SG1") (pin "7") (pinfunction "REFP1_7") (pintype "bidirectional"))
    )
    (net (code "552") (name "unconnected-(STAMP6_ADC_SG2-AIN2{slash}IEXC{slash}GPIO2-Pad17)") (class "Default")
      (node (ref "STAMP6_ADC_SG2") (pin "17") (pinfunction "AIN2/IEXC/GPIO2_17") (pintype "bidirectional"))
    )
    (net (code "553") (name "unconnected-(STAMP6_ADC_SG2-AIN3{slash}IEXC{slash}GPIO3-Pad18)") (class "Default")
      (node (ref "STAMP6_ADC_SG2") (pin "18") (pinfunction "AIN3/IEXC/GPIO3_18") (pintype "bidirectional"))
    )
    (net (code "554") (name "unconnected-(STAMP6_ADC_SG2-AIN4{slash}IECG{slash}GPIO4-Pad13)") (class "Default")
      (node (ref "STAMP6_ADC_SG2") (pin "13") (pinfunction "AIN4/IECG/GPIO4_13") (pintype "bidirectional"))
    )
    (net (code "555") (name "unconnected-(STAMP6_ADC_SG2-AIN5{slash}IEXC{slash}GPIO5-Pad14)") (class "Default")
      (node (ref "STAMP6_ADC_SG2") (pin "14") (pinfunction "AIN5/IEXC/GPIO5_14") (pintype "bidirectional"))
    )
    (net (code "556") (name "unconnected-(STAMP6_ADC_SG2-AIN6{slash}IEXC{slash}GPIO6-Pad15)") (class "Default")
      (node (ref "STAMP6_ADC_SG2") (pin "15") (pinfunction "AIN6/IEXC/GPIO6_15") (pintype "bidirectional"))
    )
    (net (code "557") (name "unconnected-(STAMP6_ADC_SG2-AIN7{slash}IEXC{slash}GPIO7-Pad16)") (class "Default")
      (node (ref "STAMP6_ADC_SG2") (pin "16") (pinfunction "AIN7/IEXC/GPIO7_16") (pintype "bidirectional"))
    )
    (net (code "558") (name "unconnected-(STAMP6_ADC_SG2-IEXC1-Pad20)") (class "Default")
      (node (ref "STAMP6_ADC_SG2") (pin "20") (pinfunction "IEXC1_20") (pintype "bidirectional"))
    )
    (net (code "559") (name "unconnected-(STAMP6_ADC_SG2-IEXC2-Pad19)") (class "Default")
      (node (ref "STAMP6_ADC_SG2") (pin "19") (pinfunction "IEXC2_19") (pintype "bidirectional"))
    )
    (net (code "560") (name "unconnected-(STAMP6_ADC_SG2-REFN0{slash}GPIO1-Pad6)") (class "Default")
      (node (ref "STAMP6_ADC_SG2") (pin "6") (pinfunction "REFN0/GPIO1_6") (pintype "bidirectional"))
    )
    (net (code "561") (name "unconnected-(STAMP6_ADC_SG2-REFN1-Pad8)") (class "Default")
      (node (ref "STAMP6_ADC_SG2") (pin "8") (pinfunction "REFN1_8") (pintype "bidirectional"))
    )
    (net (code "562") (name "unconnected-(STAMP6_ADC_SG2-REFP0{slash}GPIO0-Pad5)") (class "Default")
      (node (ref "STAMP6_ADC_SG2") (pin "5") (pinfunction "REFP0/GPIO0_5") (pintype "bidirectional"))
    )
    (net (code "563") (name "unconnected-(STAMP6_ADC_SG2-REFP1-Pad7)") (class "Default")
      (node (ref "STAMP6_ADC_SG2") (pin "7") (pinfunction "REFP1_7") (pintype "bidirectional"))
    )
    (net (code "564") (name "unconnected-(STAMP6_ADC_TEMP-AIN4{slash}IECG{slash}GPIO4-Pad13)") (class "Default")
      (node (ref "STAMP6_ADC_TEMP") (pin "13") (pinfunction "AIN4/IECG/GPIO4_13") (pintype "bidirectional"))
    )
    (net (code "565") (name "unconnected-(STAMP6_ADC_TEMP-AIN5{slash}IEXC{slash}GPIO5-Pad14)") (class "Default")
      (node (ref "STAMP6_ADC_TEMP") (pin "14") (pinfunction "AIN5/IEXC/GPIO5_14") (pintype "bidirectional"))
    )
    (net (code "566") (name "unconnected-(STAMP6_ADC_TEMP-AIN6{slash}IEXC{slash}GPIO6-Pad15)") (class "Default")
      (node (ref "STAMP6_ADC_TEMP") (pin "15") (pinfunction "AIN6/IEXC/GPIO6_15") (pintype "bidirectional"))
    )
    (net (code "567") (name "unconnected-(STAMP6_ADC_TEMP-AIN7{slash}IEXC{slash}GPIO7-Pad16)") (class "Default")
      (node (ref "STAMP6_ADC_TEMP") (pin "16") (pinfunction "AIN7/IEXC/GPIO7_16") (pintype "bidirectional"))
    )
    (net (code "568") (name "unconnected-(STAMP6_ADC_TEMP-IEXC1-Pad20)") (class "Default")
      (node (ref "STAMP6_ADC_TEMP") (pin "20") (pinfunction "IEXC1_20") (pintype "bidirectional"))
    )
    (net (code "569") (name "unconnected-(STAMP6_ADC_TEMP-IEXC2-Pad19)") (class "Default")
      (node (ref "STAMP6_ADC_TEMP") (pin "19") (pinfunction "IEXC2_19") (pintype "bidirectional"))
    )
    (net (code "570") (name "unconnected-(STAMP6_ADC_TEMP-REFN1-Pad8)") (class "Default")
      (node (ref "STAMP6_ADC_TEMP") (pin "8") (pinfunction "REFN1_8") (pintype "bidirectional"))
    )
    (net (code "571") (name "unconnected-(STAMP6_ADC_TEMP-REFP1-Pad7)") (class "Default")
      (node (ref "STAMP6_ADC_TEMP") (pin "7") (pinfunction "REFP1_7") (pintype "bidirectional"))
    )
    (net (code "572") (name "unconnected-(USB-ACBUS0-Pad26)") (class "Default")
      (node (ref "USB") (pin "26") (pinfunction "ACBUS0_26") (pintype "bidirectional"))
    )
    (net (code "573") (name "unconnected-(USB-ACBUS1-Pad27)") (class "Default")
      (node (ref "USB") (pin "27") (pinfunction "ACBUS1_27") (pintype "bidirectional"))
    )
    (net (code "574") (name "unconnected-(USB-ACBUS2-Pad28)") (class "Default")
      (node (ref "USB") (pin "28") (pinfunction "ACBUS2_28") (pintype "bidirectional"))
    )
    (net (code "575") (name "unconnected-(USB-ACBUS3-Pad29)") (class "Default")
      (node (ref "USB") (pin "29") (pinfunction "ACBUS3_29") (pintype "bidirectional"))
    )
    (net (code "576") (name "unconnected-(USB-ACBUS4-Pad30)") (class "Default")
      (node (ref "USB") (pin "30") (pinfunction "ACBUS4_30") (pintype "bidirectional"))
    )
    (net (code "577") (name "unconnected-(USB-ACBUS5-Pad32)") (class "Default")
      (node (ref "USB") (pin "32") (pinfunction "ACBUS5_32") (pintype "bidirectional"))
    )
    (net (code "578") (name "unconnected-(USB-ACBUS6-Pad33)") (class "Default")
      (node (ref "USB") (pin "33") (pinfunction "ACBUS6_33") (pintype "bidirectional"))
    )
    (net (code "579") (name "unconnected-(USB-ACBUS7-Pad34)") (class "Default")
      (node (ref "USB") (pin "34") (pinfunction "ACBUS7_34") (pintype "bidirectional"))
    )
    (net (code "580") (name "unconnected-(USB-ADBUS4-Pad21)") (class "Default")
      (node (ref "USB") (pin "21") (pinfunction "ADBUS4_21") (pintype "bidirectional"))
    )
    (net (code "581") (name "unconnected-(USB-ADBUS5-Pad22)") (class "Default")
      (node (ref "USB") (pin "22") (pinfunction "ADBUS5_22") (pintype "bidirectional"))
    )
    (net (code "582") (name "unconnected-(USB-ADBUS6-Pad23)") (class "Default")
      (node (ref "USB") (pin "23") (pinfunction "ADBUS6_23") (pintype "bidirectional"))
    )
    (net (code "583") (name "unconnected-(USB-ADBUS7-Pad24)") (class "Default")
      (node (ref "USB") (pin "24") (pinfunction "ADBUS7_24") (pintype "bidirectional"))
    )
    (net (code "584") (name "unconnected-(USB-BCBUS0-Pad48)") (class "Default")
      (node (ref "USB") (pin "48") (pinfunction "BCBUS0_48") (pintype "bidirectional"))
    )
    (net (code "585") (name "unconnected-(USB-BCBUS1-Pad52)") (class "Default")
      (node (ref "USB") (pin "52") (pinfunction "BCBUS1_52") (pintype "bidirectional"))
    )
    (net (code "586") (name "unconnected-(USB-BCBUS2-Pad53)") (class "Default")
      (node (ref "USB") (pin "53") (pinfunction "BCBUS2_53") (pintype "bidirectional"))
    )
    (net (code "587") (name "unconnected-(USB-BCBUS3-Pad54)") (class "Default")
      (node (ref "USB") (pin "54") (pinfunction "BCBUS3_54") (pintype "bidirectional"))
    )
    (net (code "588") (name "unconnected-(USB-BCBUS4-Pad55)") (class "Default")
      (node (ref "USB") (pin "55") (pinfunction "BCBUS4_55") (pintype "bidirectional"))
    )
    (net (code "589") (name "unconnected-(USB-BCBUS5-Pad57)") (class "Default")
      (node (ref "USB") (pin "57") (pinfunction "BCBUS5_57") (pintype "bidirectional"))
    )
    (net (code "590") (name "unconnected-(USB-BCBUS6-Pad58)") (class "Default")
      (node (ref "USB") (pin "58") (pinfunction "BCBUS6_58") (pintype "bidirectional"))
    )
    (net (code "591") (name "unconnected-(USB-BCBUS7-Pad59)") (class "Default")
      (node (ref "USB") (pin "59") (pinfunction "BCBUS7_59") (pintype "bidirectional"))
    )
    (net (code "592") (name "unconnected-(USB-BDBUS6-Pad45)") (class "Default")
      (node (ref "USB") (pin "45") (pinfunction "BDBUS6_45") (pintype "bidirectional"))
    )
    (net (code "593") (name "unconnected-(USB-BDBUS7-Pad46)") (class "Default")
      (node (ref "USB") (pin "46") (pinfunction "BDBUS7_46") (pintype "bidirectional"))
    )
    (net (code "594") (name "unconnected-(USB-PWREN-Pad60)") (class "Default")
      (node (ref "USB") (pin "60") (pinfunction "PWREN_60") (pintype "bidirectional"))
    )
    (net (code "595") (name "unconnected-(USB-SUSPEND-Pad36)") (class "Default")
      (node (ref "USB") (pin "36") (pinfunction "SUSPEND_36") (pintype "bidirectional"))
    )
    (net (code "596") (name "unconnected-(USB_CONN-PadID)") (class "Default")
      (node (ref "USB_CONN") (pin "ID") (pinfunction "ID_ID") (pintype "bidirectional"))
    )
    (net (code "597") (name "unconnected-(U_TRACODCDC-RMT_ON_OFF-Pad6)") (class "Default")
      (node (ref "U_TRACODCDC") (pin "6") (pinfunction "RMT_ON_OFF_6") (pintype "input"))
    )
    (net (code "598") (name "unconnected-(U_TRACODCDC-TRIM-Pad4)") (class "Default")
      (node (ref "U_TRACODCDC") (pin "4") (pinfunction "TRIM_4") (pintype "input"))
    )
    (net (code "599") (name "unconnected-(X1-Pad2)") (class "Default")
      (node (ref "X1") (pin "2") (pinfunction "2_2") (pintype "passive"))
    )
    (net (code "600") (name "unconnected-(X1-Pad10)") (class "Default")
      (node (ref "X1") (pin "10") (pinfunction "10_10") (pintype "passive"))
    )
    (net (code "601") (name "unconnected-(X1-Pad11)") (class "Default")
      (node (ref "X1") (pin "11") (pinfunction "11_11") (pintype "passive"))
    )
    (net (code "602") (name "unconnected-(X1-Pad12)") (class "Default")
      (node (ref "X1") (pin "12") (pinfunction "12_12") (pintype "passive"))
    )
  )
)
